# DATALOGGER_ADS_V1.net
KiCad netlist of a schematic drawn in EAGLE
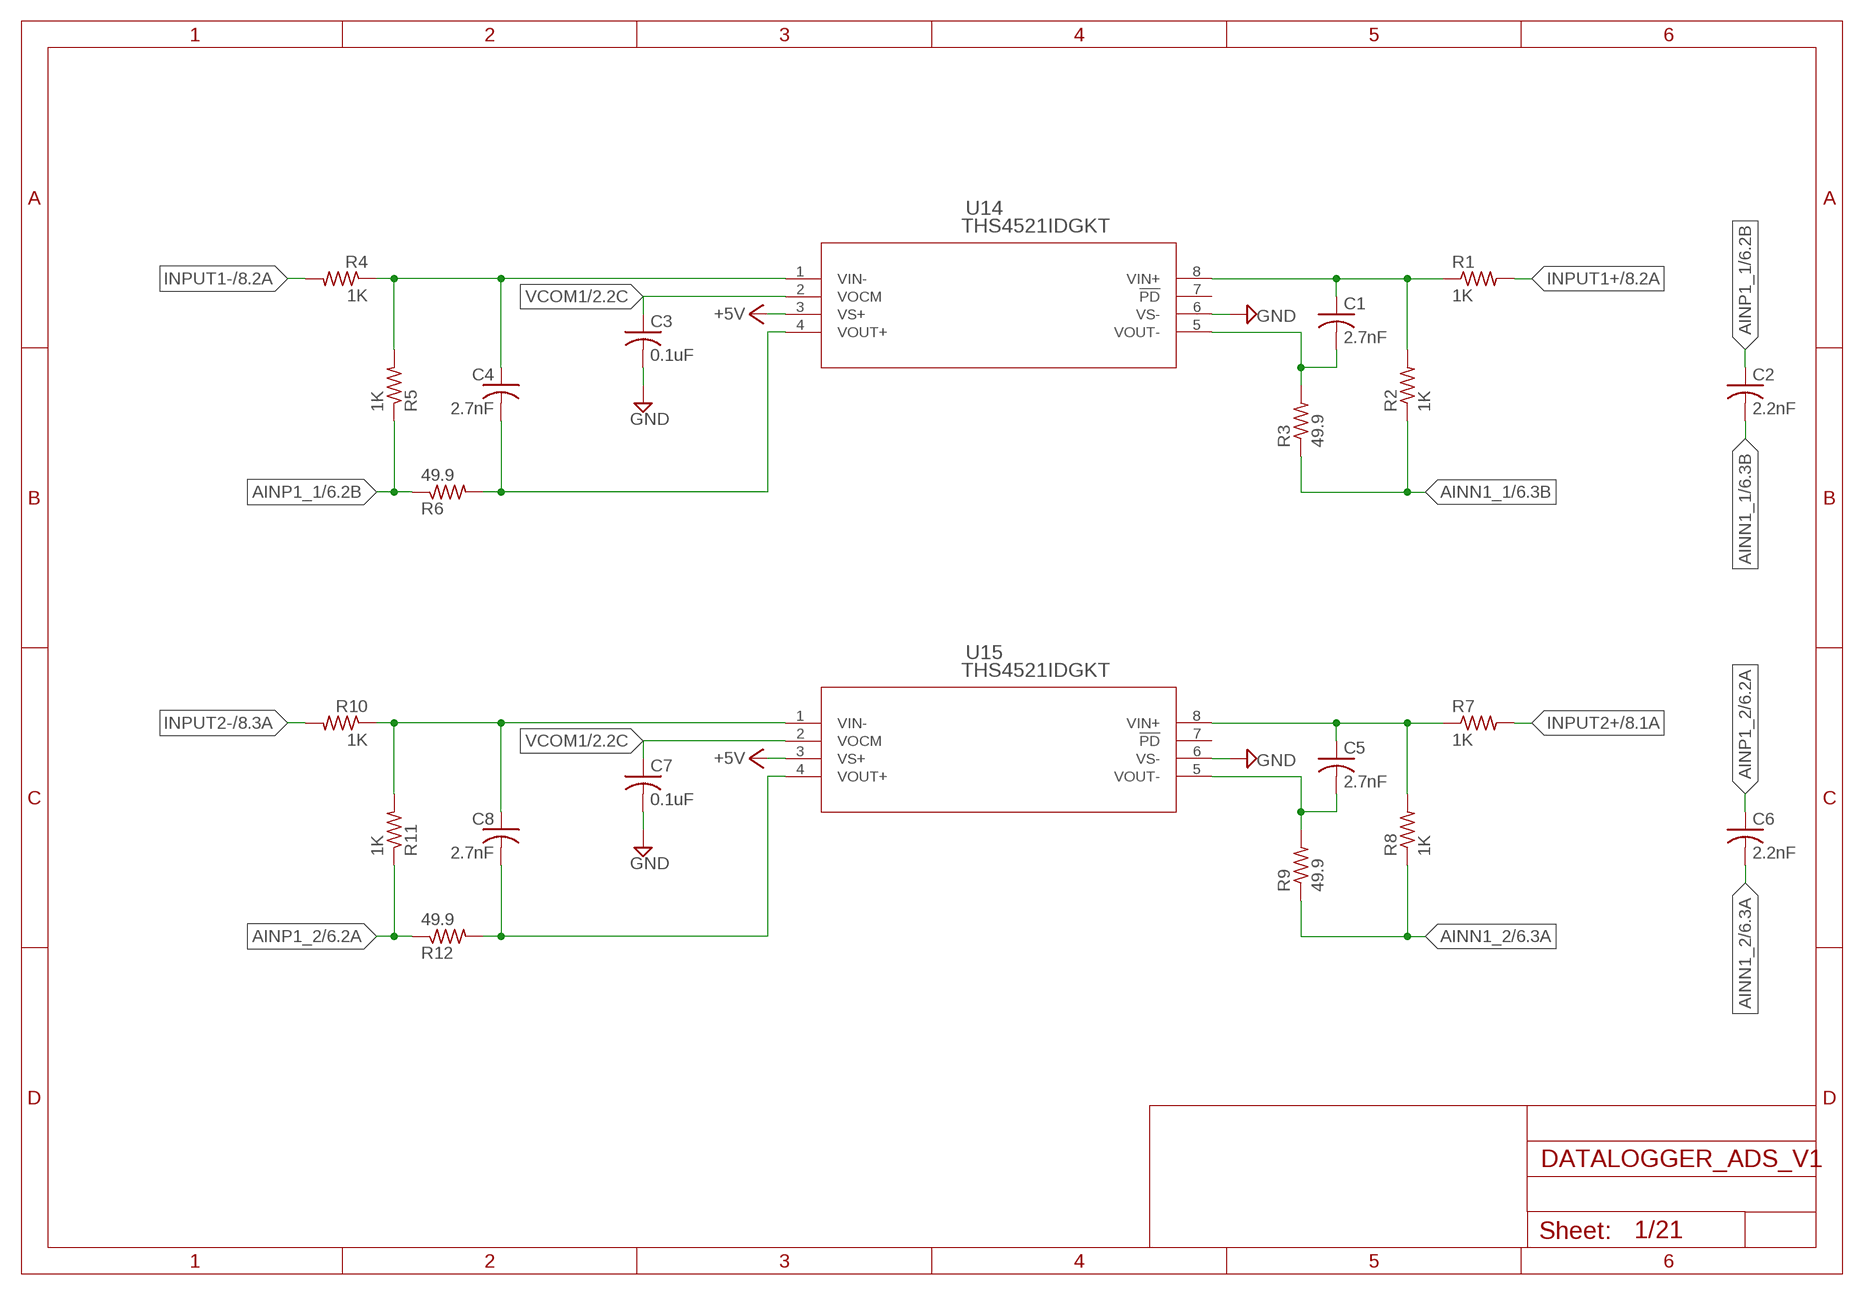
[diagram p0: schematic, sheet 1]
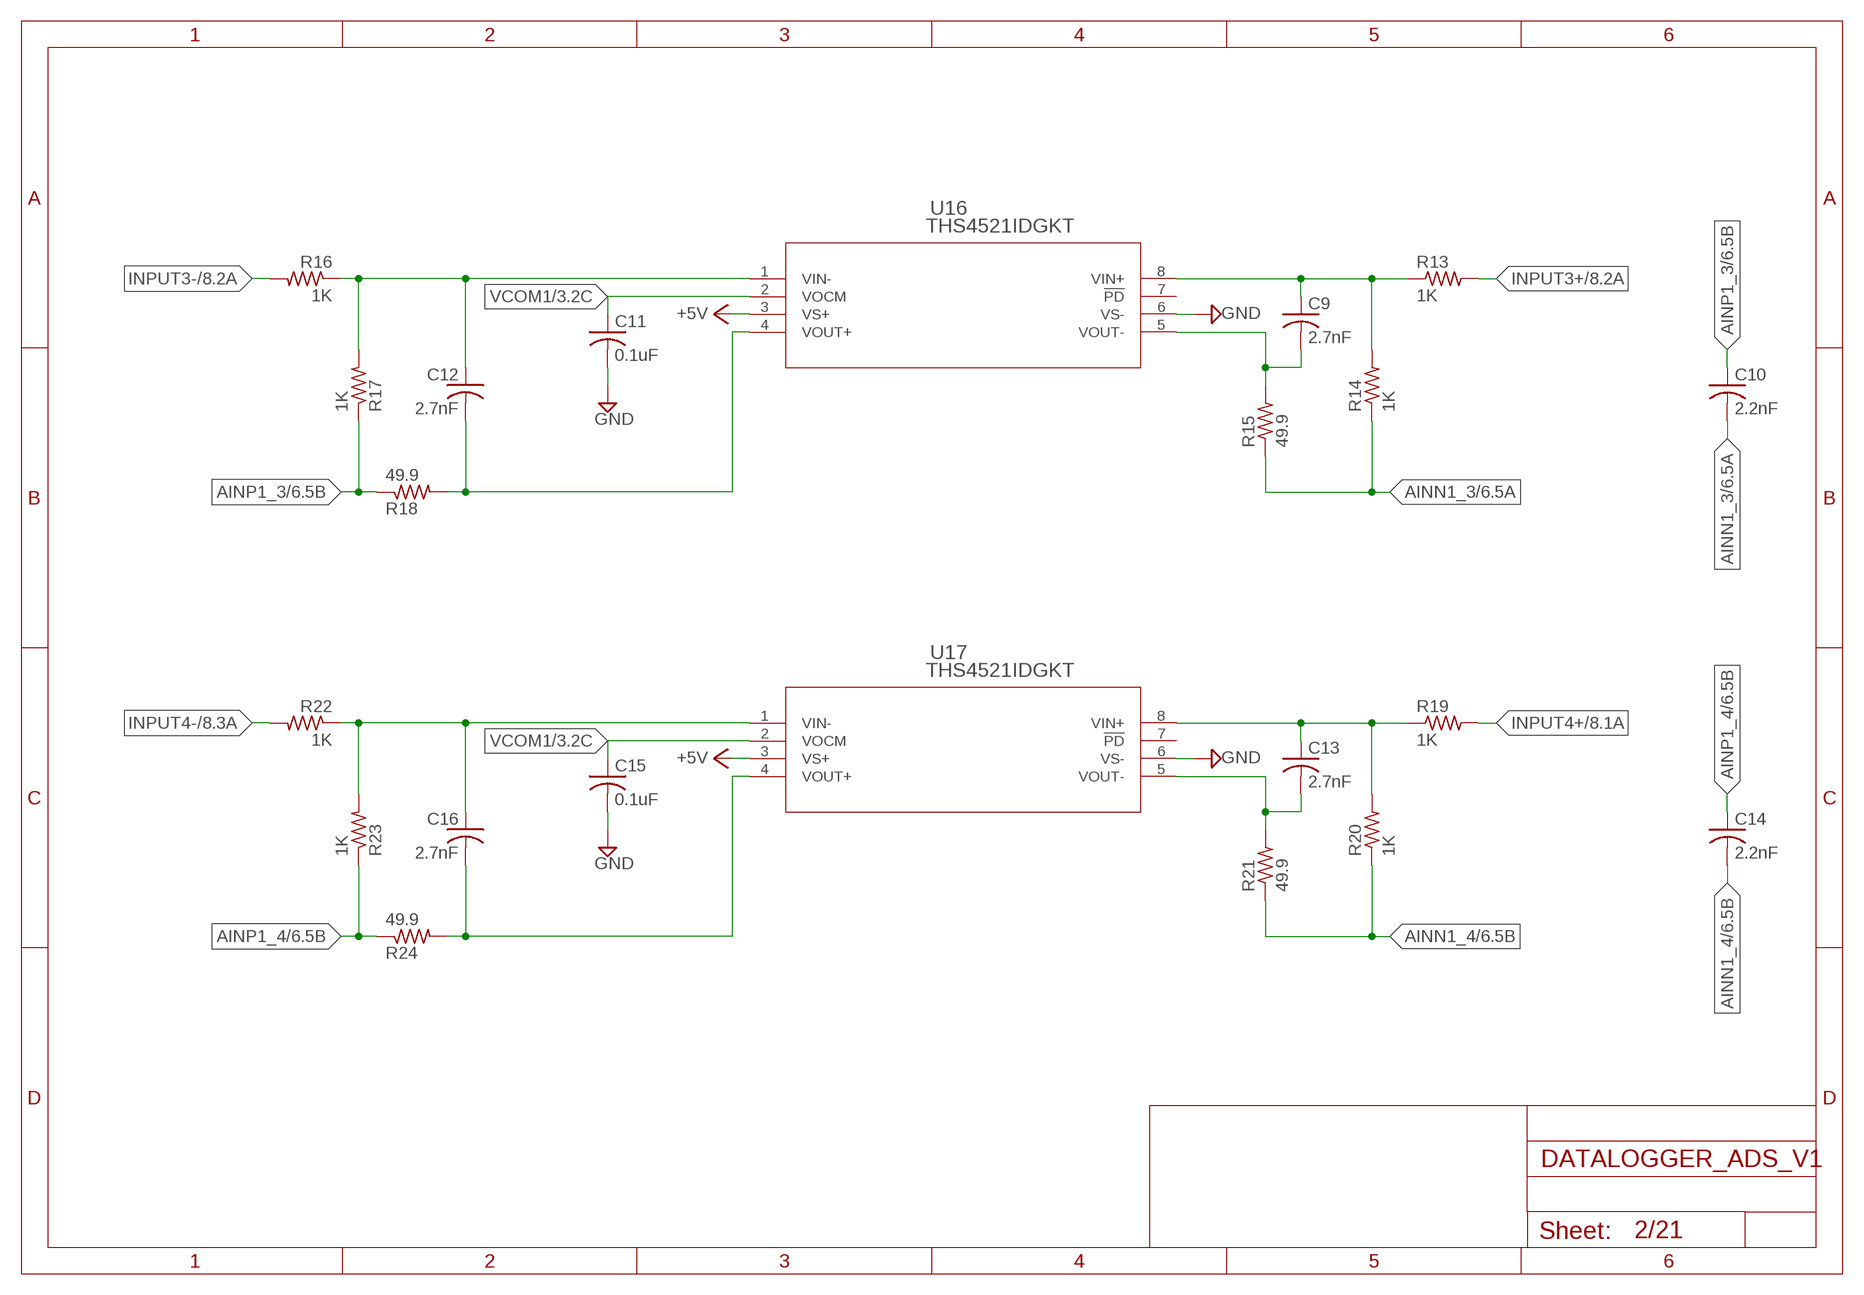
[diagram p1: schematic, sheet 2]
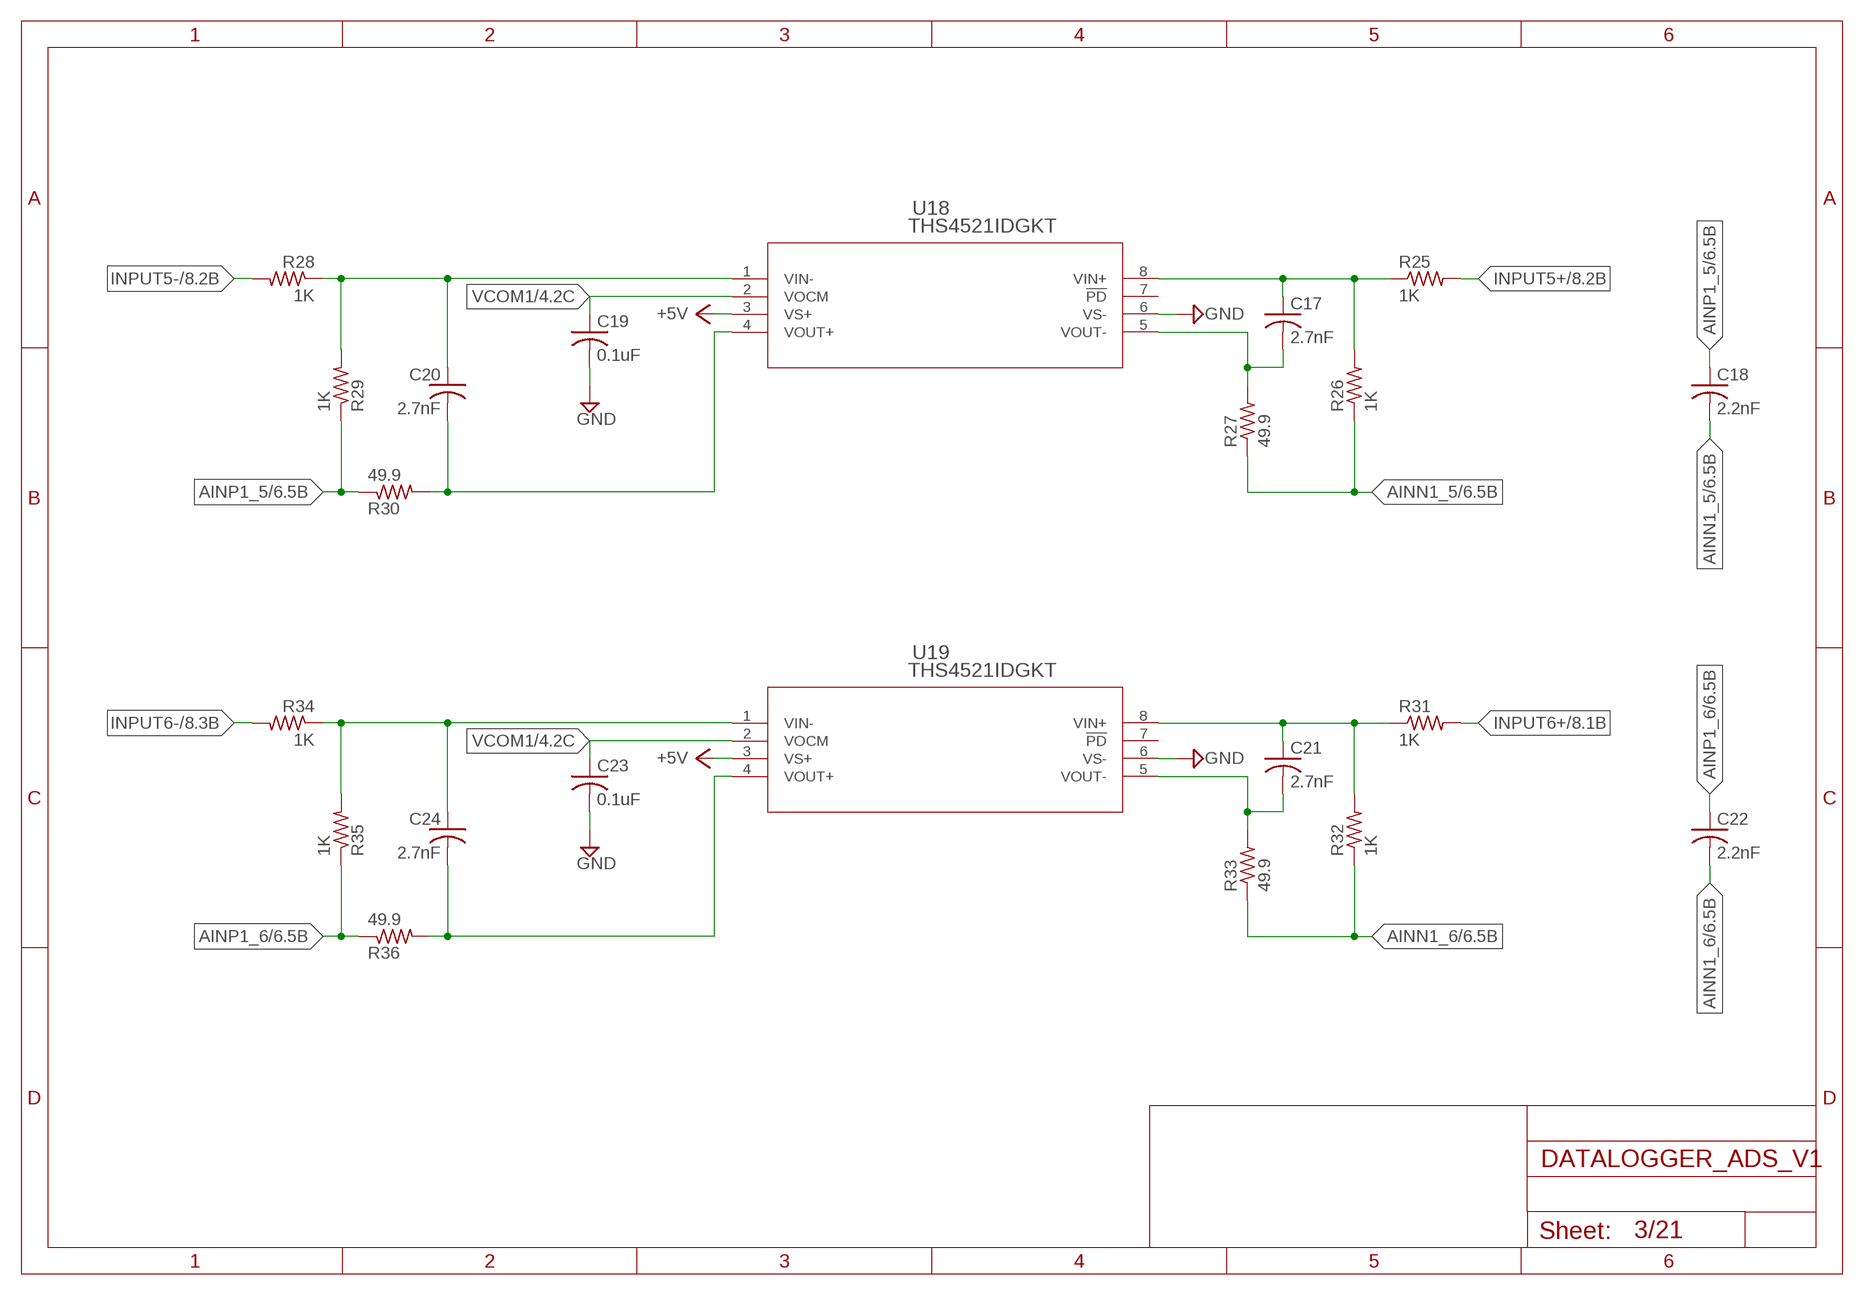
[diagram p2: schematic, sheet 3]
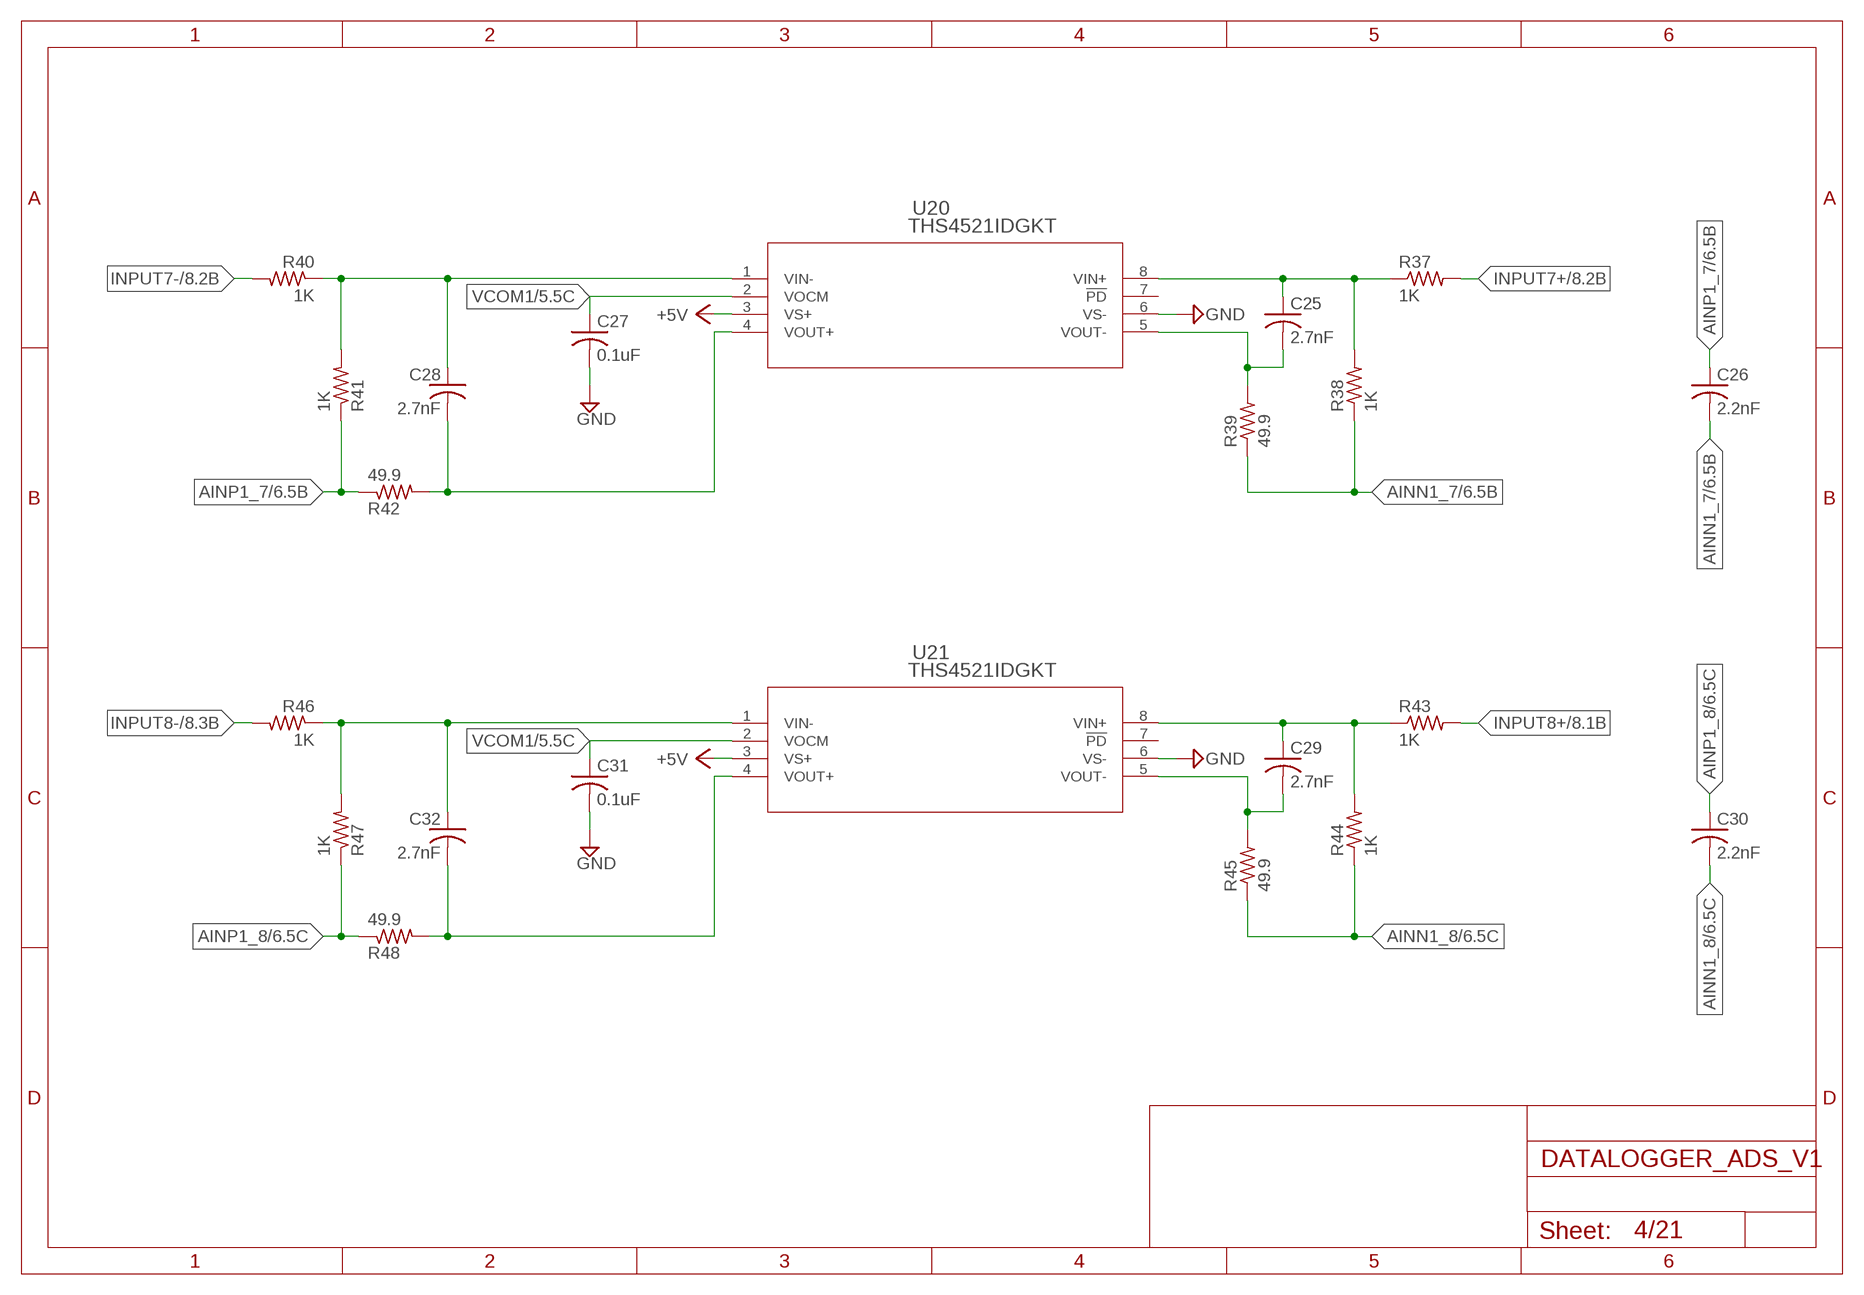
[diagram p3: schematic, sheet 4]
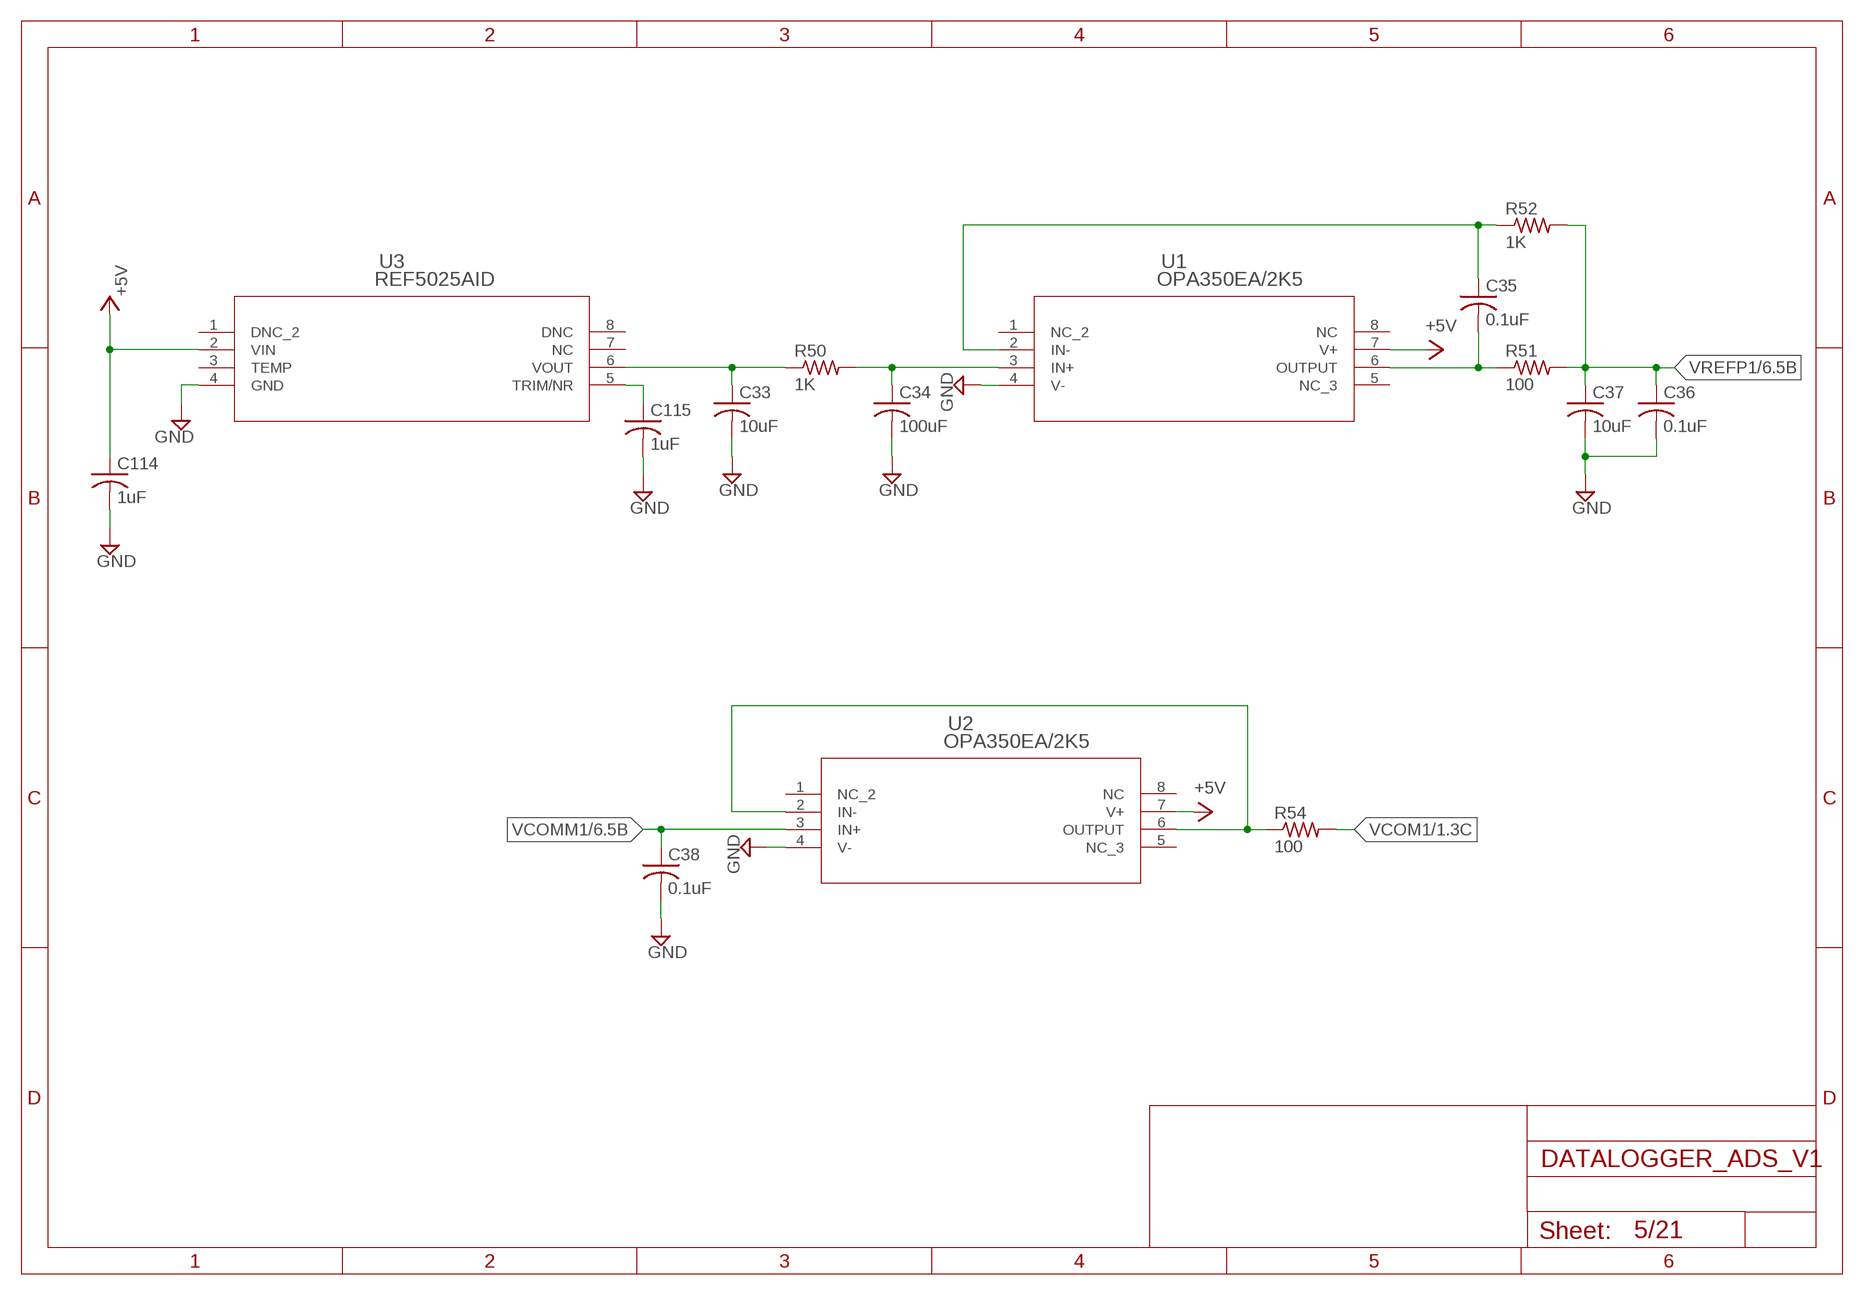
[diagram p4: schematic, sheet 5]
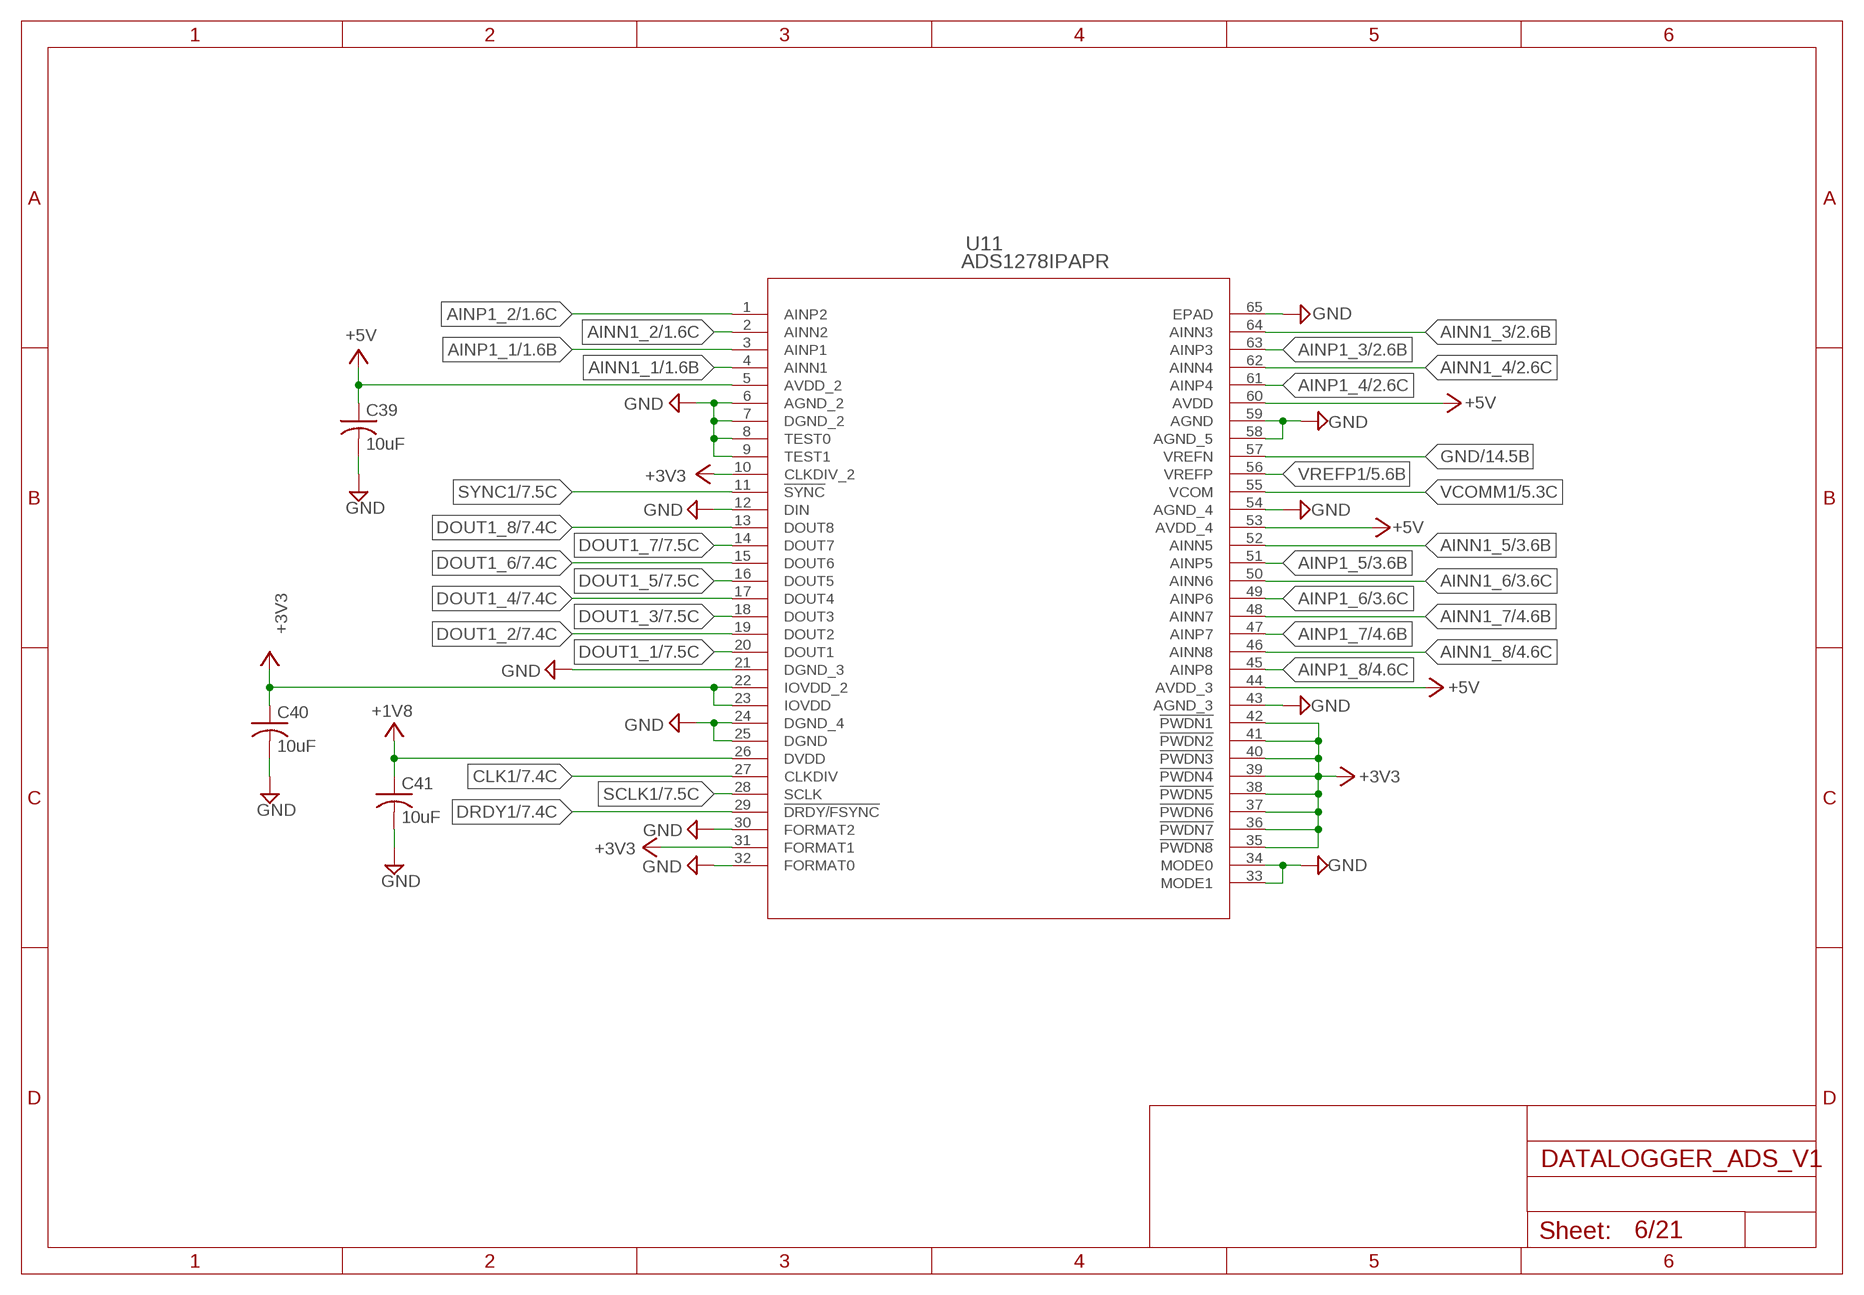
[diagram p5: schematic, sheet 6]
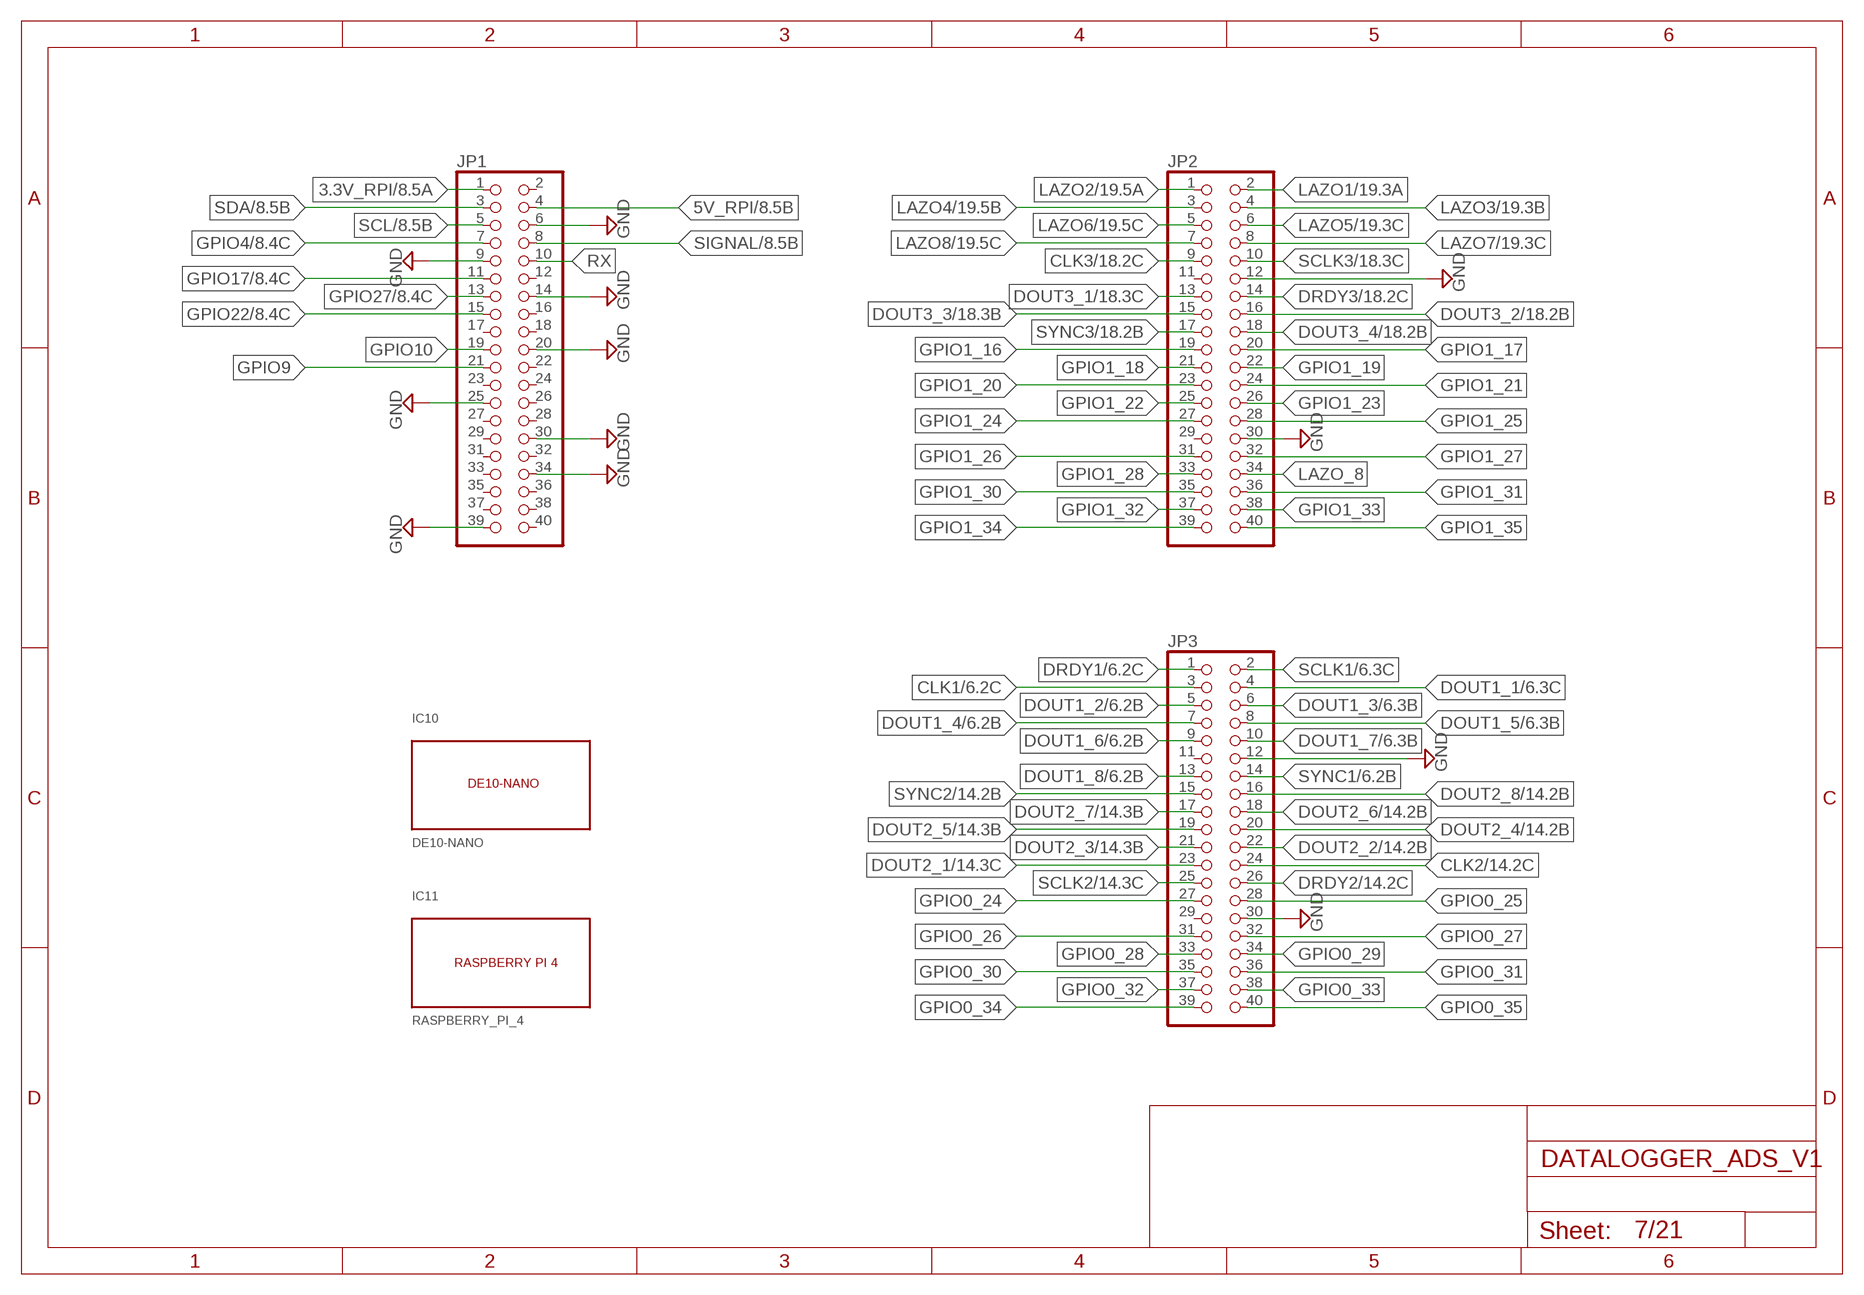
[diagram p6: schematic, sheet 7]
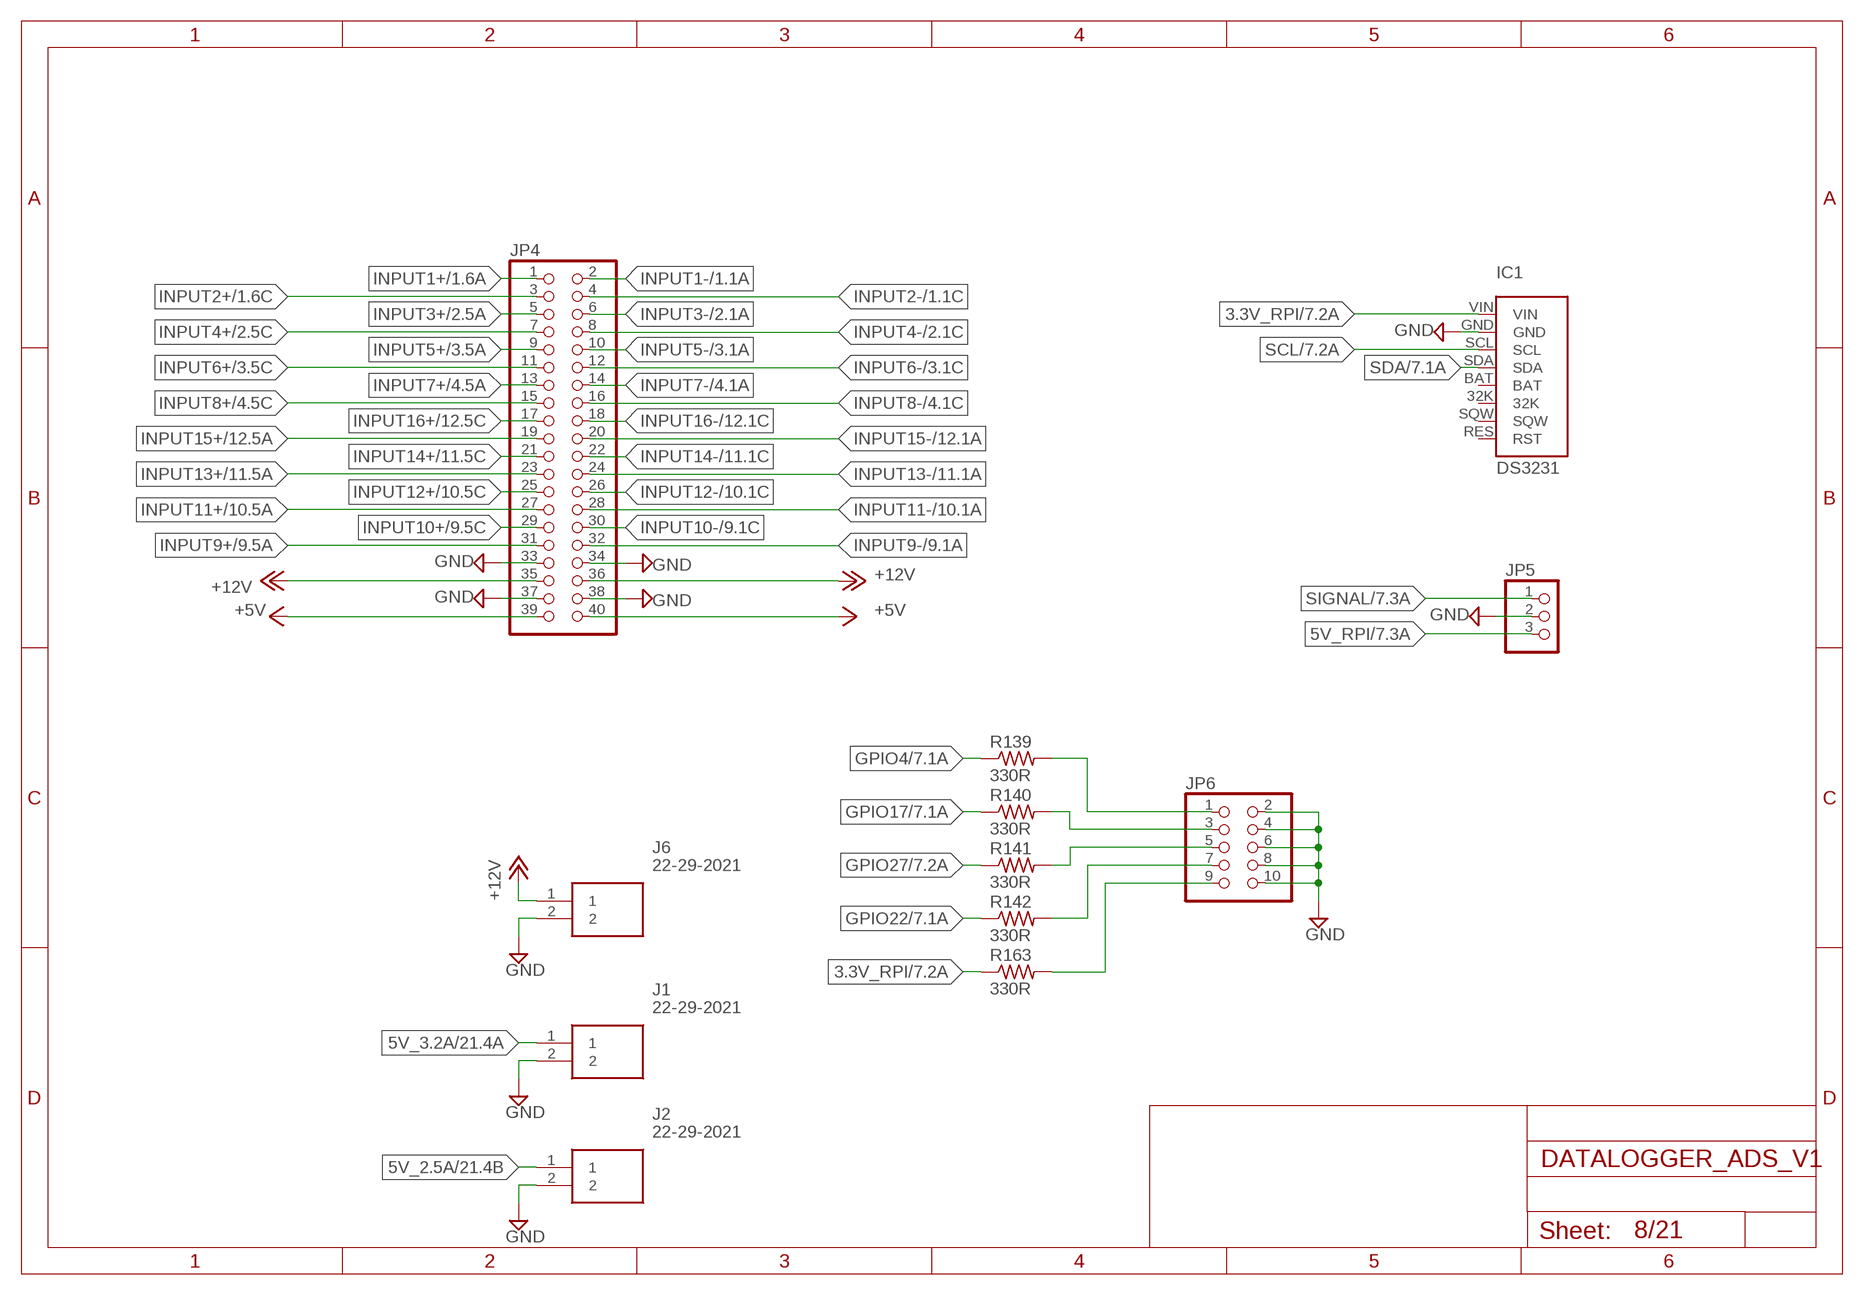
[diagram p7: schematic, sheet 8]
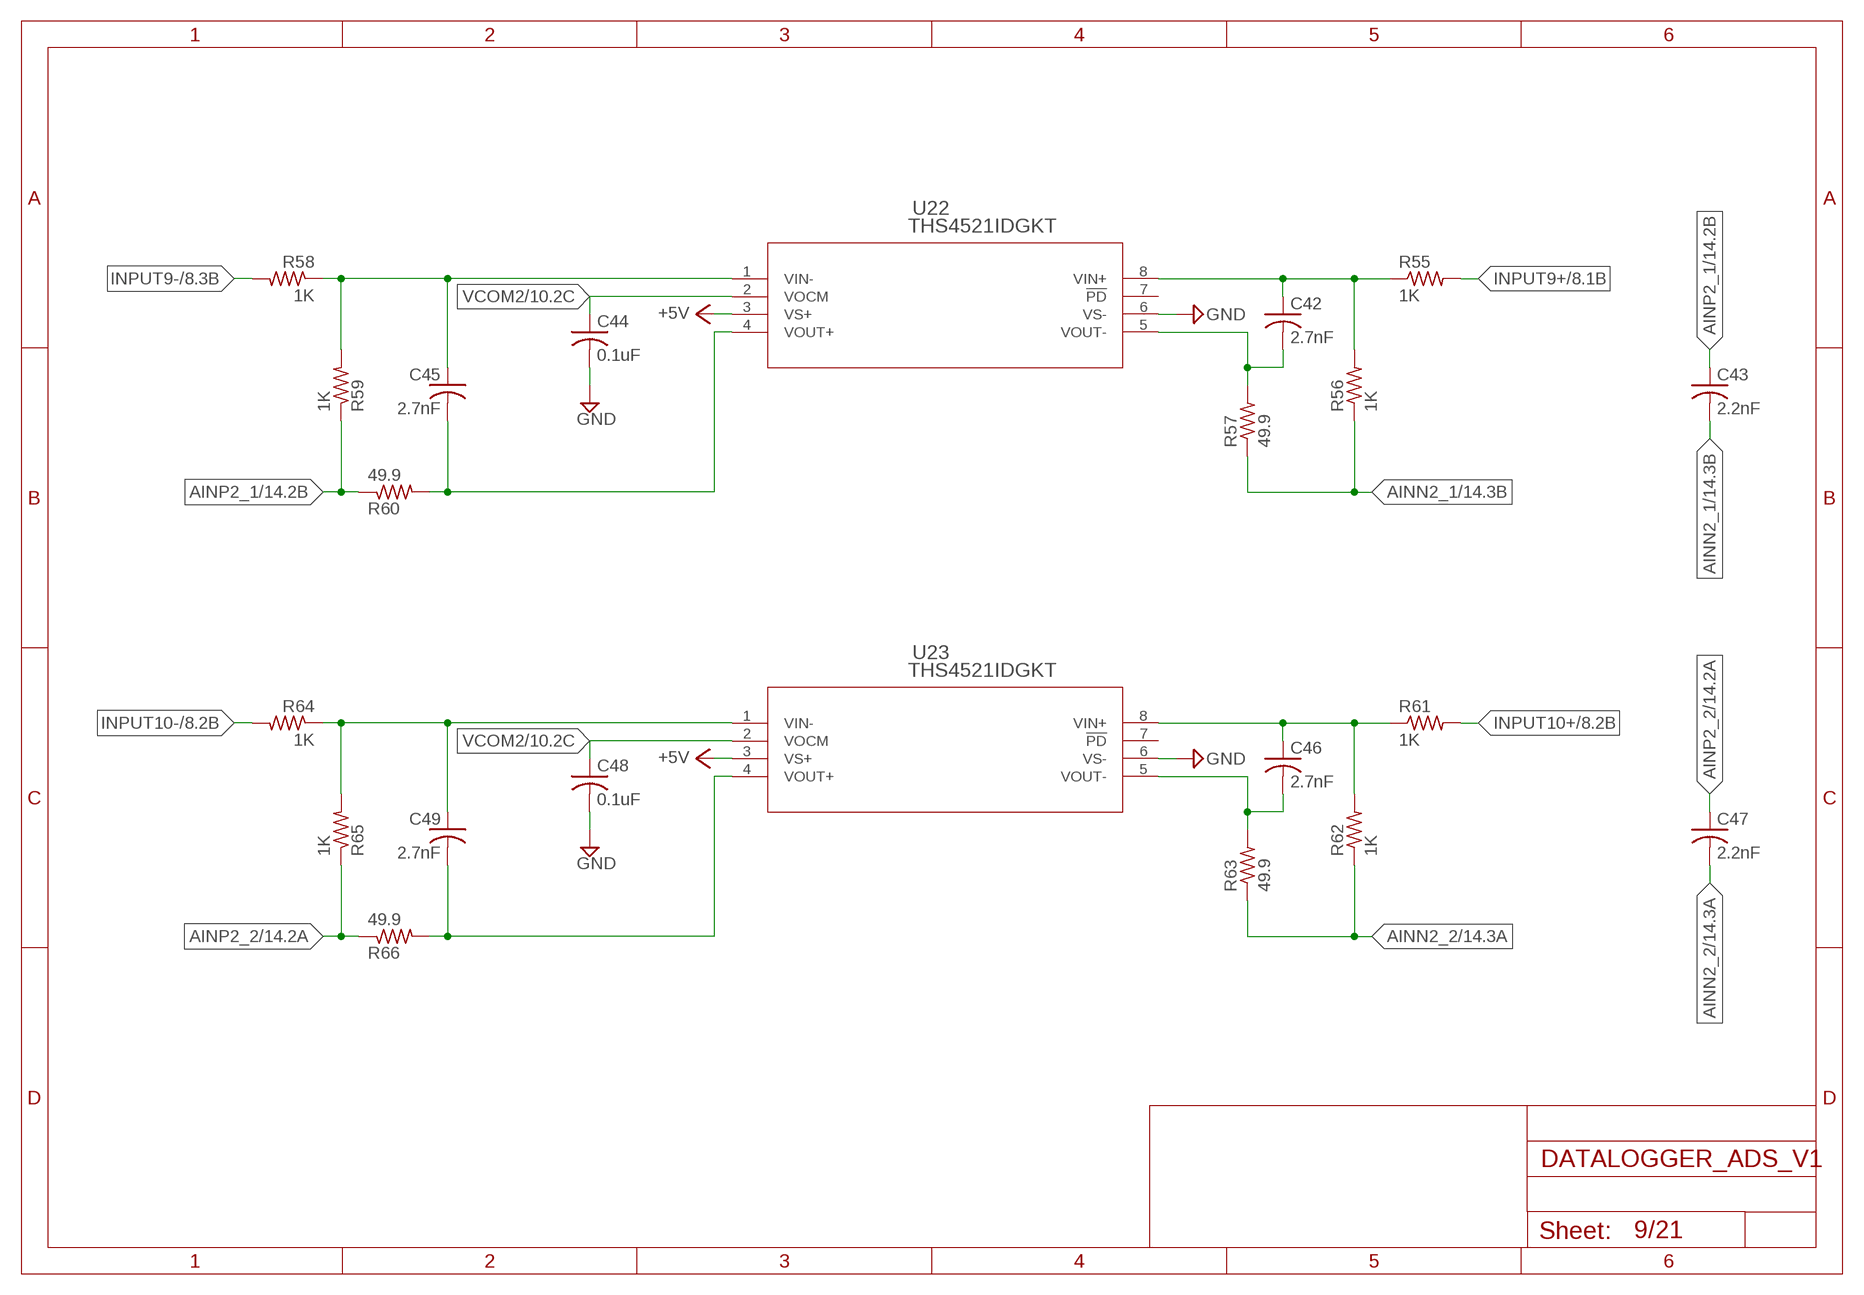
[diagram p8: schematic, sheet 9]
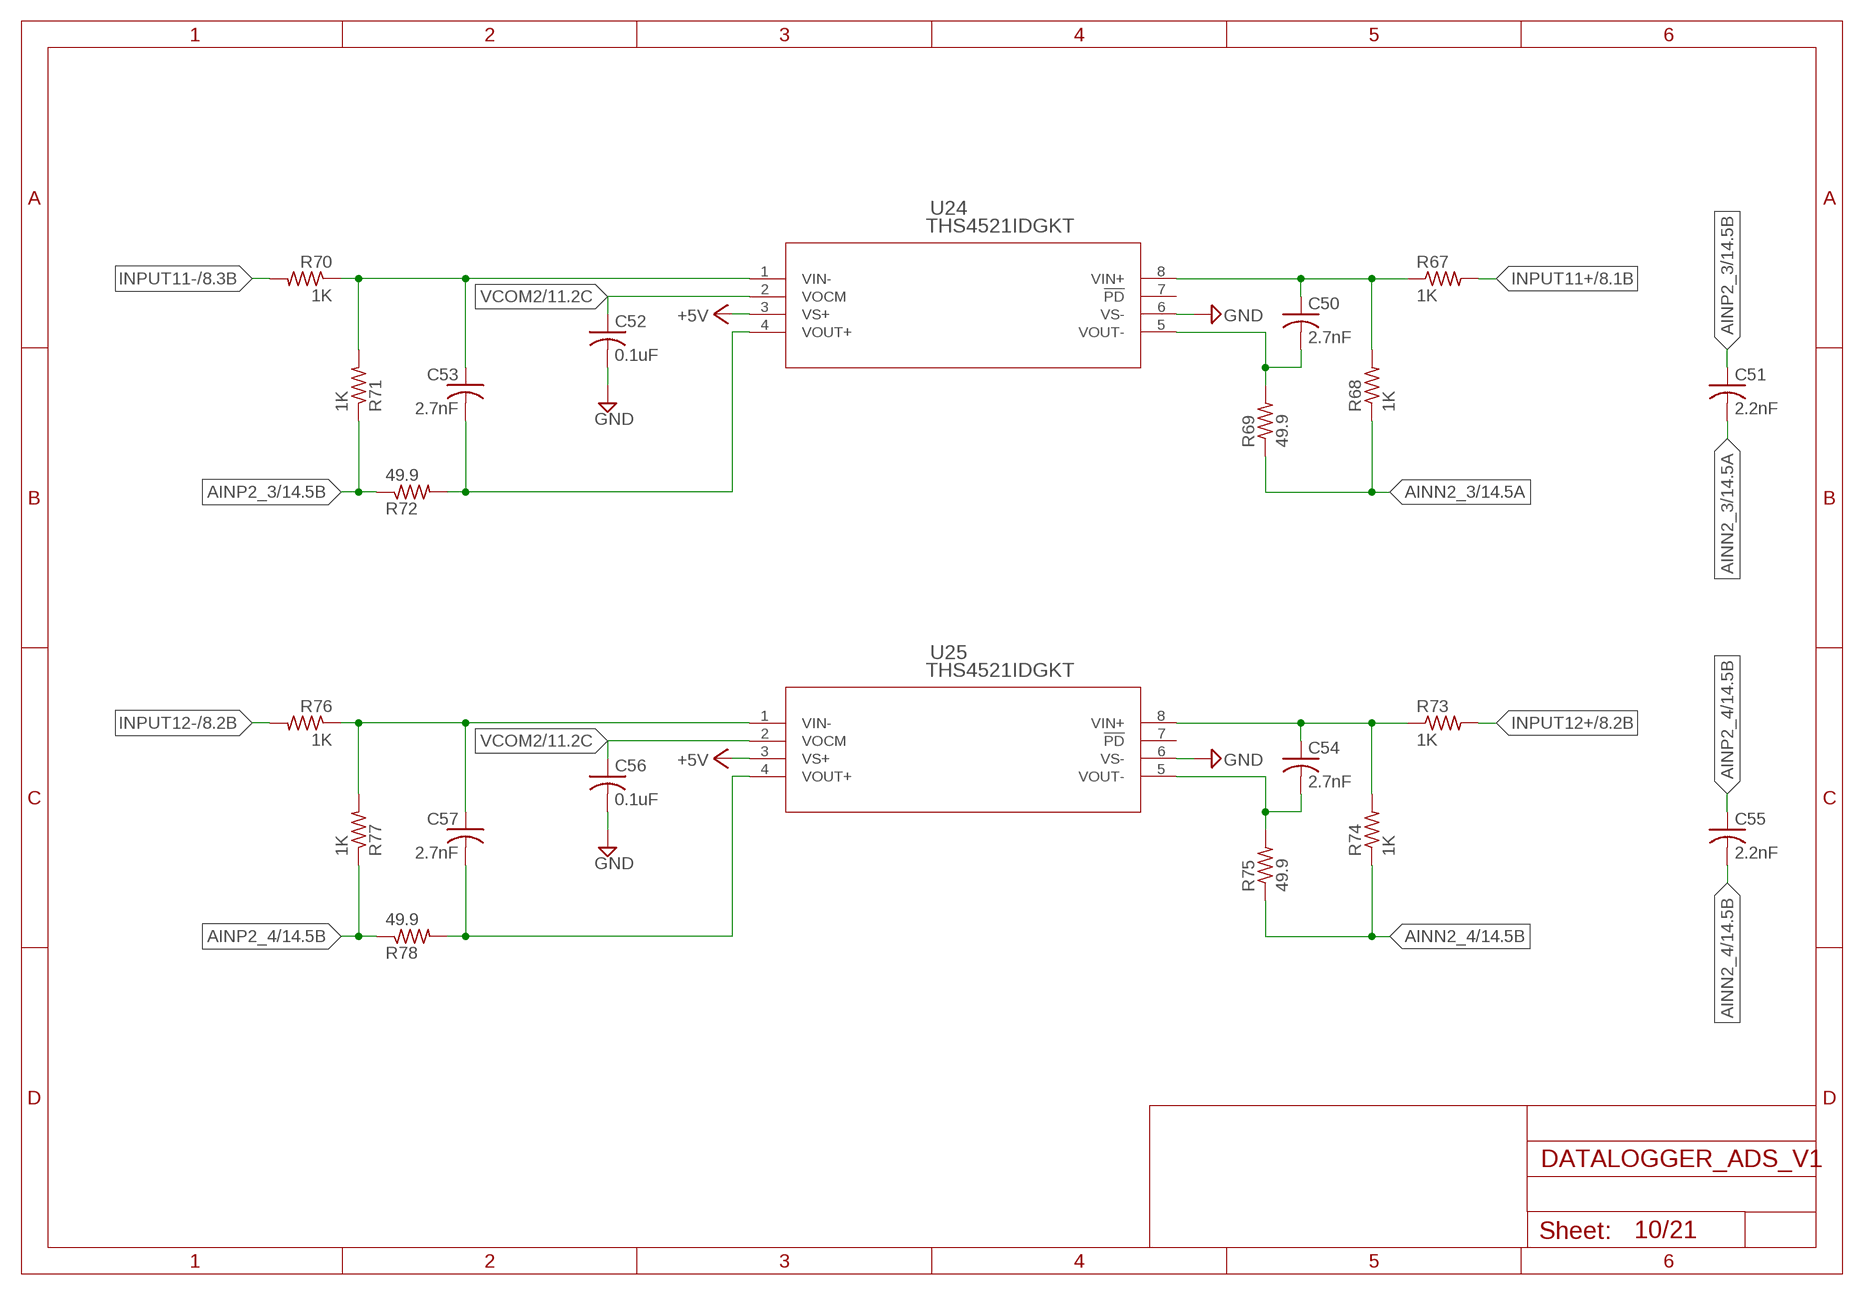
[diagram p9: schematic, sheet 10]
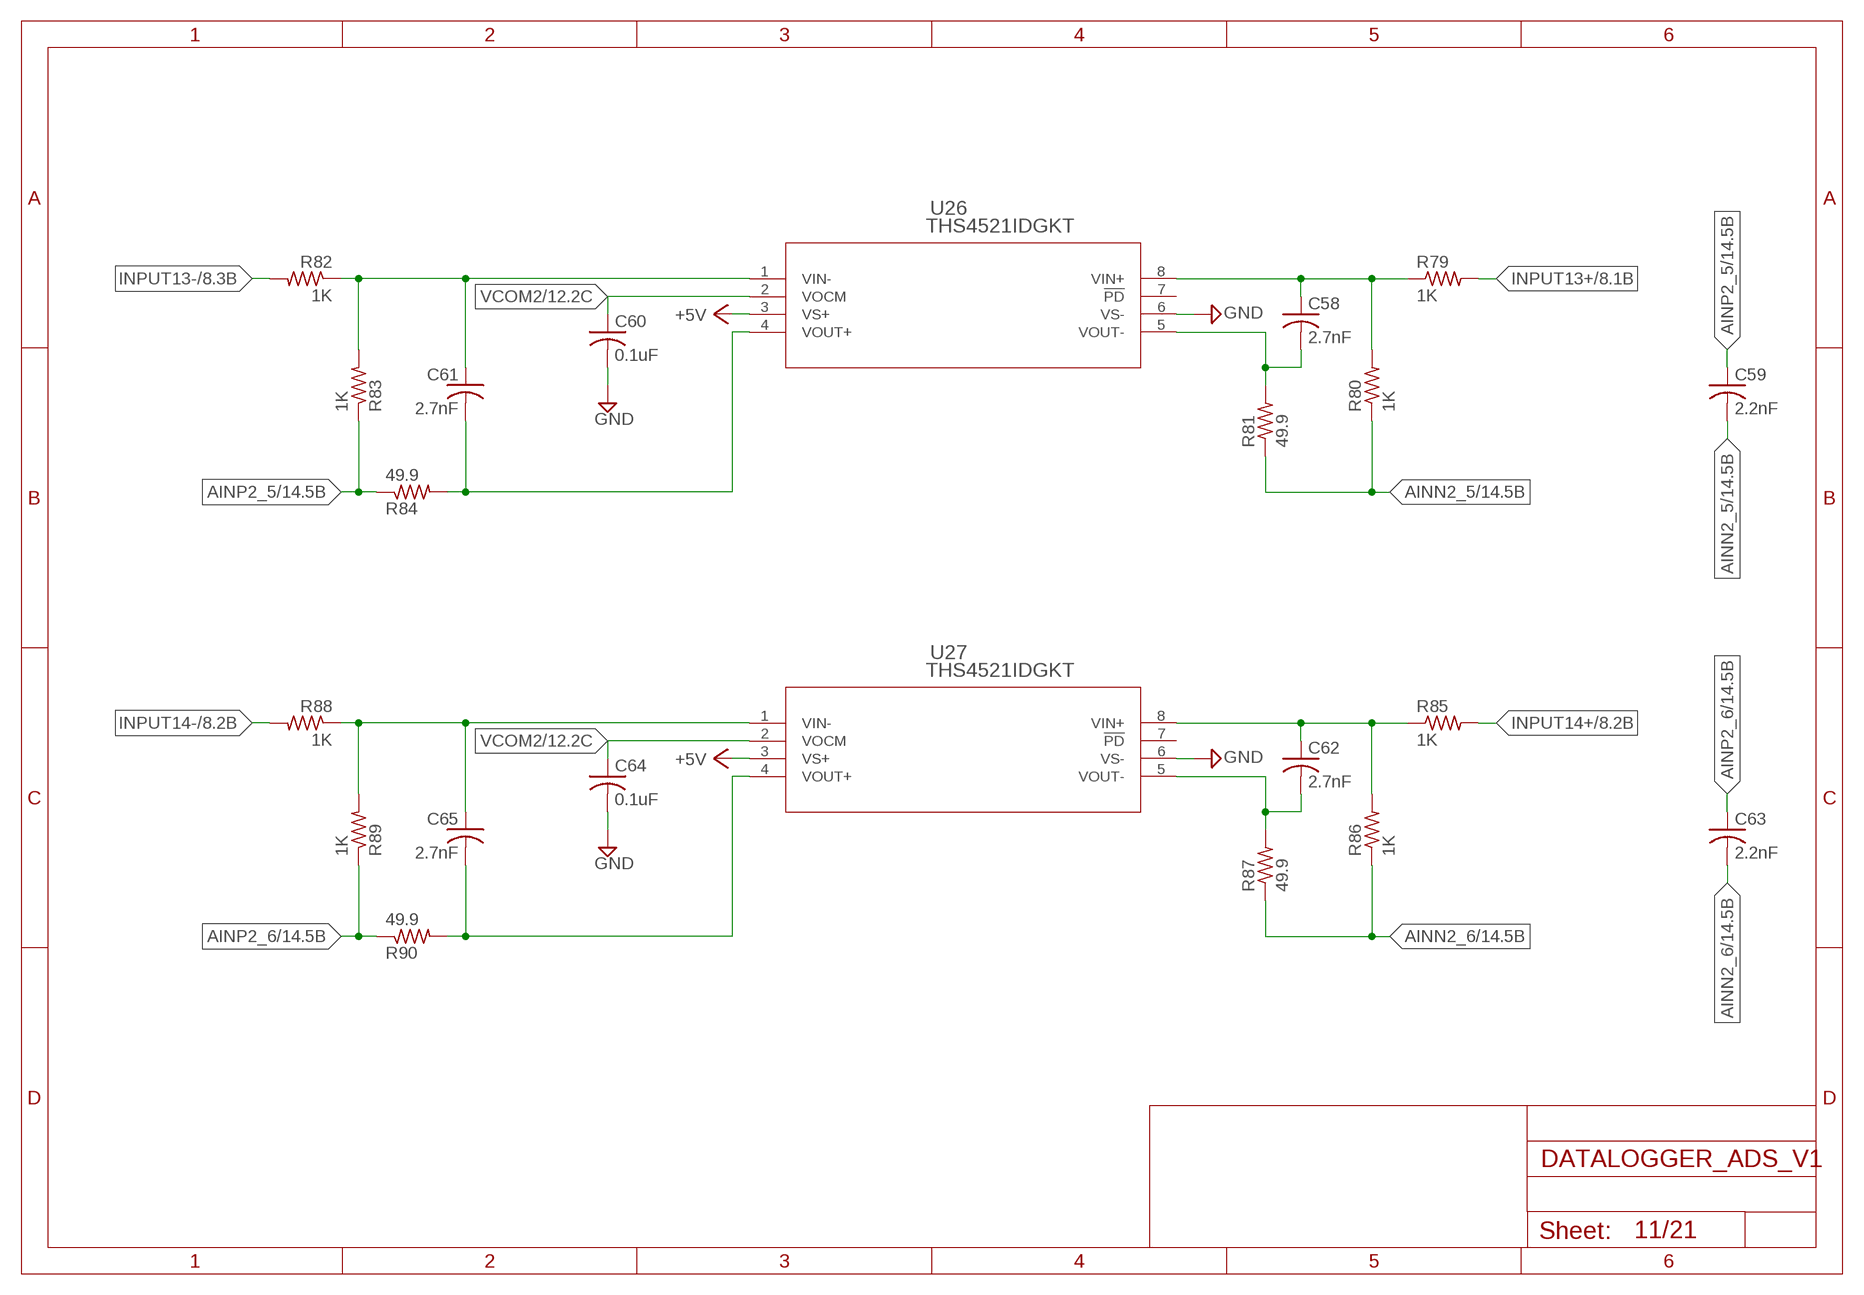
[diagram p10: schematic, sheet 11]
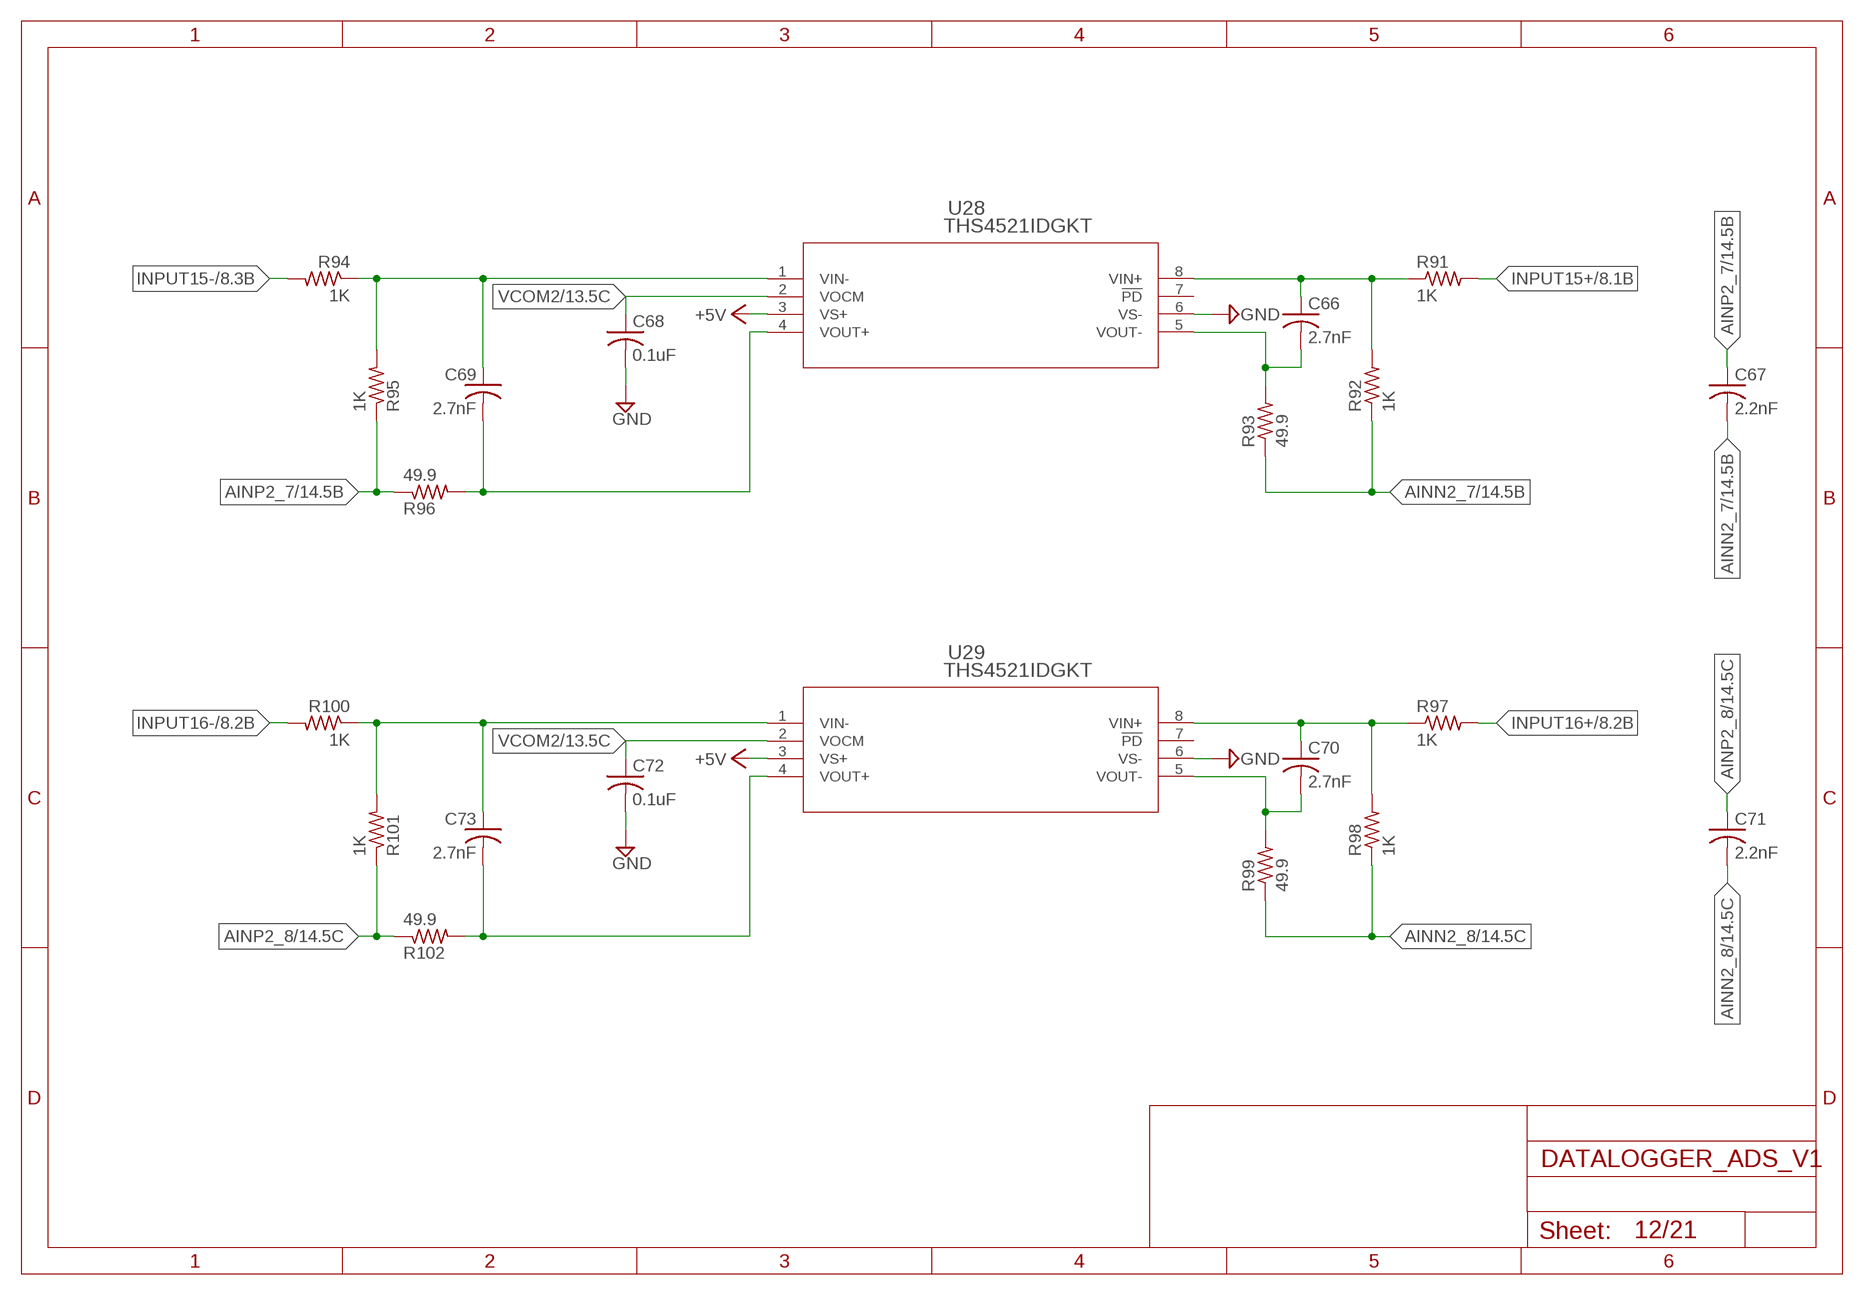
[diagram p11: schematic, sheet 12]
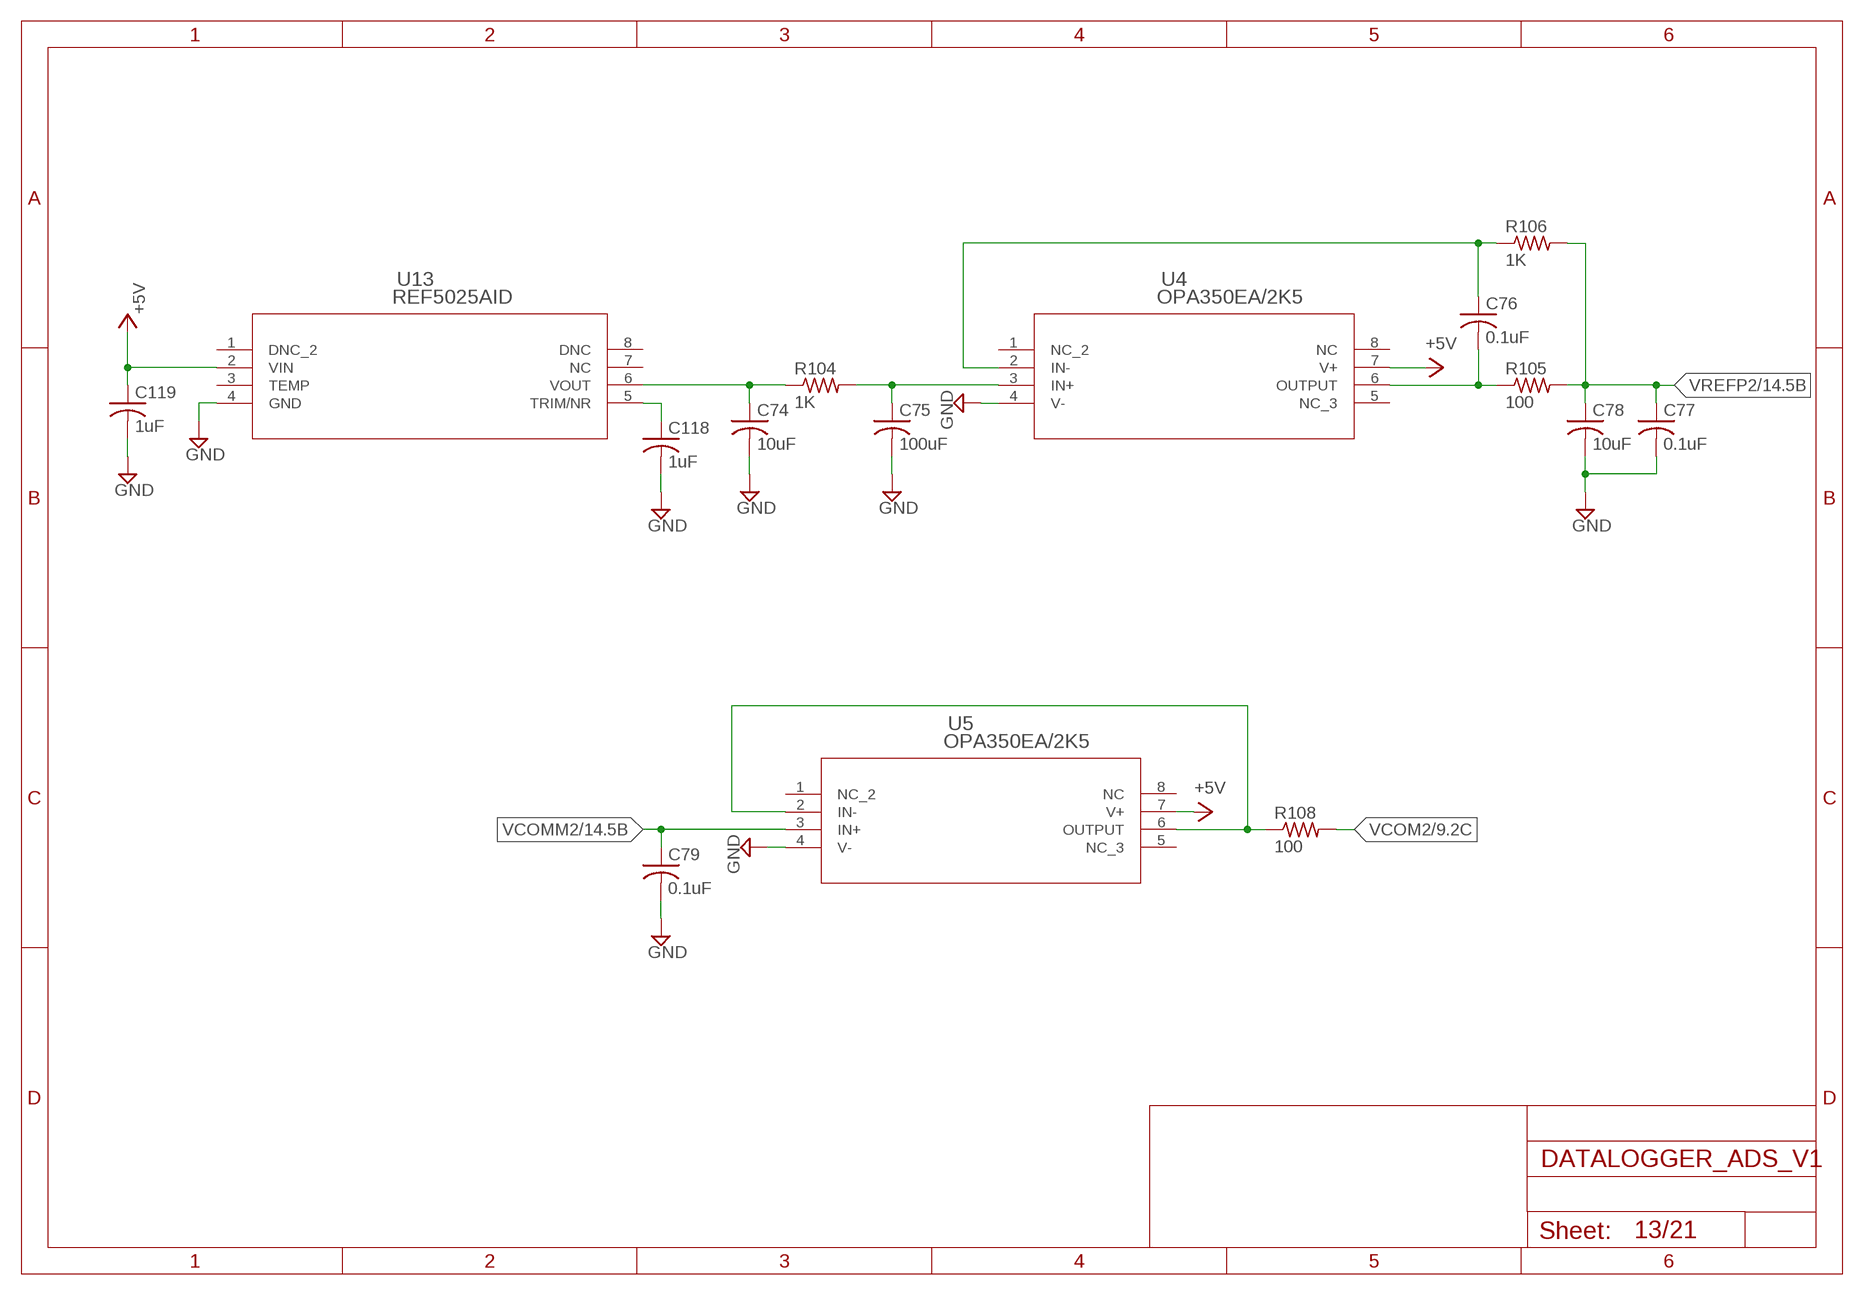
[diagram p12: schematic, sheet 13]
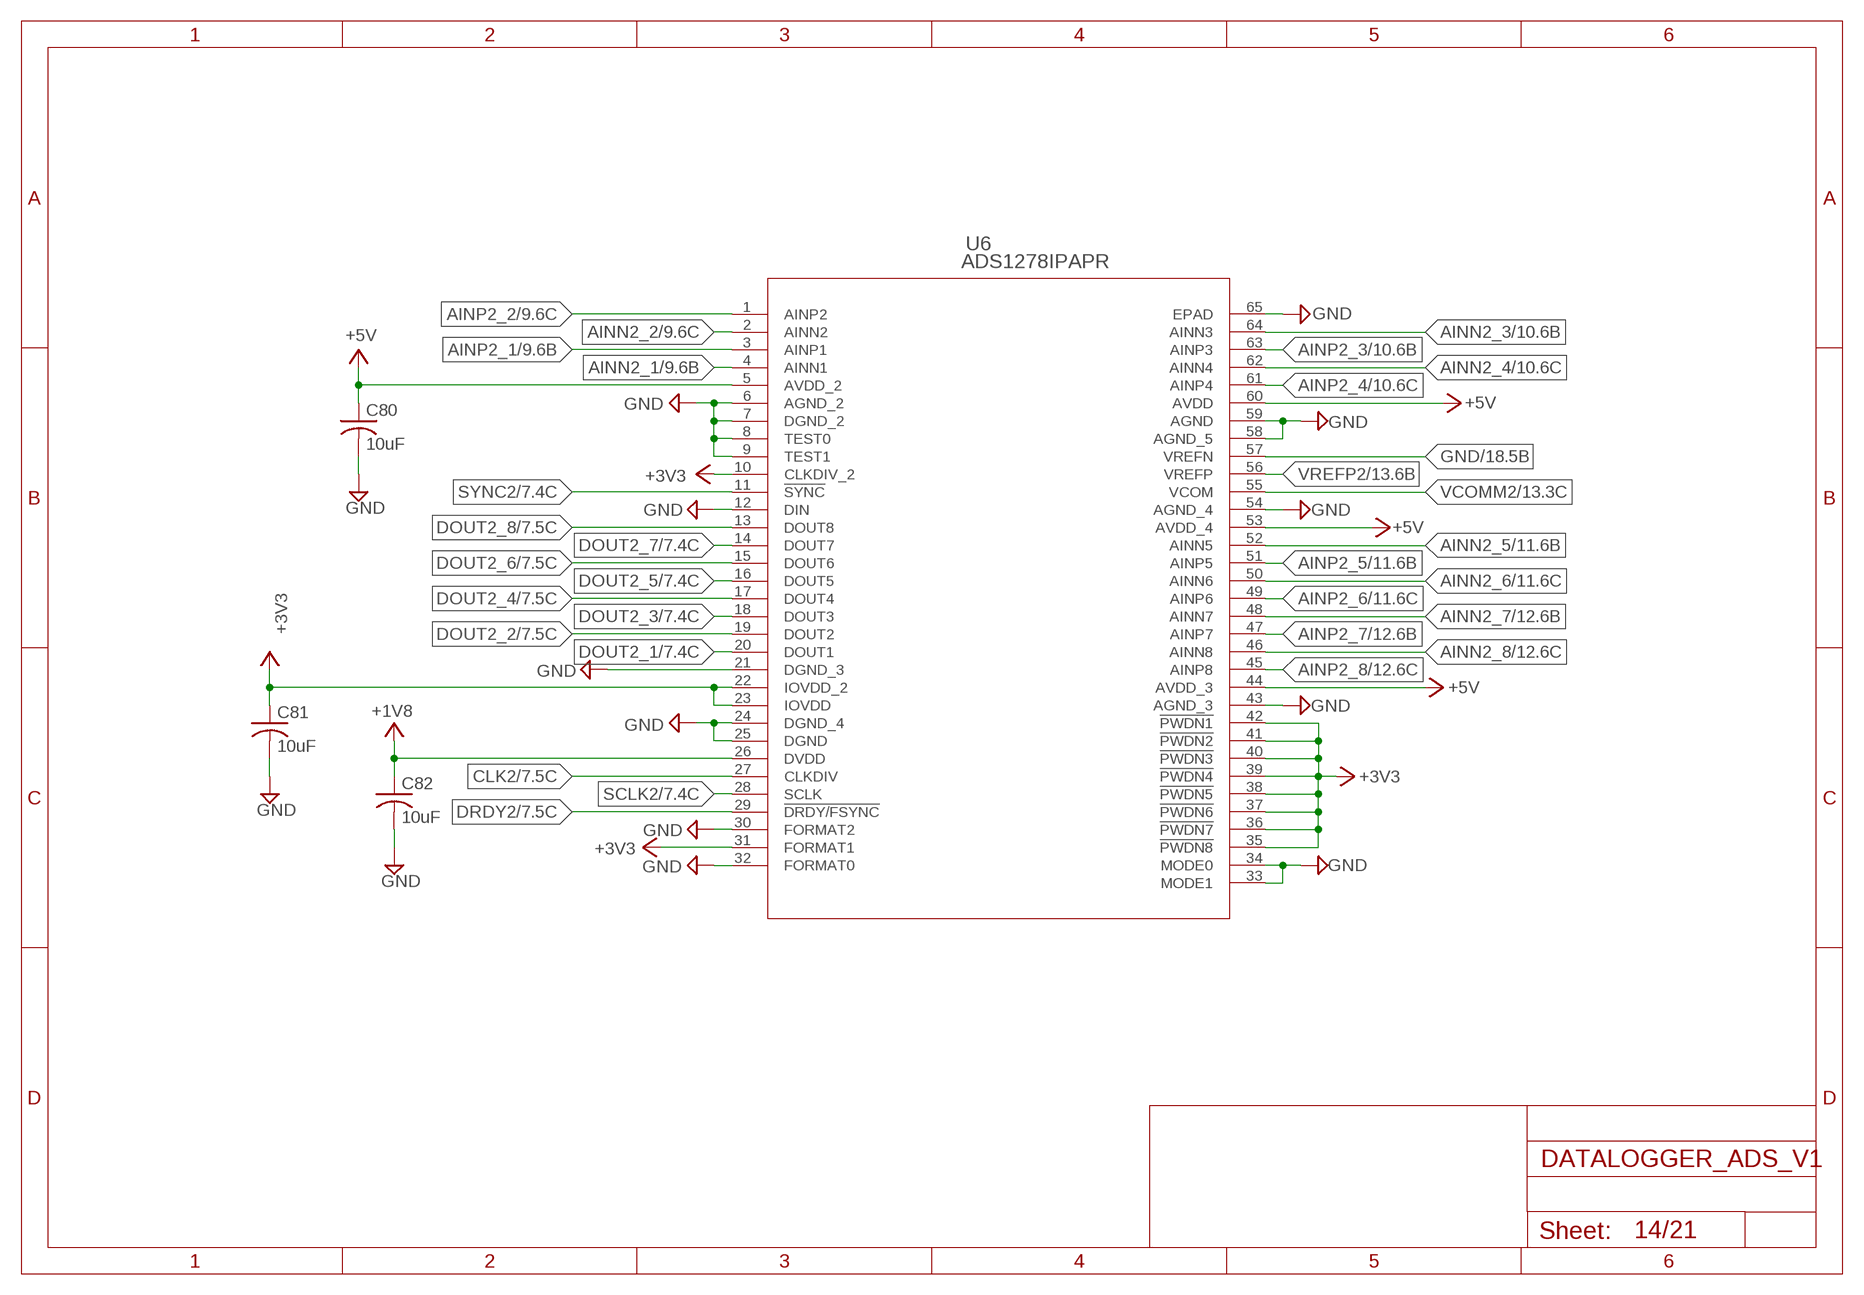
[diagram p13: schematic, sheet 14]
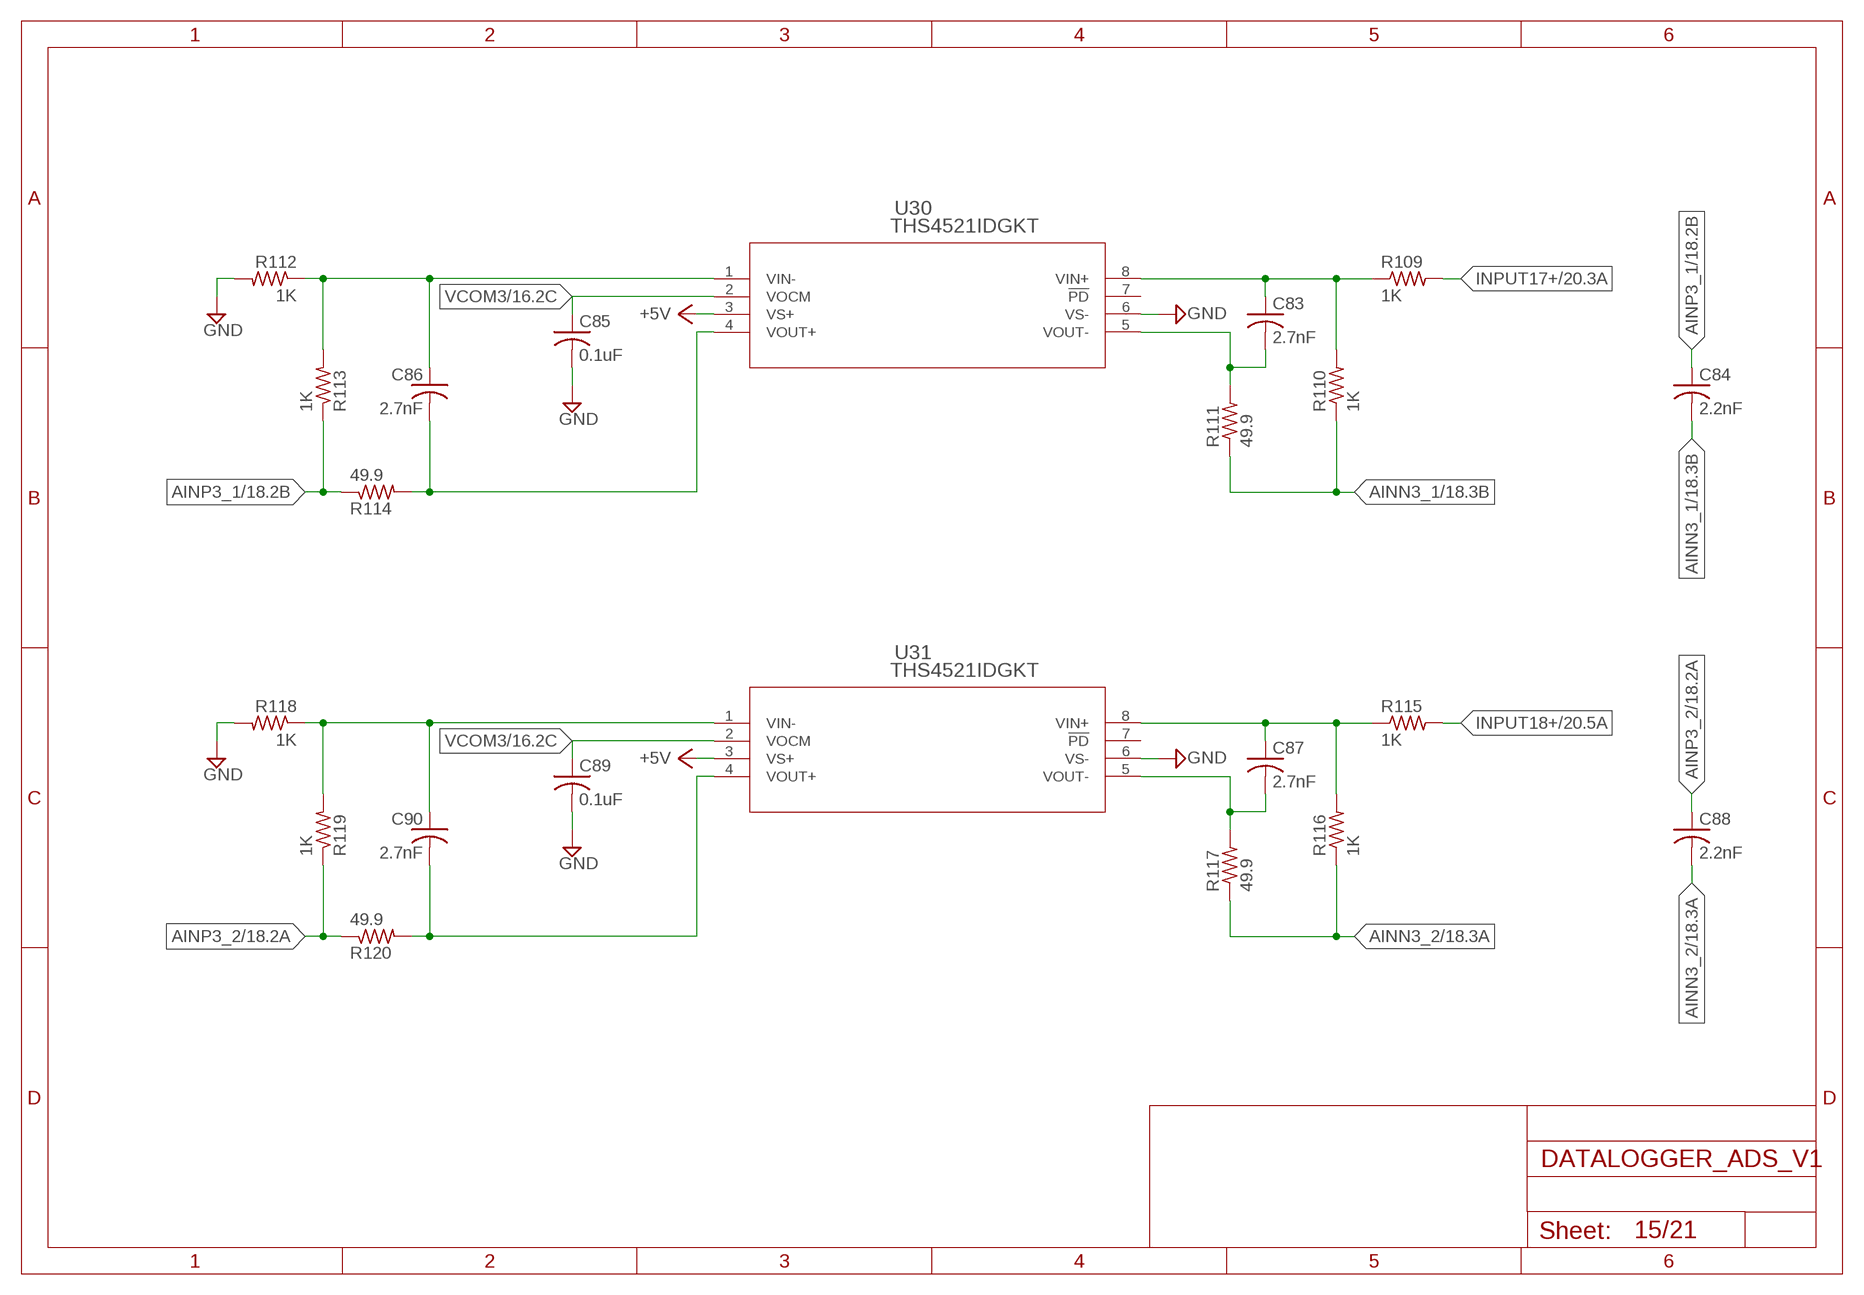
[diagram p14: schematic, sheet 15]
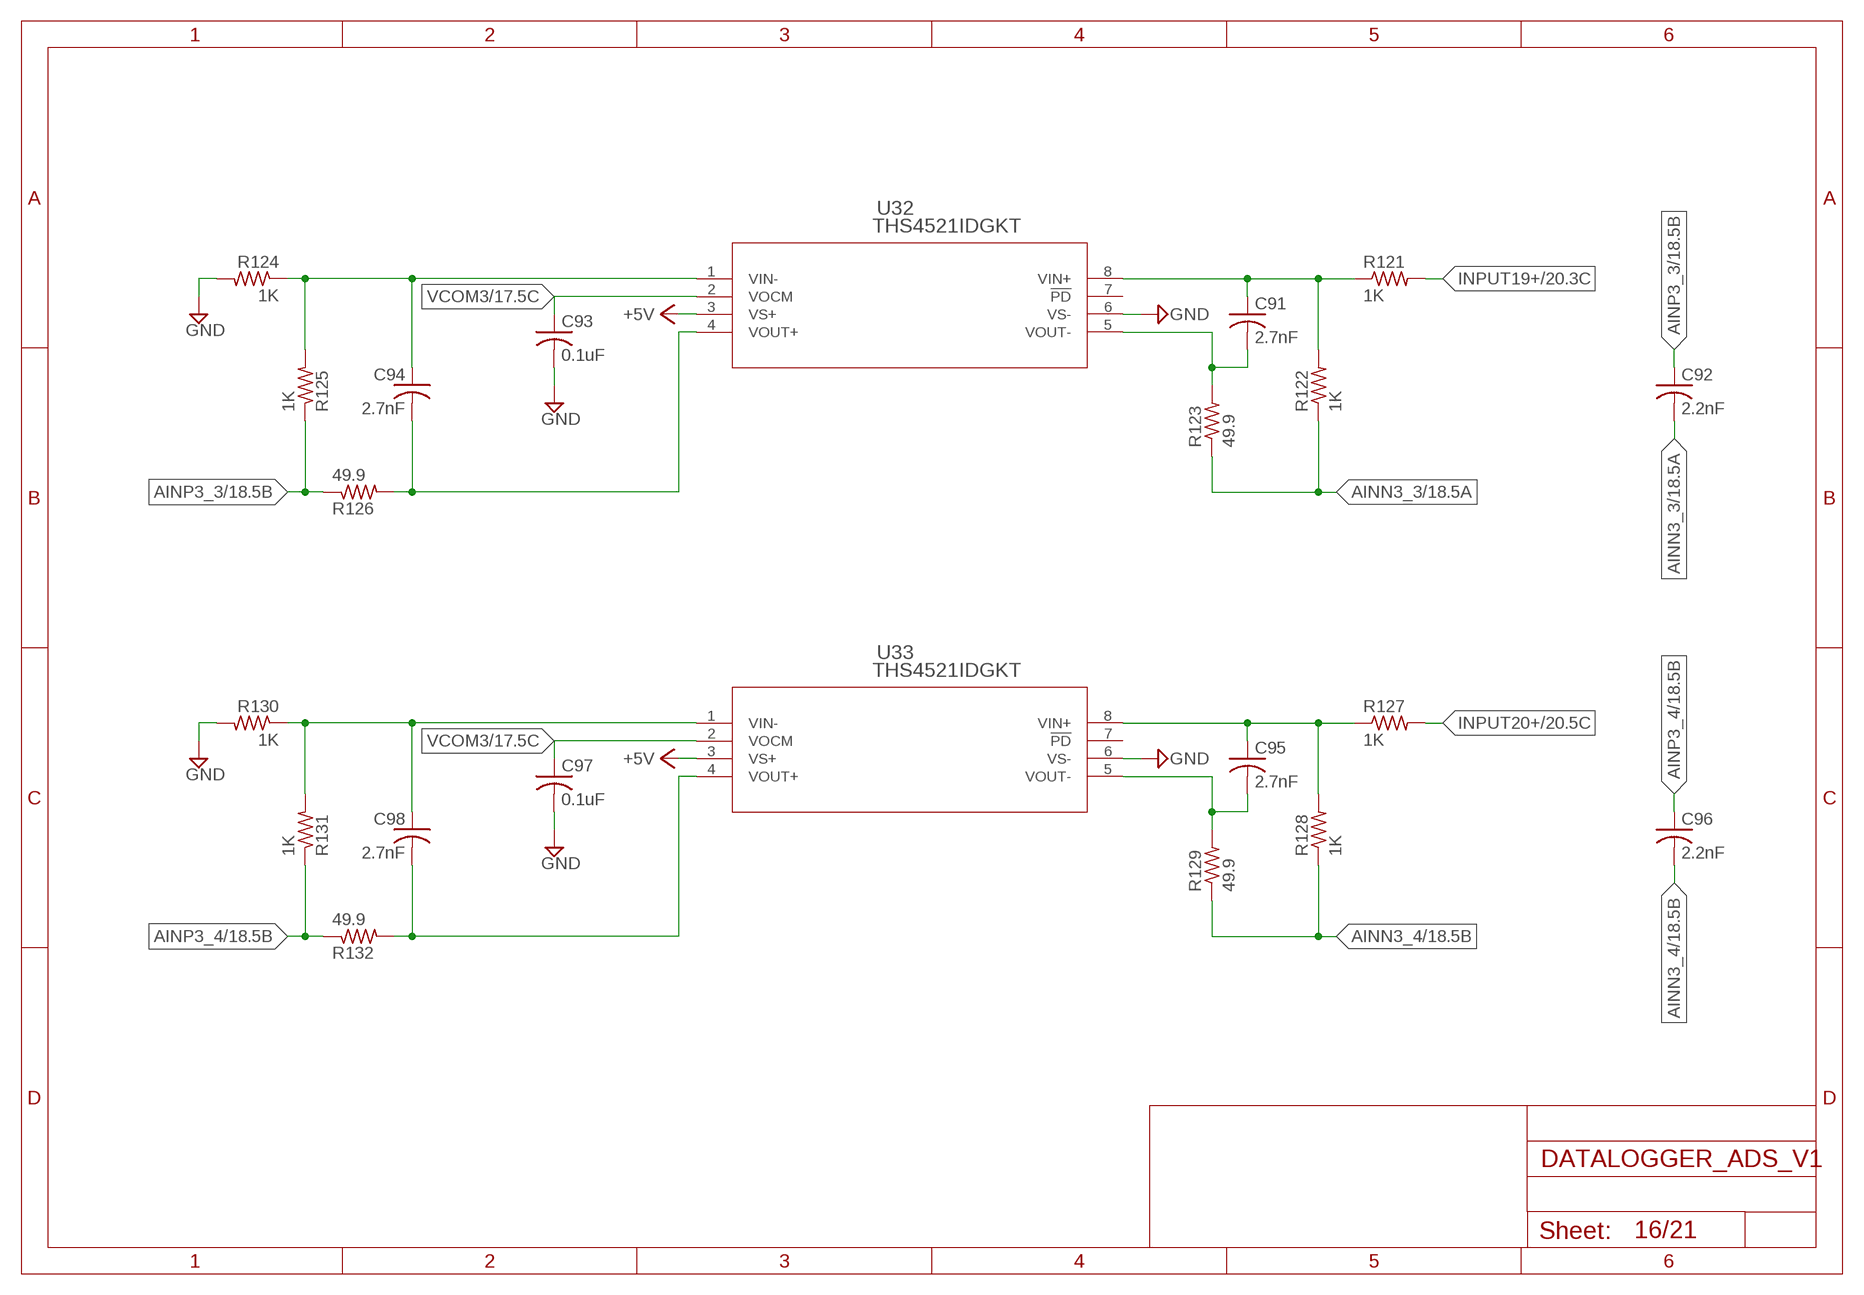
[diagram p15: schematic, sheet 16]
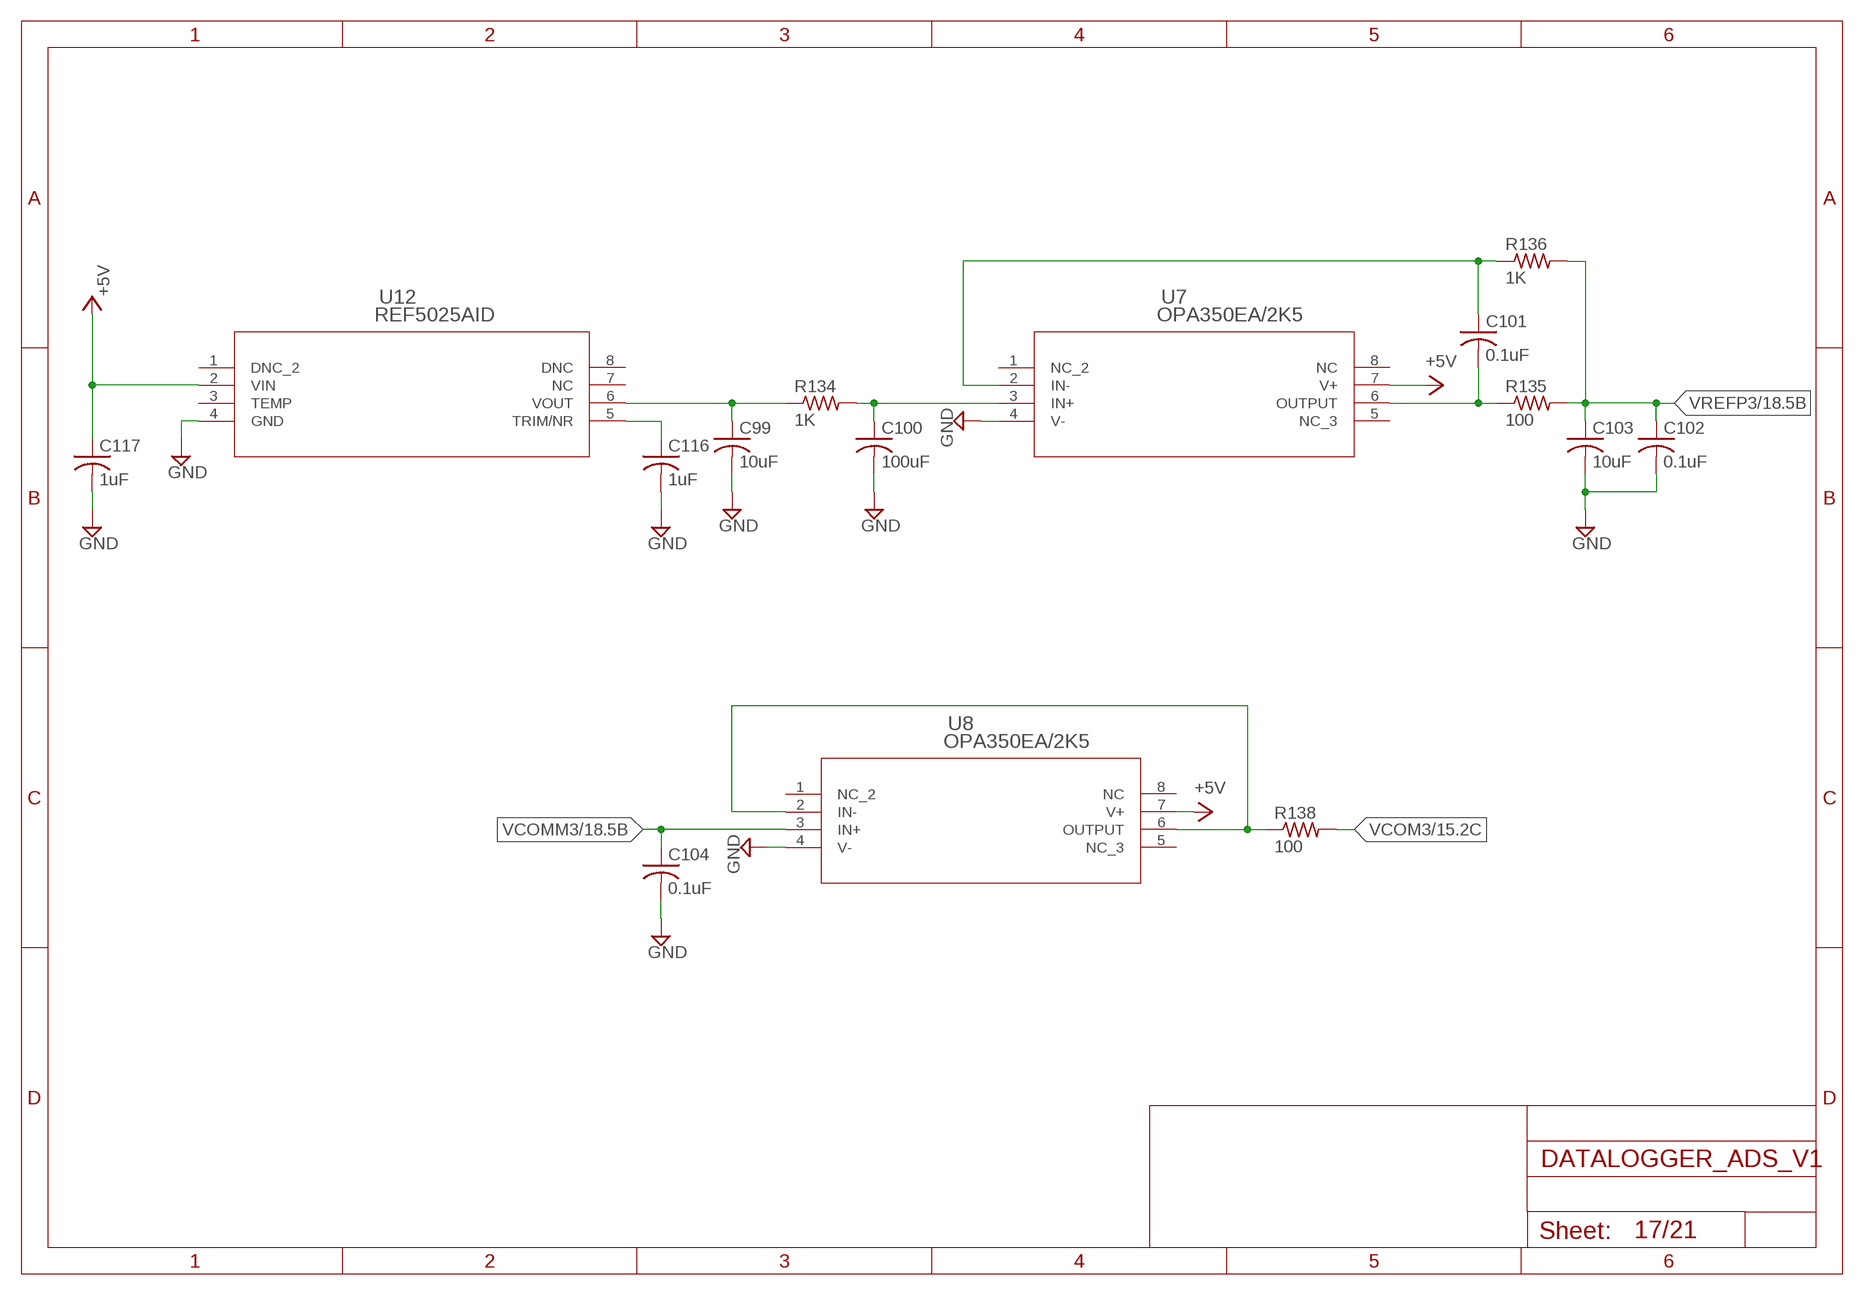
[diagram p16: schematic, sheet 17]
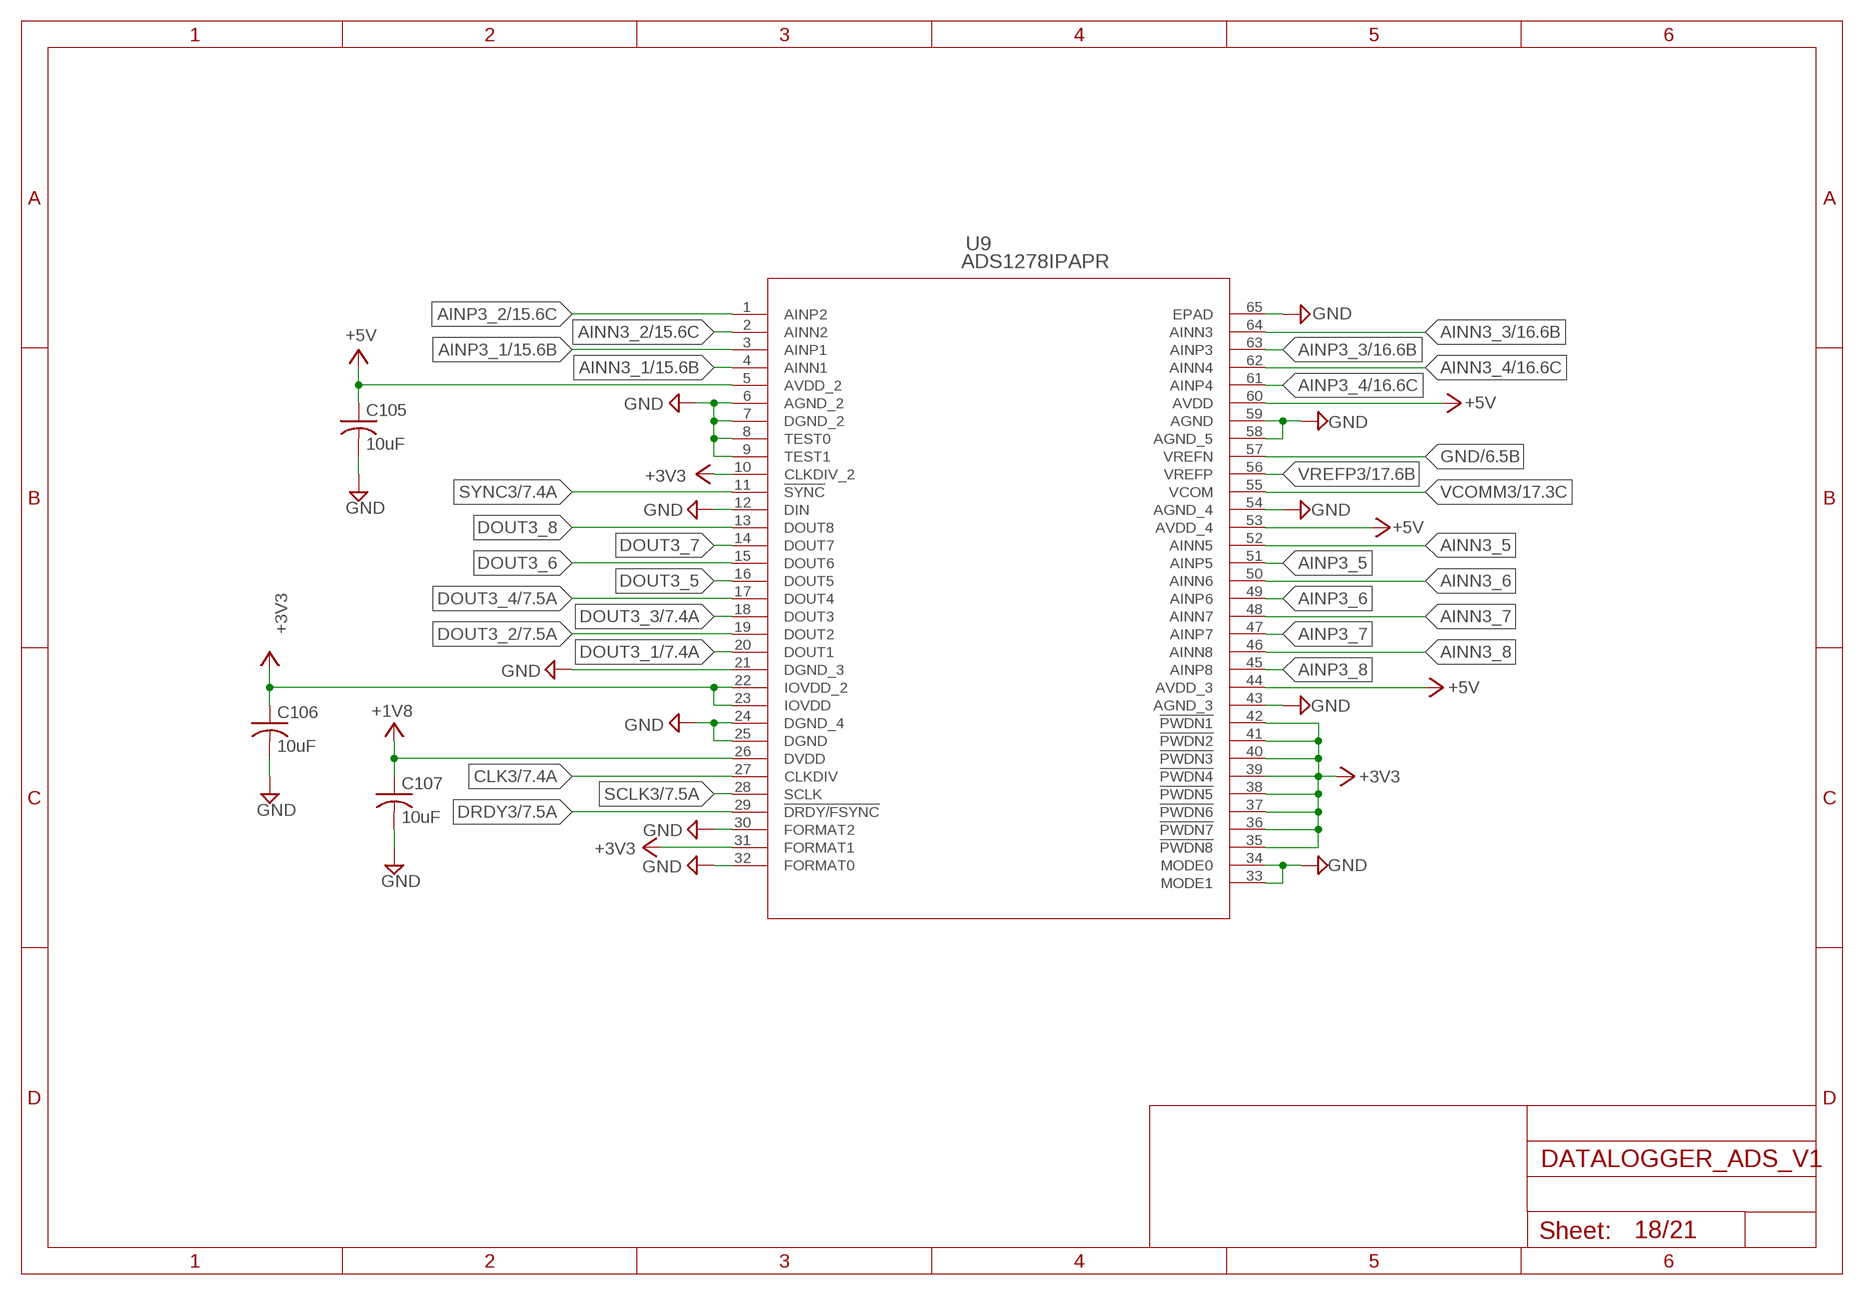
[diagram p17: schematic, sheet 18]
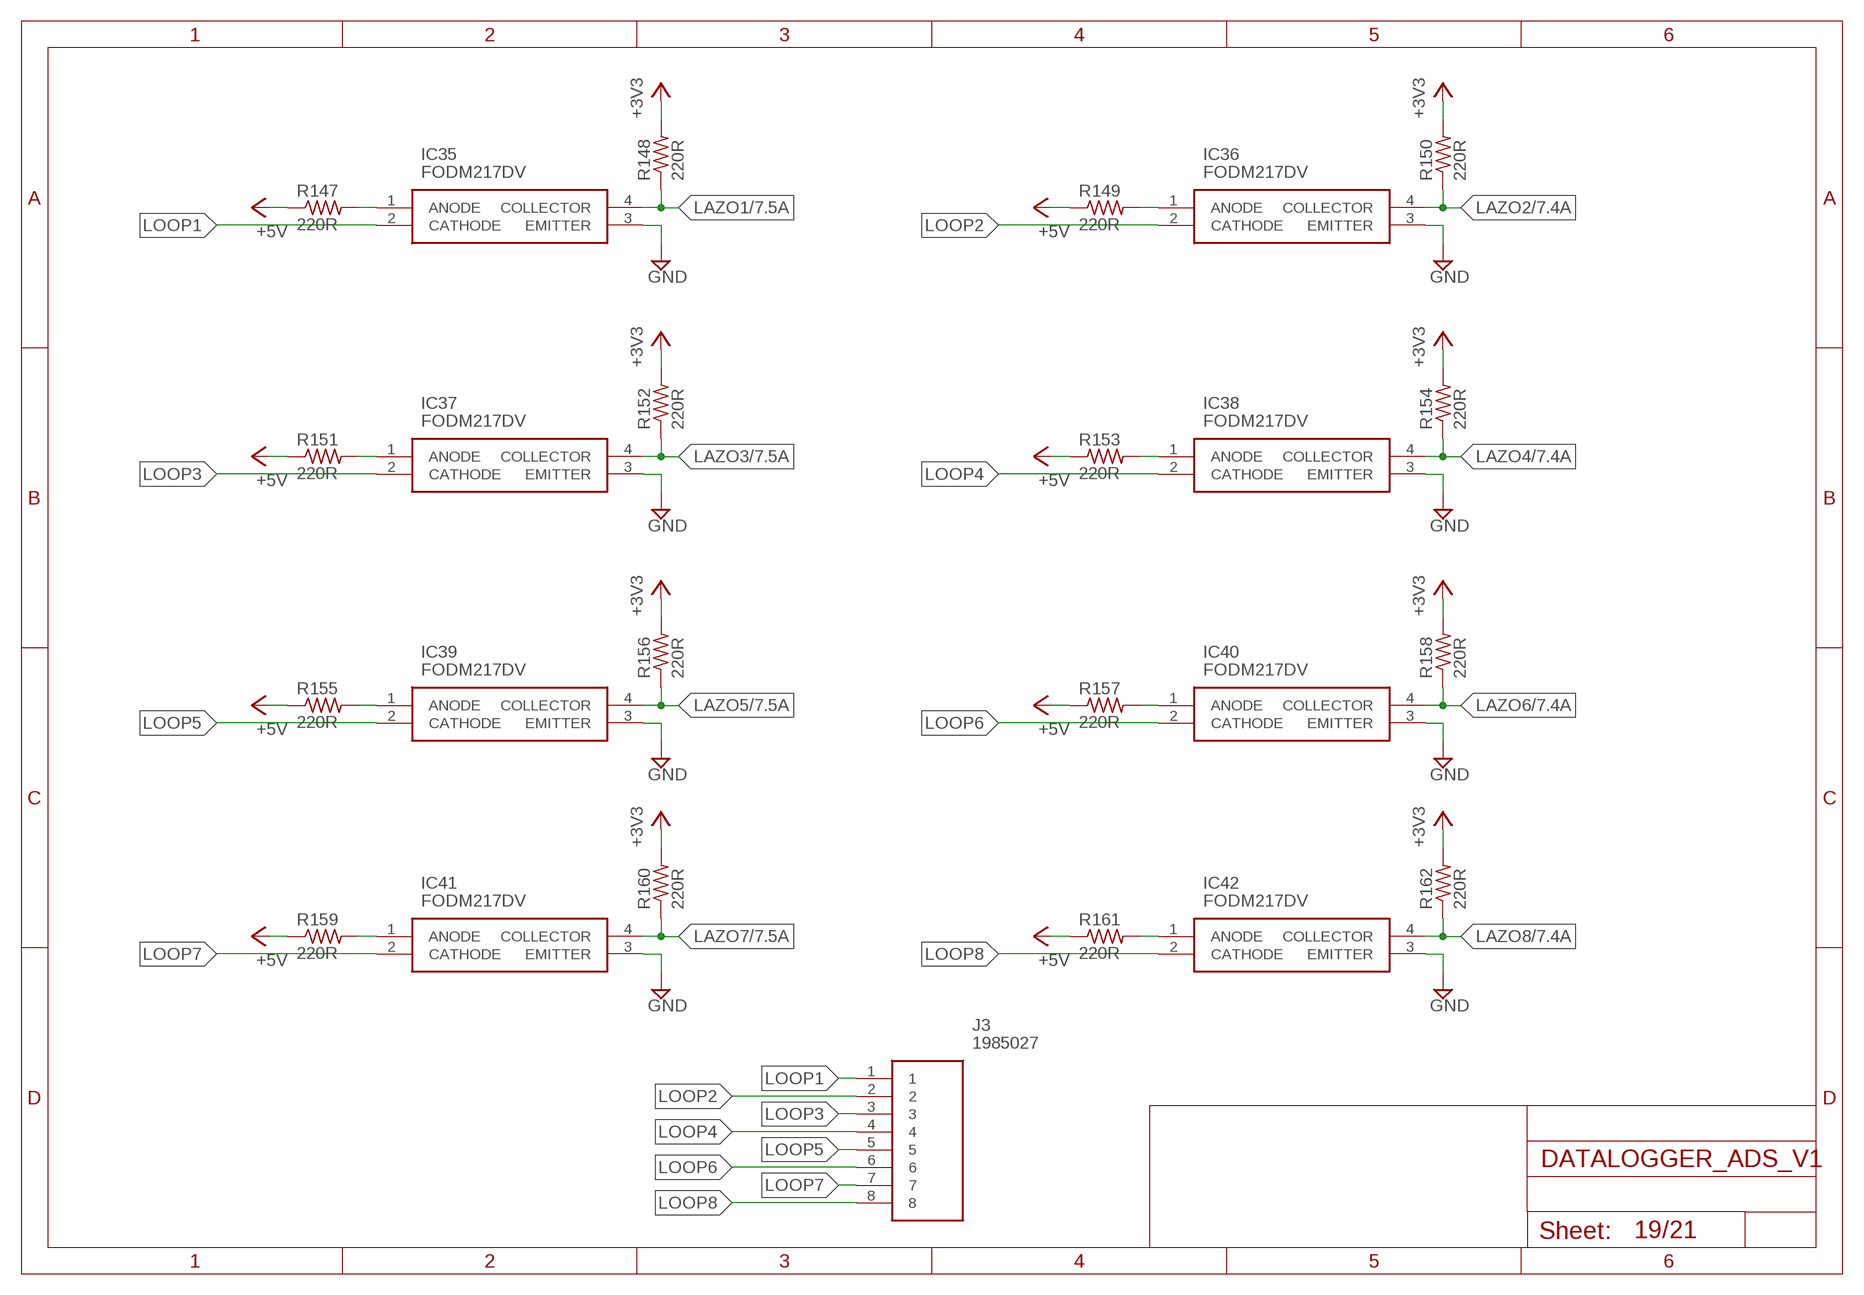
[diagram p18: schematic, sheet 19]
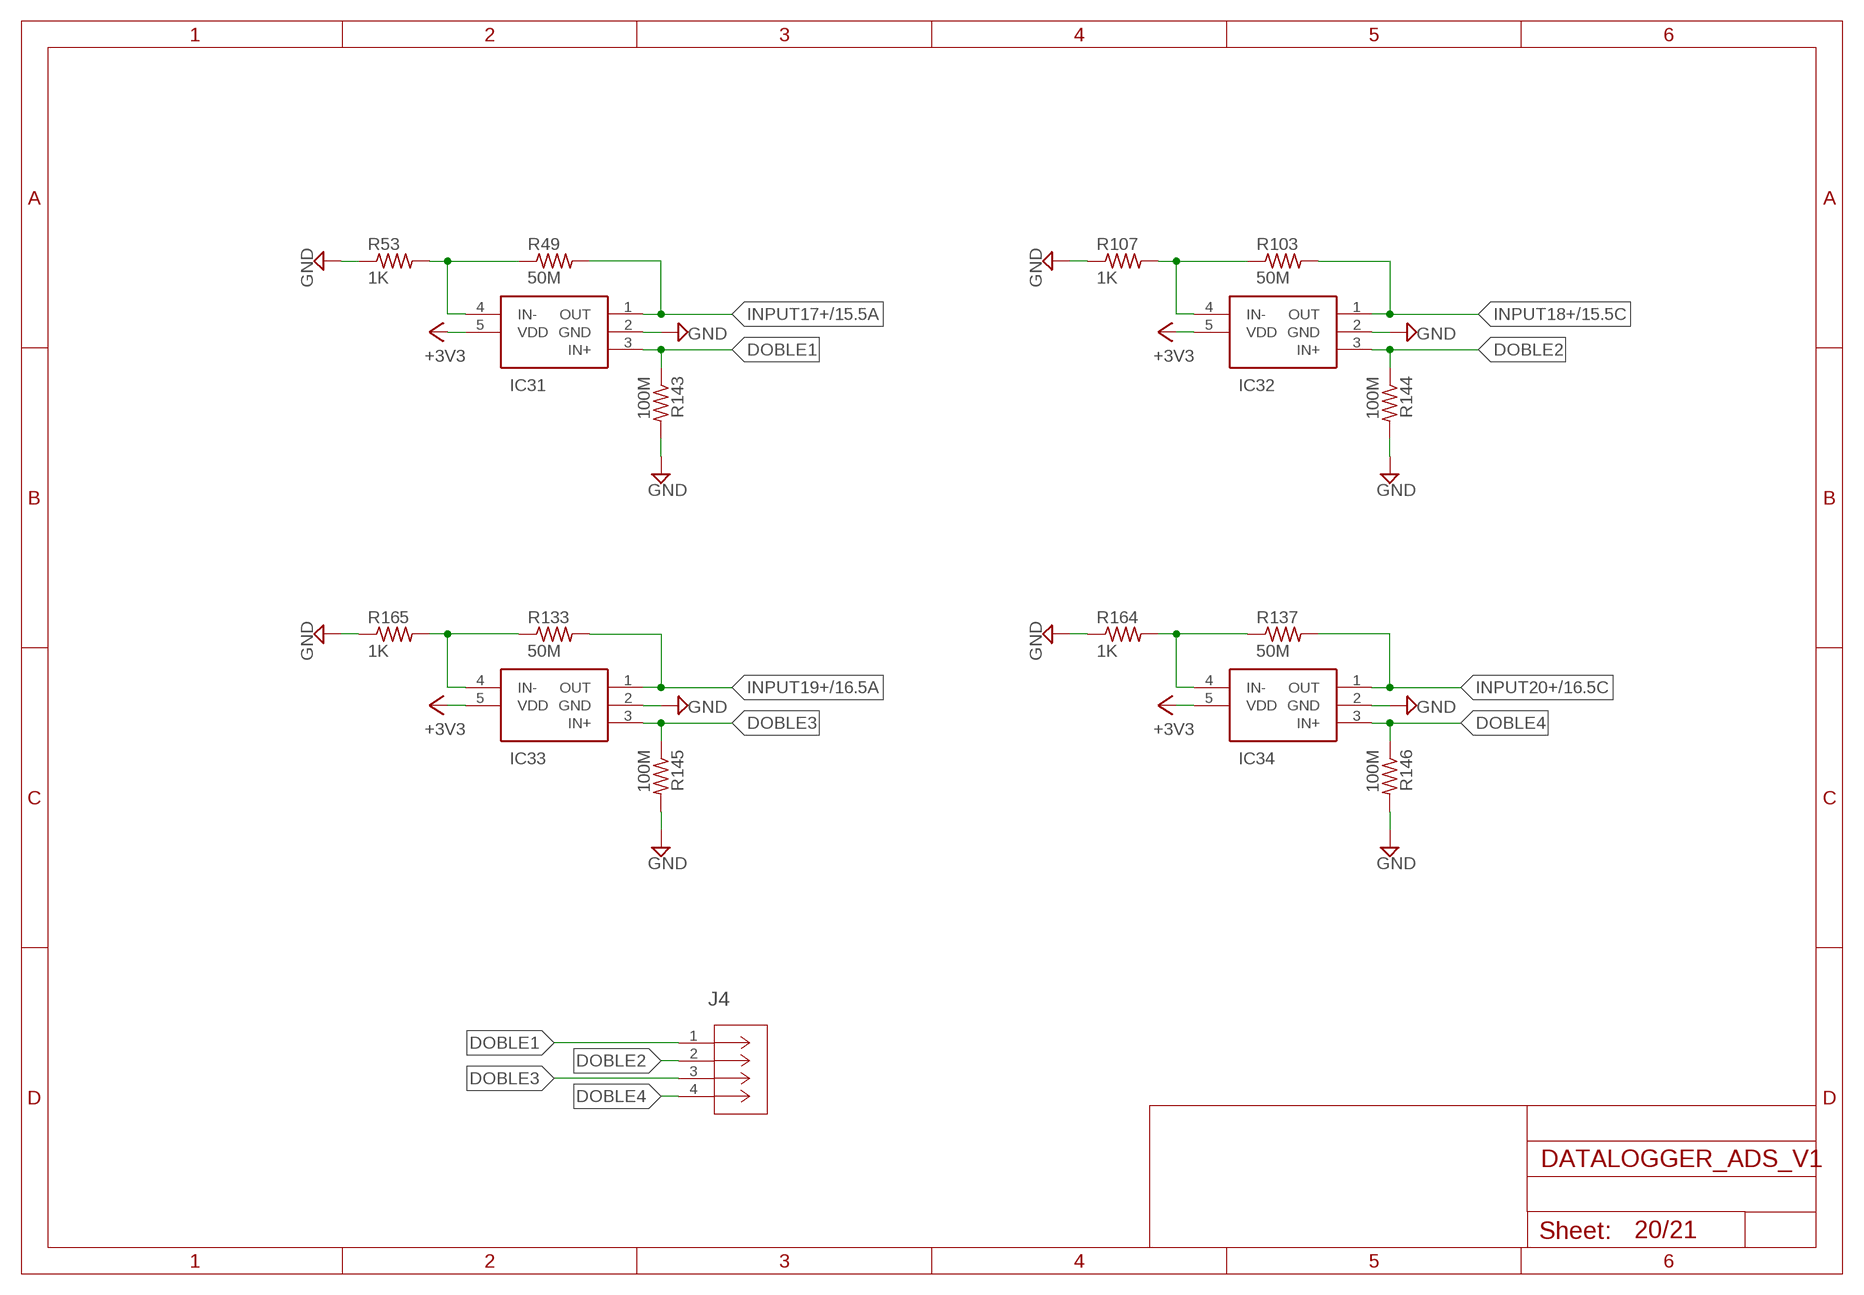
[diagram p19: schematic, sheet 20]
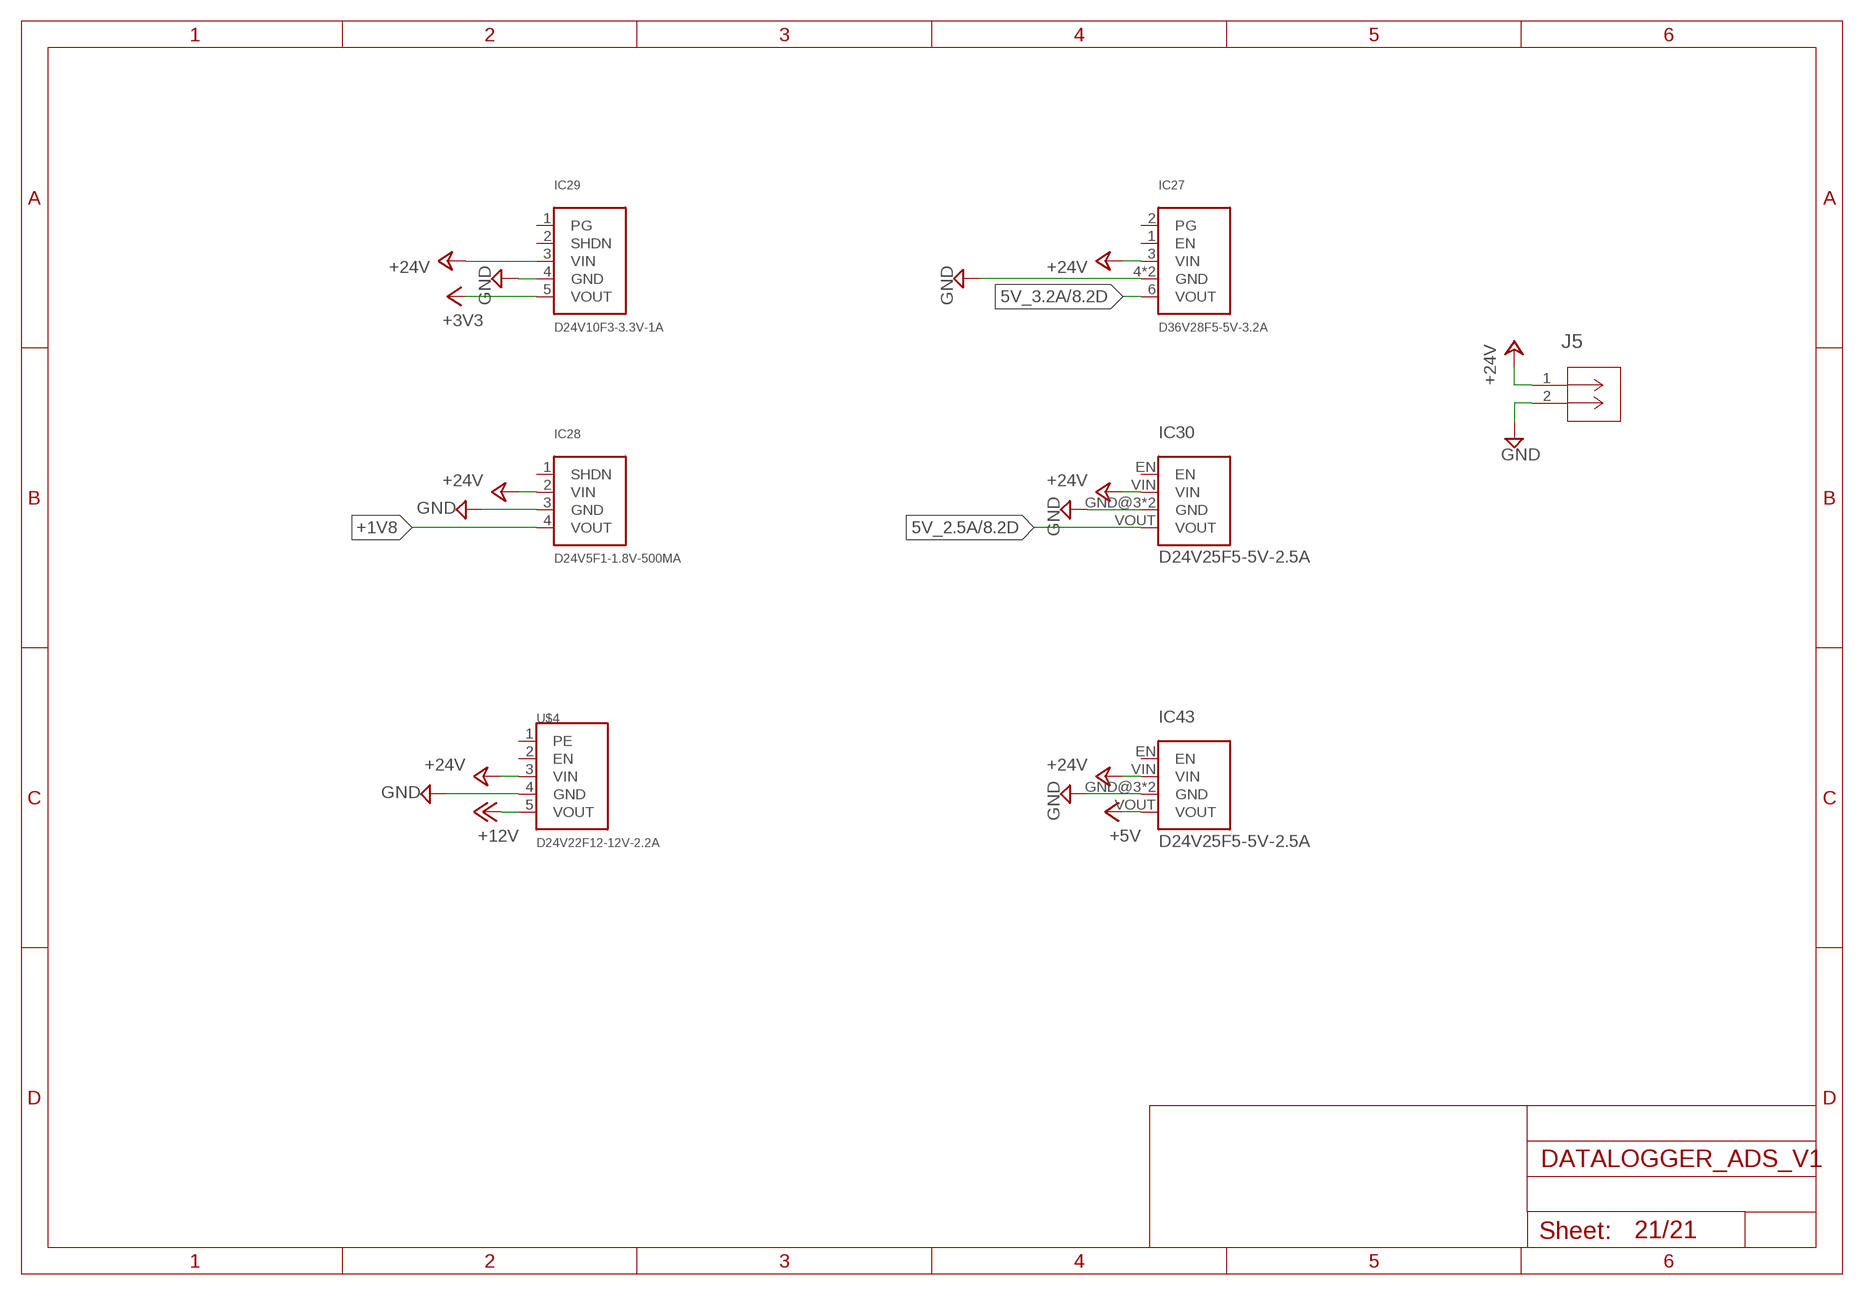
[diagram p20: schematic, sheet 21]

(export (version "E")
  (design (tool "Eeschema 10.0.6"))
  (components
    (comp (ref "C9")
      (value "2.7nF")
      (footprint "eagle-import:C0603")
      (libsource (lib "eagle-import") (part "C-USC0603"))
    )
    (comp (ref "C10")
      (value "2.2nF")
      (footprint "eagle-import:C0603")
      (libsource (lib "eagle-import") (part "C-USC0603"))
    )
    (comp (ref "C11")
      (value "0.1uF")
      (footprint "eagle-import:C0603")
      (libsource (lib "eagle-import") (part "C-USC0603"))
    )
    (comp (ref "C12")
      (value "2.7nF")
      (footprint "eagle-import:C0603")
      (libsource (lib "eagle-import") (part "C-USC0603"))
    )
    (comp (ref "C13")
      (value "2.7nF")
      (footprint "eagle-import:C0603")
      (libsource (lib "eagle-import") (part "C-USC0603"))
    )
    (comp (ref "C14")
      (value "2.2nF")
      (footprint "eagle-import:C0603")
      (libsource (lib "eagle-import") (part "C-USC0603"))
    )
    (comp (ref "C15")
      (value "0.1uF")
      (footprint "eagle-import:C0603")
      (libsource (lib "eagle-import") (part "C-USC0603"))
    )
    (comp (ref "C16")
      (value "2.7nF")
      (footprint "eagle-import:C0603")
      (libsource (lib "eagle-import") (part "C-USC0603"))
    )
    (comp (ref "R13")
      (value "1K")
      (footprint "eagle-import:R0603")
      (libsource (lib "eagle-import") (part "R-US_R0603"))
    )
    (comp (ref "R14")
      (value "1K")
      (footprint "eagle-import:R0603")
      (libsource (lib "eagle-import") (part "R-US_R0603"))
    )
    (comp (ref "R15")
      (value "49.9")
      (footprint "eagle-import:R0603")
      (libsource (lib "eagle-import") (part "R-US_R0603"))
    )
    (comp (ref "R16")
      (value "1K")
      (footprint "eagle-import:R0603")
      (libsource (lib "eagle-import") (part "R-US_R0603"))
    )
    (comp (ref "R17")
      (value "1K")
      (footprint "eagle-import:R0603")
      (libsource (lib "eagle-import") (part "R-US_R0603"))
    )
    (comp (ref "R18")
      (value "49.9")
      (footprint "eagle-import:R0603")
      (libsource (lib "eagle-import") (part "R-US_R0603"))
    )
    (comp (ref "R19")
      (value "1K")
      (footprint "eagle-import:R0603")
      (libsource (lib "eagle-import") (part "R-US_R0603"))
    )
    (comp (ref "R20")
      (value "1K")
      (footprint "eagle-import:R0603")
      (libsource (lib "eagle-import") (part "R-US_R0603"))
    )
    (comp (ref "R21")
      (value "49.9")
      (footprint "eagle-import:R0603")
      (libsource (lib "eagle-import") (part "R-US_R0603"))
    )
    (comp (ref "R22")
      (value "1K")
      (footprint "eagle-import:R0603")
      (libsource (lib "eagle-import") (part "R-US_R0603"))
    )
    (comp (ref "R23")
      (value "1K")
      (footprint "eagle-import:R0603")
      (libsource (lib "eagle-import") (part "R-US_R0603"))
    )
    (comp (ref "R24")
      (value "49.9")
      (footprint "eagle-import:R0603")
      (libsource (lib "eagle-import") (part "R-US_R0603"))
    )
    (comp (ref "U16")
      (value "THS4521IDGKT")
      (footprint "eagle-import:DGK8")
      (fields
        (field (name "GENERIC_PART_NUMBER") "THS4521")
        (field (name "MANUFACTURER") "Texas Instruments")
      )
      (libsource (lib "eagle-import") (part "THS4521IDGKT"))
    )
    (comp (ref "U17")
      (value "THS4521IDGKT")
      (footprint "eagle-import:DGK8")
      (fields
        (field (name "GENERIC_PART_NUMBER") "THS4521")
        (field (name "MANUFACTURER") "Texas Instruments")
      )
      (libsource (lib "eagle-import") (part "THS4521IDGKT"))
    )
    (comp (ref "IC35")
      (value "FODM217DV")
      (footprint "eagle-import:SOIC127P700X220-4N")
      (fields (field (name "MOUSER_PART_NUMBER") "863-FODM217DV"))
      (libsource (lib "eagle-import") (part "FODM217DV"))
    )
    (comp (ref "IC36")
      (value "FODM217DV")
      (footprint "eagle-import:SOIC127P700X220-4N")
      (fields (field (name "MOUSER_PART_NUMBER") "863-FODM217DV"))
      (libsource (lib "eagle-import") (part "FODM217DV"))
    )
    (comp (ref "IC37")
      (value "FODM217DV")
      (footprint "eagle-import:SOIC127P700X220-4N")
      (fields (field (name "MOUSER_PART_NUMBER") "863-FODM217DV"))
      (libsource (lib "eagle-import") (part "FODM217DV"))
    )
    (comp (ref "IC38")
      (value "FODM217DV")
      (footprint "eagle-import:SOIC127P700X220-4N")
      (fields (field (name "MOUSER_PART_NUMBER") "863-FODM217DV"))
      (libsource (lib "eagle-import") (part "FODM217DV"))
    )
    (comp (ref "IC39")
      (value "FODM217DV")
      (footprint "eagle-import:SOIC127P700X220-4N")
      (fields (field (name "MOUSER_PART_NUMBER") "863-FODM217DV"))
      (libsource (lib "eagle-import") (part "FODM217DV"))
    )
    (comp (ref "IC40")
      (value "FODM217DV")
      (footprint "eagle-import:SOIC127P700X220-4N")
      (fields (field (name "MOUSER_PART_NUMBER") "863-FODM217DV"))
      (libsource (lib "eagle-import") (part "FODM217DV"))
    )
    (comp (ref "IC41")
      (value "FODM217DV")
      (footprint "eagle-import:SOIC127P700X220-4N")
      (fields (field (name "MOUSER_PART_NUMBER") "863-FODM217DV"))
      (libsource (lib "eagle-import") (part "FODM217DV"))
    )
    (comp (ref "IC42")
      (value "FODM217DV")
      (footprint "eagle-import:SOIC127P700X220-4N")
      (fields (field (name "MOUSER_PART_NUMBER") "863-FODM217DV"))
      (libsource (lib "eagle-import") (part "FODM217DV"))
    )
    (comp (ref "J3")
      (value "1985027")
      (footprint "eagle-import:1985027")
      (fields (field (name "MOUSER_PART_NUMBER") "651-1985027"))
      (libsource (lib "eagle-import") (part "1985027"))
    )
    (comp (ref "R147")
      (value "220R")
      (footprint "eagle-import:R0805")
      (libsource (lib "eagle-import") (part "R-US_R0805"))
    )
    (comp (ref "R148")
      (value "220R")
      (footprint "eagle-import:R0805")
      (libsource (lib "eagle-import") (part "R-US_R0805"))
    )
    (comp (ref "R149")
      (value "220R")
      (footprint "eagle-import:R0805")
      (libsource (lib "eagle-import") (part "R-US_R0805"))
    )
    (comp (ref "R150")
      (value "220R")
      (footprint "eagle-import:R0805")
      (libsource (lib "eagle-import") (part "R-US_R0805"))
    )
    (comp (ref "R151")
      (value "220R")
      (footprint "eagle-import:R0805")
      (libsource (lib "eagle-import") (part "R-US_R0805"))
    )
    (comp (ref "R152")
      (value "220R")
      (footprint "eagle-import:R0805")
      (libsource (lib "eagle-import") (part "R-US_R0805"))
    )
    (comp (ref "R153")
      (value "220R")
      (footprint "eagle-import:R0805")
      (libsource (lib "eagle-import") (part "R-US_R0805"))
    )
    (comp (ref "R154")
      (value "220R")
      (footprint "eagle-import:R0805")
      (libsource (lib "eagle-import") (part "R-US_R0805"))
    )
    (comp (ref "R155")
      (value "220R")
      (footprint "eagle-import:R0805")
      (libsource (lib "eagle-import") (part "R-US_R0805"))
    )
    (comp (ref "R156")
      (value "220R")
      (footprint "eagle-import:R0805")
      (libsource (lib "eagle-import") (part "R-US_R0805"))
    )
    (comp (ref "R157")
      (value "220R")
      (footprint "eagle-import:R0805")
      (libsource (lib "eagle-import") (part "R-US_R0805"))
    )
    (comp (ref "R158")
      (value "220R")
      (footprint "eagle-import:R0805")
      (libsource (lib "eagle-import") (part "R-US_R0805"))
    )
    (comp (ref "R159")
      (value "220R")
      (footprint "eagle-import:R0805")
      (libsource (lib "eagle-import") (part "R-US_R0805"))
    )
    (comp (ref "R160")
      (value "220R")
      (footprint "eagle-import:R0805")
      (libsource (lib "eagle-import") (part "R-US_R0805"))
    )
    (comp (ref "R161")
      (value "220R")
      (footprint "eagle-import:R0805")
      (libsource (lib "eagle-import") (part "R-US_R0805"))
    )
    (comp (ref "R162")
      (value "220R")
      (footprint "eagle-import:R0805")
      (libsource (lib "eagle-import") (part "R-US_R0805"))
    )
    (comp (ref "C33")
      (value "10uF")
      (footprint "eagle-import:C0603")
      (libsource (lib "eagle-import") (part "C-USC0603"))
    )
    (comp (ref "C34")
      (value "100uF")
      (footprint "eagle-import:C1206")
      (libsource (lib "eagle-import") (part "C-USC1206"))
    )
    (comp (ref "C35")
      (value "0.1uF")
      (footprint "eagle-import:C0603")
      (libsource (lib "eagle-import") (part "C-USC0603"))
    )
    (comp (ref "C36")
      (value "0.1uF")
      (footprint "eagle-import:C0603")
      (libsource (lib "eagle-import") (part "C-USC0603"))
    )
    (comp (ref "C37")
      (value "10uF")
      (footprint "eagle-import:C0603")
      (libsource (lib "eagle-import") (part "C-USC0603"))
    )
    (comp (ref "C38")
      (value "0.1uF")
      (footprint "eagle-import:C0603")
      (libsource (lib "eagle-import") (part "C-USC0603"))
    )
    (comp (ref "C114")
      (value "1uF")
      (footprint "eagle-import:C0603")
      (libsource (lib "eagle-import") (part "C-USC0603"))
    )
    (comp (ref "C115")
      (value "1uF")
      (footprint "eagle-import:C0603")
      (libsource (lib "eagle-import") (part "C-USC0603"))
    )
    (comp (ref "R50")
      (value "1K")
      (footprint "eagle-import:R0603")
      (libsource (lib "eagle-import") (part "R-US_R0603"))
    )
    (comp (ref "R51")
      (value "100")
      (footprint "eagle-import:R0603")
      (libsource (lib "eagle-import") (part "R-US_R0603"))
    )
    (comp (ref "R52")
      (value "1K")
      (footprint "eagle-import:R0603")
      (libsource (lib "eagle-import") (part "R-US_R0603"))
    )
    (comp (ref "R54")
      (value "100")
      (footprint "eagle-import:R0603")
      (libsource (lib "eagle-import") (part "R-US_R0603"))
    )
    (comp (ref "U1")
      (value "OPA350EA/2K5")
      (footprint "eagle-import:DGK8_TEX")
      (fields
        (field (name "MANUFACTURER") "Texas Instruments")
        (field (name "COPYRIGHT") "Copyright (C) 2018 Accelerated Designs. All rights reserved")
      )
      (libsource (lib "eagle-import") (part "OPA350EA/2K5"))
    )
    (comp (ref "U2")
      (value "OPA350EA/2K5")
      (footprint "eagle-import:DGK8_TEX")
      (fields
        (field (name "MANUFACTURER") "Texas Instruments")
        (field (name "COPYRIGHT") "Copyright (C) 2018 Accelerated Designs. All rights reserved")
      )
      (libsource (lib "eagle-import") (part "OPA350EA/2K5"))
    )
    (comp (ref "U3")
      (value "REF5025AID")
      (footprint "eagle-import:D8")
      (fields
        (field (name "GENERIC_PART_NUMBER") "REF5025")
        (field (name "MANUFACTURER") "Texas Instruments")
      )
      (libsource (lib "eagle-import") (part "REF5025AID"))
    )
    (comp (ref "C17")
      (value "2.7nF")
      (footprint "eagle-import:C0603")
      (libsource (lib "eagle-import") (part "C-USC0603"))
    )
    (comp (ref "C18")
      (value "2.2nF")
      (footprint "eagle-import:C0603")
      (libsource (lib "eagle-import") (part "C-USC0603"))
    )
    (comp (ref "C19")
      (value "0.1uF")
      (footprint "eagle-import:C0603")
      (libsource (lib "eagle-import") (part "C-USC0603"))
    )
    (comp (ref "C20")
      (value "2.7nF")
      (footprint "eagle-import:C0603")
      (libsource (lib "eagle-import") (part "C-USC0603"))
    )
    (comp (ref "C21")
      (value "2.7nF")
      (footprint "eagle-import:C0603")
      (libsource (lib "eagle-import") (part "C-USC0603"))
    )
    (comp (ref "C22")
      (value "2.2nF")
      (footprint "eagle-import:C0603")
      (libsource (lib "eagle-import") (part "C-USC0603"))
    )
    (comp (ref "C23")
      (value "0.1uF")
      (footprint "eagle-import:C0603")
      (libsource (lib "eagle-import") (part "C-USC0603"))
    )
    (comp (ref "C24")
      (value "2.7nF")
      (footprint "eagle-import:C0603")
      (libsource (lib "eagle-import") (part "C-USC0603"))
    )
    (comp (ref "R25")
      (value "1K")
      (footprint "eagle-import:R0603")
      (libsource (lib "eagle-import") (part "R-US_R0603"))
    )
    (comp (ref "R26")
      (value "1K")
      (footprint "eagle-import:R0603")
      (libsource (lib "eagle-import") (part "R-US_R0603"))
    )
    (comp (ref "R27")
      (value "49.9")
      (footprint "eagle-import:R0603")
      (libsource (lib "eagle-import") (part "R-US_R0603"))
    )
    (comp (ref "R28")
      (value "1K")
      (footprint "eagle-import:R0603")
      (libsource (lib "eagle-import") (part "R-US_R0603"))
    )
    (comp (ref "R29")
      (value "1K")
      (footprint "eagle-import:R0603")
      (libsource (lib "eagle-import") (part "R-US_R0603"))
    )
    (comp (ref "R30")
      (value "49.9")
      (footprint "eagle-import:R0603")
      (libsource (lib "eagle-import") (part "R-US_R0603"))
    )
    (comp (ref "R31")
      (value "1K")
      (footprint "eagle-import:R0603")
      (libsource (lib "eagle-import") (part "R-US_R0603"))
    )
    (comp (ref "R32")
      (value "1K")
      (footprint "eagle-import:R0603")
      (libsource (lib "eagle-import") (part "R-US_R0603"))
    )
    (comp (ref "R33")
      (value "49.9")
      (footprint "eagle-import:R0603")
      (libsource (lib "eagle-import") (part "R-US_R0603"))
    )
    (comp (ref "R34")
      (value "1K")
      (footprint "eagle-import:R0603")
      (libsource (lib "eagle-import") (part "R-US_R0603"))
    )
    (comp (ref "R35")
      (value "1K")
      (footprint "eagle-import:R0603")
      (libsource (lib "eagle-import") (part "R-US_R0603"))
    )
    (comp (ref "R36")
      (value "49.9")
      (footprint "eagle-import:R0603")
      (libsource (lib "eagle-import") (part "R-US_R0603"))
    )
    (comp (ref "U18")
      (value "THS4521IDGKT")
      (footprint "eagle-import:DGK8")
      (fields
        (field (name "GENERIC_PART_NUMBER") "THS4521")
        (field (name "MANUFACTURER") "Texas Instruments")
      )
      (libsource (lib "eagle-import") (part "THS4521IDGKT"))
    )
    (comp (ref "U19")
      (value "THS4521IDGKT")
      (footprint "eagle-import:DGK8")
      (fields
        (field (name "GENERIC_PART_NUMBER") "THS4521")
        (field (name "MANUFACTURER") "Texas Instruments")
      )
      (libsource (lib "eagle-import") (part "THS4521IDGKT"))
    )
    (comp (ref "C74")
      (value "10uF")
      (footprint "eagle-import:C0603")
      (libsource (lib "eagle-import") (part "C-USC0603"))
    )
    (comp (ref "C75")
      (value "100uF")
      (footprint "eagle-import:C1206")
      (libsource (lib "eagle-import") (part "C-USC1206"))
    )
    (comp (ref "C76")
      (value "0.1uF")
      (footprint "eagle-import:C0603")
      (libsource (lib "eagle-import") (part "C-USC0603"))
    )
    (comp (ref "C77")
      (value "0.1uF")
      (footprint "eagle-import:C0603")
      (libsource (lib "eagle-import") (part "C-USC0603"))
    )
    (comp (ref "C78")
      (value "10uF")
      (footprint "eagle-import:C0603")
      (libsource (lib "eagle-import") (part "C-USC0603"))
    )
    (comp (ref "C79")
      (value "0.1uF")
      (footprint "eagle-import:C0603")
      (libsource (lib "eagle-import") (part "C-USC0603"))
    )
    (comp (ref "C118")
      (value "1uF")
      (footprint "eagle-import:C0603")
      (libsource (lib "eagle-import") (part "C-USC0603"))
    )
    (comp (ref "C119")
      (value "1uF")
      (footprint "eagle-import:C0603")
      (libsource (lib "eagle-import") (part "C-USC0603"))
    )
    (comp (ref "R104")
      (value "1K")
      (footprint "eagle-import:R0603")
      (libsource (lib "eagle-import") (part "R-US_R0603"))
    )
    (comp (ref "R105")
      (value "100")
      (footprint "eagle-import:R0603")
      (libsource (lib "eagle-import") (part "R-US_R0603"))
    )
    (comp (ref "R106")
      (value "1K")
      (footprint "eagle-import:R0603")
      (libsource (lib "eagle-import") (part "R-US_R0603"))
    )
    (comp (ref "R108")
      (value "100")
      (footprint "eagle-import:R0603")
      (libsource (lib "eagle-import") (part "R-US_R0603"))
    )
    (comp (ref "U4")
      (value "OPA350EA/2K5")
      (footprint "eagle-import:DGK8_TEX")
      (fields
        (field (name "MANUFACTURER") "Texas Instruments")
        (field (name "COPYRIGHT") "Copyright (C) 2018 Accelerated Designs. All rights reserved")
      )
      (libsource (lib "eagle-import") (part "OPA350EA/2K5"))
    )
    (comp (ref "U5")
      (value "OPA350EA/2K5")
      (footprint "eagle-import:DGK8_TEX")
      (fields
        (field (name "MANUFACTURER") "Texas Instruments")
        (field (name "COPYRIGHT") "Copyright (C) 2018 Accelerated Designs. All rights reserved")
      )
      (libsource (lib "eagle-import") (part "OPA350EA/2K5"))
    )
    (comp (ref "U13")
      (value "REF5025AID")
      (footprint "eagle-import:D8")
      (fields
        (field (name "GENERIC_PART_NUMBER") "REF5025")
        (field (name "MANUFACTURER") "Texas Instruments")
      )
      (libsource (lib "eagle-import") (part "REF5025AID"))
    )
    (comp (ref "C42")
      (value "2.7nF")
      (footprint "eagle-import:C0603")
      (libsource (lib "eagle-import") (part "C-USC0603"))
    )
    (comp (ref "C43")
      (value "2.2nF")
      (footprint "eagle-import:C0603")
      (libsource (lib "eagle-import") (part "C-USC0603"))
    )
    (comp (ref "C44")
      (value "0.1uF")
      (footprint "eagle-import:C0603")
      (libsource (lib "eagle-import") (part "C-USC0603"))
    )
    (comp (ref "C45")
      (value "2.7nF")
      (footprint "eagle-import:C0603")
      (libsource (lib "eagle-import") (part "C-USC0603"))
    )
    (comp (ref "C46")
      (value "2.7nF")
      (footprint "eagle-import:C0603")
      (libsource (lib "eagle-import") (part "C-USC0603"))
    )
    (comp (ref "C47")
      (value "2.2nF")
      (footprint "eagle-import:C0603")
      (libsource (lib "eagle-import") (part "C-USC0603"))
    )
    (comp (ref "C48")
      (value "0.1uF")
      (footprint "eagle-import:C0603")
      (libsource (lib "eagle-import") (part "C-USC0603"))
    )
    (comp (ref "C49")
      (value "2.7nF")
      (footprint "eagle-import:C0603")
      (libsource (lib "eagle-import") (part "C-USC0603"))
    )
    (comp (ref "R55")
      (value "1K")
      (footprint "eagle-import:R0603")
      (libsource (lib "eagle-import") (part "R-US_R0603"))
    )
    (comp (ref "R56")
      (value "1K")
      (footprint "eagle-import:R0603")
      (libsource (lib "eagle-import") (part "R-US_R0603"))
    )
    (comp (ref "R57")
      (value "49.9")
      (footprint "eagle-import:R0603")
      (libsource (lib "eagle-import") (part "R-US_R0603"))
    )
    (comp (ref "R58")
      (value "1K")
      (footprint "eagle-import:R0603")
      (libsource (lib "eagle-import") (part "R-US_R0603"))
    )
    (comp (ref "R59")
      (value "1K")
      (footprint "eagle-import:R0603")
      (libsource (lib "eagle-import") (part "R-US_R0603"))
    )
    (comp (ref "R60")
      (value "49.9")
      (footprint "eagle-import:R0603")
      (libsource (lib "eagle-import") (part "R-US_R0603"))
    )
    (comp (ref "R61")
      (value "1K")
      (footprint "eagle-import:R0603")
      (libsource (lib "eagle-import") (part "R-US_R0603"))
    )
    (comp (ref "R62")
      (value "1K")
      (footprint "eagle-import:R0603")
      (libsource (lib "eagle-import") (part "R-US_R0603"))
    )
    (comp (ref "R63")
      (value "49.9")
      (footprint "eagle-import:R0603")
      (libsource (lib "eagle-import") (part "R-US_R0603"))
    )
    (comp (ref "R64")
      (value "1K")
      (footprint "eagle-import:R0603")
      (libsource (lib "eagle-import") (part "R-US_R0603"))
    )
    (comp (ref "R65")
      (value "1K")
      (footprint "eagle-import:R0603")
      (libsource (lib "eagle-import") (part "R-US_R0603"))
    )
    (comp (ref "R66")
      (value "49.9")
      (footprint "eagle-import:R0603")
      (libsource (lib "eagle-import") (part "R-US_R0603"))
    )
    (comp (ref "U22")
      (value "THS4521IDGKT")
      (footprint "eagle-import:DGK8")
      (fields
        (field (name "GENERIC_PART_NUMBER") "THS4521")
        (field (name "MANUFACTURER") "Texas Instruments")
      )
      (libsource (lib "eagle-import") (part "THS4521IDGKT"))
    )
    (comp (ref "U23")
      (value "THS4521IDGKT")
      (footprint "eagle-import:DGK8")
      (fields
        (field (name "GENERIC_PART_NUMBER") "THS4521")
        (field (name "MANUFACTURER") "Texas Instruments")
      )
      (libsource (lib "eagle-import") (part "THS4521IDGKT"))
    )
    (comp (ref "IC1")
      (value "DS3231")
      (footprint "eagle-import:DS3231")
      (libsource (lib "eagle-import") (part "DS3231"))
    )
    (comp (ref "J1")
      (value "22-29-2021")
      (footprint "eagle-import:SHDR2W64P0X254_1X2_508X580X117")
      (fields (field (name "MOUSER_PART_NUMBER") "538-22-29-2021"))
      (libsource (lib "eagle-import") (part "22-29-2021"))
    )
    (comp (ref "J2")
      (value "22-29-2021")
      (footprint "eagle-import:SHDR2W64P0X254_1X2_508X580X117")
      (fields (field (name "MOUSER_PART_NUMBER") "538-22-29-2021"))
      (libsource (lib "eagle-import") (part "22-29-2021"))
    )
    (comp (ref "J6")
      (value "22-29-2021")
      (footprint "eagle-import:SHDR2W64P0X254_1X2_508X580X117")
      (fields (field (name "MOUSER_PART_NUMBER") "538-22-29-2021"))
      (libsource (lib "eagle-import") (part "22-29-2021"))
    )
    (comp (ref "JP4")
      (value "PINHD-2X20")
      (footprint "eagle-import:2X20")
      (libsource (lib "eagle-import") (part "PINHD-2X20"))
    )
    (comp (ref "JP5")
      (value "PINHD-1X3")
      (footprint "eagle-import:1X03")
      (libsource (lib "eagle-import") (part "PINHD-1X3"))
    )
    (comp (ref "JP6")
      (value "PINHD-2X5")
      (footprint "eagle-import:2X05")
      (libsource (lib "eagle-import") (part "PINHD-2X5"))
    )
    (comp (ref "R139")
      (value "330R")
      (footprint "eagle-import:R0603")
      (libsource (lib "eagle-import") (part "R-US_R0603"))
    )
    (comp (ref "R140")
      (value "330R")
      (footprint "eagle-import:R0603")
      (libsource (lib "eagle-import") (part "R-US_R0603"))
    )
    (comp (ref "R141")
      (value "330R")
      (footprint "eagle-import:R0603")
      (libsource (lib "eagle-import") (part "R-US_R0603"))
    )
    (comp (ref "R142")
      (value "330R")
      (footprint "eagle-import:R0603")
      (libsource (lib "eagle-import") (part "R-US_R0603"))
    )
    (comp (ref "R163")
      (value "330R")
      (footprint "eagle-import:R0603")
      (libsource (lib "eagle-import") (part "R-US_R0603"))
    )
    (comp (ref "IC27")
      (value "D36V28F5-5V-3.2A")
      (footprint "eagle-import:D36V28F5-5V-3.2A")
      (libsource (lib "eagle-import") (part "D36V28F5-5V-3.2A"))
    )
    (comp (ref "IC28")
      (value "D24V5F1-1.8V-500MA")
      (footprint "eagle-import:D24V5F1")
      (libsource (lib "eagle-import") (part "D24V5F1-1.8V-500MA"))
    )
    (comp (ref "IC29")
      (value "D24V10F3-3.3V-1A")
      (footprint "eagle-import:D24V10F3-3.3V-1A")
      (libsource (lib "eagle-import") (part "D24V10F3-3.3V-1A"))
    )
    (comp (ref "IC30")
      (value "D24V25F5-5V-2.5A")
      (footprint "eagle-import:D24V25F5-5V-2.5A")
      (libsource (lib "eagle-import") (part "D24V25F5-5V-2.5A"))
    )
    (comp (ref "IC43")
      (value "D24V25F5-5V-2.5A")
      (footprint "eagle-import:D24V25F5-5V-2.5A")
      (libsource (lib "eagle-import") (part "D24V25F5-5V-2.5A"))
    )
    (comp (ref "J5")
      (value "1755736")
      (footprint "eagle-import:CONN_1924305")
      (fields (field (name "COPYRIGHT") "Copyright (C) 2018 Accelerated Designs. All rights reserved"))
      (libsource (lib "eagle-import") (part "1755736"))
    )
    (comp (ref "U$4")
      (value "D24V22F12-12V-2.2A")
      (footprint "eagle-import:D24V22F12")
      (libsource (lib "eagle-import") (part "D24V22F12-12V-2.2A"))
    )
    (comp (ref "C50")
      (value "2.7nF")
      (footprint "eagle-import:C0603")
      (libsource (lib "eagle-import") (part "C-USC0603"))
    )
    (comp (ref "C51")
      (value "2.2nF")
      (footprint "eagle-import:C0603")
      (libsource (lib "eagle-import") (part "C-USC0603"))
    )
    (comp (ref "C52")
      (value "0.1uF")
      (footprint "eagle-import:C0603")
      (libsource (lib "eagle-import") (part "C-USC0603"))
    )
    (comp (ref "C53")
      (value "2.7nF")
      (footprint "eagle-import:C0603")
      (libsource (lib "eagle-import") (part "C-USC0603"))
    )
    (comp (ref "C54")
      (value "2.7nF")
      (footprint "eagle-import:C0603")
      (libsource (lib "eagle-import") (part "C-USC0603"))
    )
    (comp (ref "C55")
      (value "2.2nF")
      (footprint "eagle-import:C0603")
      (libsource (lib "eagle-import") (part "C-USC0603"))
    )
    (comp (ref "C56")
      (value "0.1uF")
      (footprint "eagle-import:C0603")
      (libsource (lib "eagle-import") (part "C-USC0603"))
    )
    (comp (ref "C57")
      (value "2.7nF")
      (footprint "eagle-import:C0603")
      (libsource (lib "eagle-import") (part "C-USC0603"))
    )
    (comp (ref "R67")
      (value "1K")
      (footprint "eagle-import:R0603")
      (libsource (lib "eagle-import") (part "R-US_R0603"))
    )
    (comp (ref "R68")
      (value "1K")
      (footprint "eagle-import:R0603")
      (libsource (lib "eagle-import") (part "R-US_R0603"))
    )
    (comp (ref "R69")
      (value "49.9")
      (footprint "eagle-import:R0603")
      (libsource (lib "eagle-import") (part "R-US_R0603"))
    )
    (comp (ref "R70")
      (value "1K")
      (footprint "eagle-import:R0603")
      (libsource (lib "eagle-import") (part "R-US_R0603"))
    )
    (comp (ref "R71")
      (value "1K")
      (footprint "eagle-import:R0603")
      (libsource (lib "eagle-import") (part "R-US_R0603"))
    )
    (comp (ref "R72")
      (value "49.9")
      (footprint "eagle-import:R0603")
      (libsource (lib "eagle-import") (part "R-US_R0603"))
    )
    (comp (ref "R73")
      (value "1K")
      (footprint "eagle-import:R0603")
      (libsource (lib "eagle-import") (part "R-US_R0603"))
    )
    (comp (ref "R74")
      (value "1K")
      (footprint "eagle-import:R0603")
      (libsource (lib "eagle-import") (part "R-US_R0603"))
    )
    (comp (ref "R75")
      (value "49.9")
      (footprint "eagle-import:R0603")
      (libsource (lib "eagle-import") (part "R-US_R0603"))
    )
    (comp (ref "R76")
      (value "1K")
      (footprint "eagle-import:R0603")
      (libsource (lib "eagle-import") (part "R-US_R0603"))
    )
    (comp (ref "R77")
      (value "1K")
      (footprint "eagle-import:R0603")
      (libsource (lib "eagle-import") (part "R-US_R0603"))
    )
    (comp (ref "R78")
      (value "49.9")
      (footprint "eagle-import:R0603")
      (libsource (lib "eagle-import") (part "R-US_R0603"))
    )
    (comp (ref "U24")
      (value "THS4521IDGKT")
      (footprint "eagle-import:DGK8")
      (fields
        (field (name "GENERIC_PART_NUMBER") "THS4521")
        (field (name "MANUFACTURER") "Texas Instruments")
      )
      (libsource (lib "eagle-import") (part "THS4521IDGKT"))
    )
    (comp (ref "U25")
      (value "THS4521IDGKT")
      (footprint "eagle-import:DGK8")
      (fields
        (field (name "GENERIC_PART_NUMBER") "THS4521")
        (field (name "MANUFACTURER") "Texas Instruments")
      )
      (libsource (lib "eagle-import") (part "THS4521IDGKT"))
    )
    (comp (ref "C105")
      (value "10uF")
      (footprint "eagle-import:C0603")
      (libsource (lib "eagle-import") (part "C-USC0603"))
    )
    (comp (ref "C106")
      (value "10uF")
      (footprint "eagle-import:C0603")
      (libsource (lib "eagle-import") (part "C-USC0603"))
    )
    (comp (ref "C107")
      (value "10uF")
      (footprint "eagle-import:C0603")
      (libsource (lib "eagle-import") (part "C-USC0603"))
    )
    (comp (ref "U9")
      (value "ADS1278IPAPR")
      (footprint "eagle-import:PAP64_7X7")
      (fields
        (field (name "GENERIC_PART_NUMBER") "ADS1278")
        (field (name "MANUFACTURER") "Texas Instruments")
      )
      (libsource (lib "eagle-import") (part "ADS1278IPAPR"))
    )
    (comp (ref "IC31")
      (value "TLV2771CDBVR")
      (footprint "eagle-import:SOT95P280X145-5N")
      (fields (field (name "MOUSER_PART_NUMBER") "595-TLV2771CDBVR"))
      (libsource (lib "eagle-import") (part "TLV2771CDBVR"))
    )
    (comp (ref "IC32")
      (value "TLV2771CDBVR")
      (footprint "eagle-import:SOT95P280X145-5N")
      (fields (field (name "MOUSER_PART_NUMBER") "595-TLV2771CDBVR"))
      (libsource (lib "eagle-import") (part "TLV2771CDBVR"))
    )
    (comp (ref "IC33")
      (value "TLV2771CDBVR")
      (footprint "eagle-import:SOT95P280X145-5N")
      (fields (field (name "MOUSER_PART_NUMBER") "595-TLV2771CDBVR"))
      (libsource (lib "eagle-import") (part "TLV2771CDBVR"))
    )
    (comp (ref "IC34")
      (value "TLV2771CDBVR")
      (footprint "eagle-import:SOT95P280X145-5N")
      (fields (field (name "MOUSER_PART_NUMBER") "595-TLV2771CDBVR"))
      (libsource (lib "eagle-import") (part "TLV2771CDBVR"))
    )
    (comp (ref "J4")
      (value "1989764")
      (footprint "eagle-import:CONN_1989764_PXC")
      (fields (field (name "COPYRIGHT") "Copyright (C) 2018 Accelerated Designs. All rights reserved"))
      (libsource (lib "eagle-import") (part "1989764"))
    )
    (comp (ref "R49")
      (value "50M")
      (footprint "eagle-import:R0805")
      (libsource (lib "eagle-import") (part "R-US_R0805"))
    )
    (comp (ref "R53")
      (value "1K")
      (footprint "eagle-import:R0805")
      (libsource (lib "eagle-import") (part "R-US_R0805"))
    )
    (comp (ref "R103")
      (value "50M")
      (footprint "eagle-import:R0805")
      (libsource (lib "eagle-import") (part "R-US_R0805"))
    )
    (comp (ref "R107")
      (value "1K")
      (footprint "eagle-import:R0805")
      (libsource (lib "eagle-import") (part "R-US_R0805"))
    )
    (comp (ref "R133")
      (value "50M")
      (footprint "eagle-import:R0805")
      (libsource (lib "eagle-import") (part "R-US_R0805"))
    )
    (comp (ref "R137")
      (value "50M")
      (footprint "eagle-import:R0805")
      (libsource (lib "eagle-import") (part "R-US_R0805"))
    )
    (comp (ref "R143")
      (value "100M")
      (footprint "eagle-import:R0805")
      (libsource (lib "eagle-import") (part "R-US_R0805"))
    )
    (comp (ref "R144")
      (value "100M")
      (footprint "eagle-import:R0805")
      (libsource (lib "eagle-import") (part "R-US_R0805"))
    )
    (comp (ref "R145")
      (value "100M")
      (footprint "eagle-import:R0805")
      (libsource (lib "eagle-import") (part "R-US_R0805"))
    )
    (comp (ref "R146")
      (value "100M")
      (footprint "eagle-import:R0805")
      (libsource (lib "eagle-import") (part "R-US_R0805"))
    )
    (comp (ref "R164")
      (value "1K")
      (footprint "eagle-import:R0805")
      (libsource (lib "eagle-import") (part "R-US_R0805"))
    )
    (comp (ref "R165")
      (value "1K")
      (footprint "eagle-import:R0805")
      (libsource (lib "eagle-import") (part "R-US_R0805"))
    )
    (comp (ref "IC10")
      (value "DE10-NANO")
      (footprint "eagle-import:DE10_NANO")
      (libsource (lib "eagle-import") (part "DE10-NANO"))
    )
    (comp (ref "IC11")
      (value "RASPBERRY_PI_4")
      (footprint "eagle-import:RASPBERRY_PI_4")
      (libsource (lib "eagle-import") (part "RASPBERRY_PI_4"))
    )
    (comp (ref "JP1")
      (value "PINHD-2X20")
      (footprint "eagle-import:2X20")
      (libsource (lib "eagle-import") (part "PINHD-2X20"))
    )
    (comp (ref "JP2")
      (value "PINHD-2X20")
      (footprint "eagle-import:2X20")
      (libsource (lib "eagle-import") (part "PINHD-2X20"))
    )
    (comp (ref "JP3")
      (value "PINHD-2X20")
      (footprint "eagle-import:2X20")
      (libsource (lib "eagle-import") (part "PINHD-2X20"))
    )
    (comp (ref "C99")
      (value "10uF")
      (footprint "eagle-import:C0603")
      (libsource (lib "eagle-import") (part "C-USC0603"))
    )
    (comp (ref "C100")
      (value "100uF")
      (footprint "eagle-import:C1206")
      (libsource (lib "eagle-import") (part "C-USC1206"))
    )
    (comp (ref "C101")
      (value "0.1uF")
      (footprint "eagle-import:C0603")
      (libsource (lib "eagle-import") (part "C-USC0603"))
    )
    (comp (ref "C102")
      (value "0.1uF")
      (footprint "eagle-import:C0603")
      (libsource (lib "eagle-import") (part "C-USC0603"))
    )
    (comp (ref "C103")
      (value "10uF")
      (footprint "eagle-import:C0603")
      (libsource (lib "eagle-import") (part "C-USC0603"))
    )
    (comp (ref "C104")
      (value "0.1uF")
      (footprint "eagle-import:C0603")
      (libsource (lib "eagle-import") (part "C-USC0603"))
    )
    (comp (ref "C116")
      (value "1uF")
      (footprint "eagle-import:C0603")
      (libsource (lib "eagle-import") (part "C-USC0603"))
    )
    (comp (ref "C117")
      (value "1uF")
      (footprint "eagle-import:C0603")
      (libsource (lib "eagle-import") (part "C-USC0603"))
    )
    (comp (ref "R134")
      (value "1K")
      (footprint "eagle-import:R0603")
      (libsource (lib "eagle-import") (part "R-US_R0603"))
    )
    (comp (ref "R135")
      (value "100")
      (footprint "eagle-import:R0603")
      (libsource (lib "eagle-import") (part "R-US_R0603"))
    )
    (comp (ref "R136")
      (value "1K")
      (footprint "eagle-import:R0603")
      (libsource (lib "eagle-import") (part "R-US_R0603"))
    )
    (comp (ref "R138")
      (value "100")
      (footprint "eagle-import:R0603")
      (libsource (lib "eagle-import") (part "R-US_R0603"))
    )
    (comp (ref "U7")
      (value "OPA350EA/2K5")
      (footprint "eagle-import:DGK8_TEX")
      (fields
        (field (name "MANUFACTURER") "Texas Instruments")
        (field (name "COPYRIGHT") "Copyright (C) 2018 Accelerated Designs. All rights reserved")
      )
      (libsource (lib "eagle-import") (part "OPA350EA/2K5"))
    )
    (comp (ref "U8")
      (value "OPA350EA/2K5")
      (footprint "eagle-import:DGK8_TEX")
      (fields
        (field (name "MANUFACTURER") "Texas Instruments")
        (field (name "COPYRIGHT") "Copyright (C) 2018 Accelerated Designs. All rights reserved")
      )
      (libsource (lib "eagle-import") (part "OPA350EA/2K5"))
    )
    (comp (ref "U12")
      (value "REF5025AID")
      (footprint "eagle-import:D8")
      (fields
        (field (name "GENERIC_PART_NUMBER") "REF5025")
        (field (name "MANUFACTURER") "Texas Instruments")
      )
      (libsource (lib "eagle-import") (part "REF5025AID"))
    )
    (comp (ref "C91")
      (value "2.7nF")
      (footprint "eagle-import:C0603")
      (libsource (lib "eagle-import") (part "C-USC0603"))
    )
    (comp (ref "C92")
      (value "2.2nF")
      (footprint "eagle-import:C0603")
      (libsource (lib "eagle-import") (part "C-USC0603"))
    )
    (comp (ref "C93")
      (value "0.1uF")
      (footprint "eagle-import:C0603")
      (libsource (lib "eagle-import") (part "C-USC0603"))
    )
    (comp (ref "C94")
      (value "2.7nF")
      (footprint "eagle-import:C0603")
      (libsource (lib "eagle-import") (part "C-USC0603"))
    )
    (comp (ref "C95")
      (value "2.7nF")
      (footprint "eagle-import:C0603")
      (libsource (lib "eagle-import") (part "C-USC0603"))
    )
    (comp (ref "C96")
      (value "2.2nF")
      (footprint "eagle-import:C0603")
      (libsource (lib "eagle-import") (part "C-USC0603"))
    )
    (comp (ref "C97")
      (value "0.1uF")
      (footprint "eagle-import:C0603")
      (libsource (lib "eagle-import") (part "C-USC0603"))
    )
    (comp (ref "C98")
      (value "2.7nF")
      (footprint "eagle-import:C0603")
      (libsource (lib "eagle-import") (part "C-USC0603"))
    )
    (comp (ref "R121")
      (value "1K")
      (footprint "eagle-import:R0603")
      (libsource (lib "eagle-import") (part "R-US_R0603"))
    )
    (comp (ref "R122")
      (value "1K")
      (footprint "eagle-import:R0603")
      (libsource (lib "eagle-import") (part "R-US_R0603"))
    )
    (comp (ref "R123")
      (value "49.9")
      (footprint "eagle-import:R0603")
      (libsource (lib "eagle-import") (part "R-US_R0603"))
    )
    (comp (ref "R124")
      (value "1K")
      (footprint "eagle-import:R0603")
      (libsource (lib "eagle-import") (part "R-US_R0603"))
    )
    (comp (ref "R125")
      (value "1K")
      (footprint "eagle-import:R0603")
      (libsource (lib "eagle-import") (part "R-US_R0603"))
    )
    (comp (ref "R126")
      (value "49.9")
      (footprint "eagle-import:R0603")
      (libsource (lib "eagle-import") (part "R-US_R0603"))
    )
    (comp (ref "R127")
      (value "1K")
      (footprint "eagle-import:R0603")
      (libsource (lib "eagle-import") (part "R-US_R0603"))
    )
    (comp (ref "R128")
      (value "1K")
      (footprint "eagle-import:R0603")
      (libsource (lib "eagle-import") (part "R-US_R0603"))
    )
    (comp (ref "R129")
      (value "49.9")
      (footprint "eagle-import:R0603")
      (libsource (lib "eagle-import") (part "R-US_R0603"))
    )
    (comp (ref "R130")
      (value "1K")
      (footprint "eagle-import:R0603")
      (libsource (lib "eagle-import") (part "R-US_R0603"))
    )
    (comp (ref "R131")
      (value "1K")
      (footprint "eagle-import:R0603")
      (libsource (lib "eagle-import") (part "R-US_R0603"))
    )
    (comp (ref "R132")
      (value "49.9")
      (footprint "eagle-import:R0603")
      (libsource (lib "eagle-import") (part "R-US_R0603"))
    )
    (comp (ref "U32")
      (value "THS4521IDGKT")
      (footprint "eagle-import:DGK8")
      (fields
        (field (name "GENERIC_PART_NUMBER") "THS4521")
        (field (name "MANUFACTURER") "Texas Instruments")
      )
      (libsource (lib "eagle-import") (part "THS4521IDGKT"))
    )
    (comp (ref "U33")
      (value "THS4521IDGKT")
      (footprint "eagle-import:DGK8")
      (fields
        (field (name "GENERIC_PART_NUMBER") "THS4521")
        (field (name "MANUFACTURER") "Texas Instruments")
      )
      (libsource (lib "eagle-import") (part "THS4521IDGKT"))
    )
    (comp (ref "C25")
      (value "2.7nF")
      (footprint "eagle-import:C0603")
      (libsource (lib "eagle-import") (part "C-USC0603"))
    )
    (comp (ref "C26")
      (value "2.2nF")
      (footprint "eagle-import:C0603")
      (libsource (lib "eagle-import") (part "C-USC0603"))
    )
    (comp (ref "C27")
      (value "0.1uF")
      (footprint "eagle-import:C0603")
      (libsource (lib "eagle-import") (part "C-USC0603"))
    )
    (comp (ref "C28")
      (value "2.7nF")
      (footprint "eagle-import:C0603")
      (libsource (lib "eagle-import") (part "C-USC0603"))
    )
    (comp (ref "C29")
      (value "2.7nF")
      (footprint "eagle-import:C0603")
      (libsource (lib "eagle-import") (part "C-USC0603"))
    )
    (comp (ref "C30")
      (value "2.2nF")
      (footprint "eagle-import:C0603")
      (libsource (lib "eagle-import") (part "C-USC0603"))
    )
    (comp (ref "C31")
      (value "0.1uF")
      (footprint "eagle-import:C0603")
      (libsource (lib "eagle-import") (part "C-USC0603"))
    )
    (comp (ref "C32")
      (value "2.7nF")
      (footprint "eagle-import:C0603")
      (libsource (lib "eagle-import") (part "C-USC0603"))
    )
    (comp (ref "R37")
      (value "1K")
      (footprint "eagle-import:R0603")
      (libsource (lib "eagle-import") (part "R-US_R0603"))
    )
    (comp (ref "R38")
      (value "1K")
      (footprint "eagle-import:R0603")
      (libsource (lib "eagle-import") (part "R-US_R0603"))
    )
    (comp (ref "R39")
      (value "49.9")
      (footprint "eagle-import:R0603")
      (libsource (lib "eagle-import") (part "R-US_R0603"))
    )
    (comp (ref "R40")
      (value "1K")
      (footprint "eagle-import:R0603")
      (libsource (lib "eagle-import") (part "R-US_R0603"))
    )
    (comp (ref "R41")
      (value "1K")
      (footprint "eagle-import:R0603")
      (libsource (lib "eagle-import") (part "R-US_R0603"))
    )
    (comp (ref "R42")
      (value "49.9")
      (footprint "eagle-import:R0603")
      (libsource (lib "eagle-import") (part "R-US_R0603"))
    )
    (comp (ref "R43")
      (value "1K")
      (footprint "eagle-import:R0603")
      (libsource (lib "eagle-import") (part "R-US_R0603"))
    )
    (comp (ref "R44")
      (value "1K")
      (footprint "eagle-import:R0603")
      (libsource (lib "eagle-import") (part "R-US_R0603"))
    )
    (comp (ref "R45")
      (value "49.9")
      (footprint "eagle-import:R0603")
      (libsource (lib "eagle-import") (part "R-US_R0603"))
    )
    (comp (ref "R46")
      (value "1K")
      (footprint "eagle-import:R0603")
      (libsource (lib "eagle-import") (part "R-US_R0603"))
    )
    (comp (ref "R47")
      (value "1K")
      (footprint "eagle-import:R0603")
      (libsource (lib "eagle-import") (part "R-US_R0603"))
    )
    (comp (ref "R48")
      (value "49.9")
      (footprint "eagle-import:R0603")
      (libsource (lib "eagle-import") (part "R-US_R0603"))
    )
    (comp (ref "U20")
      (value "THS4521IDGKT")
      (footprint "eagle-import:DGK8")
      (fields
        (field (name "GENERIC_PART_NUMBER") "THS4521")
        (field (name "MANUFACTURER") "Texas Instruments")
      )
      (libsource (lib "eagle-import") (part "THS4521IDGKT"))
    )
    (comp (ref "U21")
      (value "THS4521IDGKT")
      (footprint "eagle-import:DGK8")
      (fields
        (field (name "GENERIC_PART_NUMBER") "THS4521")
        (field (name "MANUFACTURER") "Texas Instruments")
      )
      (libsource (lib "eagle-import") (part "THS4521IDGKT"))
    )
    (comp (ref "C66")
      (value "2.7nF")
      (footprint "eagle-import:C0603")
      (libsource (lib "eagle-import") (part "C-USC0603"))
    )
    (comp (ref "C67")
      (value "2.2nF")
      (footprint "eagle-import:C0603")
      (libsource (lib "eagle-import") (part "C-USC0603"))
    )
    (comp (ref "C68")
      (value "0.1uF")
      (footprint "eagle-import:C0603")
      (libsource (lib "eagle-import") (part "C-USC0603"))
    )
    (comp (ref "C69")
      (value "2.7nF")
      (footprint "eagle-import:C0603")
      (libsource (lib "eagle-import") (part "C-USC0603"))
    )
    (comp (ref "C70")
      (value "2.7nF")
      (footprint "eagle-import:C0603")
      (libsource (lib "eagle-import") (part "C-USC0603"))
    )
    (comp (ref "C71")
      (value "2.2nF")
      (footprint "eagle-import:C0603")
      (libsource (lib "eagle-import") (part "C-USC0603"))
    )
    (comp (ref "C72")
      (value "0.1uF")
      (footprint "eagle-import:C0603")
      (libsource (lib "eagle-import") (part "C-USC0603"))
    )
    (comp (ref "C73")
      (value "2.7nF")
      (footprint "eagle-import:C0603")
      (libsource (lib "eagle-import") (part "C-USC0603"))
    )
    (comp (ref "R91")
      (value "1K")
      (footprint "eagle-import:R0603")
      (libsource (lib "eagle-import") (part "R-US_R0603"))
    )
    (comp (ref "R92")
      (value "1K")
      (footprint "eagle-import:R0603")
      (libsource (lib "eagle-import") (part "R-US_R0603"))
    )
    (comp (ref "R93")
      (value "49.9")
      (footprint "eagle-import:R0603")
      (libsource (lib "eagle-import") (part "R-US_R0603"))
    )
    (comp (ref "R94")
      (value "1K")
      (footprint "eagle-import:R0603")
      (libsource (lib "eagle-import") (part "R-US_R0603"))
    )
    (comp (ref "R95")
      (value "1K")
      (footprint "eagle-import:R0603")
      (libsource (lib "eagle-import") (part "R-US_R0603"))
    )
    (comp (ref "R96")
      (value "49.9")
      (footprint "eagle-import:R0603")
      (libsource (lib "eagle-import") (part "R-US_R0603"))
    )
    (comp (ref "R97")
      (value "1K")
      (footprint "eagle-import:R0603")
      (libsource (lib "eagle-import") (part "R-US_R0603"))
    )
    (comp (ref "R98")
      (value "1K")
      (footprint "eagle-import:R0603")
      (libsource (lib "eagle-import") (part "R-US_R0603"))
    )
    (comp (ref "R99")
      (value "49.9")
      (footprint "eagle-import:R0603")
      (libsource (lib "eagle-import") (part "R-US_R0603"))
    )
    (comp (ref "R100")
      (value "1K")
      (footprint "eagle-import:R0603")
      (libsource (lib "eagle-import") (part "R-US_R0603"))
    )
    (comp (ref "R101")
      (value "1K")
      (footprint "eagle-import:R0603")
      (libsource (lib "eagle-import") (part "R-US_R0603"))
    )
    (comp (ref "R102")
      (value "49.9")
      (footprint "eagle-import:R0603")
      (libsource (lib "eagle-import") (part "R-US_R0603"))
    )
    (comp (ref "U28")
      (value "THS4521IDGKT")
      (footprint "eagle-import:DGK8")
      (fields
        (field (name "GENERIC_PART_NUMBER") "THS4521")
        (field (name "MANUFACTURER") "Texas Instruments")
      )
      (libsource (lib "eagle-import") (part "THS4521IDGKT"))
    )
    (comp (ref "U29")
      (value "THS4521IDGKT")
      (footprint "eagle-import:DGK8")
      (fields
        (field (name "GENERIC_PART_NUMBER") "THS4521")
        (field (name "MANUFACTURER") "Texas Instruments")
      )
      (libsource (lib "eagle-import") (part "THS4521IDGKT"))
    )
    (comp (ref "C39")
      (value "10uF")
      (footprint "eagle-import:C0603")
      (libsource (lib "eagle-import") (part "C-USC0603"))
    )
    (comp (ref "C40")
      (value "10uF")
      (footprint "eagle-import:C0603")
      (libsource (lib "eagle-import") (part "C-USC0603"))
    )
    (comp (ref "C41")
      (value "10uF")
      (footprint "eagle-import:C0603")
      (libsource (lib "eagle-import") (part "C-USC0603"))
    )
    (comp (ref "U11")
      (value "ADS1278IPAPR")
      (footprint "eagle-import:PAP64_7X7")
      (fields
        (field (name "GENERIC_PART_NUMBER") "ADS1278")
        (field (name "MANUFACTURER") "Texas Instruments")
      )
      (libsource (lib "eagle-import") (part "ADS1278IPAPR"))
    )
    (comp (ref "C80")
      (value "10uF")
      (footprint "eagle-import:C0603")
      (libsource (lib "eagle-import") (part "C-USC0603"))
    )
    (comp (ref "C81")
      (value "10uF")
      (footprint "eagle-import:C0603")
      (libsource (lib "eagle-import") (part "C-USC0603"))
    )
    (comp (ref "C82")
      (value "10uF")
      (footprint "eagle-import:C0603")
      (libsource (lib "eagle-import") (part "C-USC0603"))
    )
    (comp (ref "U6")
      (value "ADS1278IPAPR")
      (footprint "eagle-import:PAP64_7X7")
      (fields
        (field (name "GENERIC_PART_NUMBER") "ADS1278")
        (field (name "MANUFACTURER") "Texas Instruments")
      )
      (libsource (lib "eagle-import") (part "ADS1278IPAPR"))
    )
    (comp (ref "C58")
      (value "2.7nF")
      (footprint "eagle-import:C0603")
      (libsource (lib "eagle-import") (part "C-USC0603"))
    )
    (comp (ref "C59")
      (value "2.2nF")
      (footprint "eagle-import:C0603")
      (libsource (lib "eagle-import") (part "C-USC0603"))
    )
    (comp (ref "C60")
      (value "0.1uF")
      (footprint "eagle-import:C0603")
      (libsource (lib "eagle-import") (part "C-USC0603"))
    )
    (comp (ref "C61")
      (value "2.7nF")
      (footprint "eagle-import:C0603")
      (libsource (lib "eagle-import") (part "C-USC0603"))
    )
    (comp (ref "C62")
      (value "2.7nF")
      (footprint "eagle-import:C0603")
      (libsource (lib "eagle-import") (part "C-USC0603"))
    )
    (comp (ref "C63")
      (value "2.2nF")
      (footprint "eagle-import:C0603")
      (libsource (lib "eagle-import") (part "C-USC0603"))
    )
    (comp (ref "C64")
      (value "0.1uF")
      (footprint "eagle-import:C0603")
      (libsource (lib "eagle-import") (part "C-USC0603"))
    )
    (comp (ref "C65")
      (value "2.7nF")
      (footprint "eagle-import:C0603")
      (libsource (lib "eagle-import") (part "C-USC0603"))
    )
    (comp (ref "R79")
      (value "1K")
      (footprint "eagle-import:R0603")
      (libsource (lib "eagle-import") (part "R-US_R0603"))
    )
    (comp (ref "R80")
      (value "1K")
      (footprint "eagle-import:R0603")
      (libsource (lib "eagle-import") (part "R-US_R0603"))
    )
    (comp (ref "R81")
      (value "49.9")
      (footprint "eagle-import:R0603")
      (libsource (lib "eagle-import") (part "R-US_R0603"))
    )
    (comp (ref "R82")
      (value "1K")
      (footprint "eagle-import:R0603")
      (libsource (lib "eagle-import") (part "R-US_R0603"))
    )
    (comp (ref "R83")
      (value "1K")
      (footprint "eagle-import:R0603")
      (libsource (lib "eagle-import") (part "R-US_R0603"))
    )
    (comp (ref "R84")
      (value "49.9")
      (footprint "eagle-import:R0603")
      (libsource (lib "eagle-import") (part "R-US_R0603"))
    )
    (comp (ref "R85")
      (value "1K")
      (footprint "eagle-import:R0603")
      (libsource (lib "eagle-import") (part "R-US_R0603"))
    )
    (comp (ref "R86")
      (value "1K")
      (footprint "eagle-import:R0603")
      (libsource (lib "eagle-import") (part "R-US_R0603"))
    )
    (comp (ref "R87")
      (value "49.9")
      (footprint "eagle-import:R0603")
      (libsource (lib "eagle-import") (part "R-US_R0603"))
    )
    (comp (ref "R88")
      (value "1K")
      (footprint "eagle-import:R0603")
      (libsource (lib "eagle-import") (part "R-US_R0603"))
    )
    (comp (ref "R89")
      (value "1K")
      (footprint "eagle-import:R0603")
      (libsource (lib "eagle-import") (part "R-US_R0603"))
    )
    (comp (ref "R90")
      (value "49.9")
      (footprint "eagle-import:R0603")
      (libsource (lib "eagle-import") (part "R-US_R0603"))
    )
    (comp (ref "U26")
      (value "THS4521IDGKT")
      (footprint "eagle-import:DGK8")
      (fields
        (field (name "GENERIC_PART_NUMBER") "THS4521")
        (field (name "MANUFACTURER") "Texas Instruments")
      )
      (libsource (lib "eagle-import") (part "THS4521IDGKT"))
    )
    (comp (ref "U27")
      (value "THS4521IDGKT")
      (footprint "eagle-import:DGK8")
      (fields
        (field (name "GENERIC_PART_NUMBER") "THS4521")
        (field (name "MANUFACTURER") "Texas Instruments")
      )
      (libsource (lib "eagle-import") (part "THS4521IDGKT"))
    )
    (comp (ref "C83")
      (value "2.7nF")
      (footprint "eagle-import:C0603")
      (libsource (lib "eagle-import") (part "C-USC0603"))
    )
    (comp (ref "C84")
      (value "2.2nF")
      (footprint "eagle-import:C0603")
      (libsource (lib "eagle-import") (part "C-USC0603"))
    )
    (comp (ref "C85")
      (value "0.1uF")
      (footprint "eagle-import:C0603")
      (libsource (lib "eagle-import") (part "C-USC0603"))
    )
    (comp (ref "C86")
      (value "2.7nF")
      (footprint "eagle-import:C0603")
      (libsource (lib "eagle-import") (part "C-USC0603"))
    )
    (comp (ref "C87")
      (value "2.7nF")
      (footprint "eagle-import:C0603")
      (libsource (lib "eagle-import") (part "C-USC0603"))
    )
    (comp (ref "C88")
      (value "2.2nF")
      (footprint "eagle-import:C0603")
      (libsource (lib "eagle-import") (part "C-USC0603"))
    )
    (comp (ref "C89")
      (value "0.1uF")
      (footprint "eagle-import:C0603")
      (libsource (lib "eagle-import") (part "C-USC0603"))
    )
    (comp (ref "C90")
      (value "2.7nF")
      (footprint "eagle-import:C0603")
      (libsource (lib "eagle-import") (part "C-USC0603"))
    )
    (comp (ref "R109")
      (value "1K")
      (footprint "eagle-import:R0603")
      (libsource (lib "eagle-import") (part "R-US_R0603"))
    )
    (comp (ref "R110")
      (value "1K")
      (footprint "eagle-import:R0603")
      (libsource (lib "eagle-import") (part "R-US_R0603"))
    )
    (comp (ref "R111")
      (value "49.9")
      (footprint "eagle-import:R0603")
      (libsource (lib "eagle-import") (part "R-US_R0603"))
    )
    (comp (ref "R112")
      (value "1K")
      (footprint "eagle-import:R0603")
      (libsource (lib "eagle-import") (part "R-US_R0603"))
    )
    (comp (ref "R113")
      (value "1K")
      (footprint "eagle-import:R0603")
      (libsource (lib "eagle-import") (part "R-US_R0603"))
    )
    (comp (ref "R114")
      (value "49.9")
      (footprint "eagle-import:R0603")
      (libsource (lib "eagle-import") (part "R-US_R0603"))
    )
    (comp (ref "R115")
      (value "1K")
      (footprint "eagle-import:R0603")
      (libsource (lib "eagle-import") (part "R-US_R0603"))
    )
    (comp (ref "R116")
      (value "1K")
      (footprint "eagle-import:R0603")
      (libsource (lib "eagle-import") (part "R-US_R0603"))
    )
    (comp (ref "R117")
      (value "49.9")
      (footprint "eagle-import:R0603")
      (libsource (lib "eagle-import") (part "R-US_R0603"))
    )
    (comp (ref "R118")
      (value "1K")
      (footprint "eagle-import:R0603")
      (libsource (lib "eagle-import") (part "R-US_R0603"))
    )
    (comp (ref "R119")
      (value "1K")
      (footprint "eagle-import:R0603")
      (libsource (lib "eagle-import") (part "R-US_R0603"))
    )
    (comp (ref "R120")
      (value "49.9")
      (footprint "eagle-import:R0603")
      (libsource (lib "eagle-import") (part "R-US_R0603"))
    )
    (comp (ref "U30")
      (value "THS4521IDGKT")
      (footprint "eagle-import:DGK8")
      (fields
        (field (name "GENERIC_PART_NUMBER") "THS4521")
        (field (name "MANUFACTURER") "Texas Instruments")
      )
      (libsource (lib "eagle-import") (part "THS4521IDGKT"))
    )
    (comp (ref "U31")
      (value "THS4521IDGKT")
      (footprint "eagle-import:DGK8")
      (fields
        (field (name "GENERIC_PART_NUMBER") "THS4521")
        (field (name "MANUFACTURER") "Texas Instruments")
      )
      (libsource (lib "eagle-import") (part "THS4521IDGKT"))
    )
    (comp (ref "C1")
      (value "2.7nF")
      (footprint "eagle-import:C0603")
      (libsource (lib "eagle-import") (part "C-USC0603"))
    )
    (comp (ref "C2")
      (value "2.2nF")
      (footprint "eagle-import:C0603")
      (libsource (lib "eagle-import") (part "C-USC0603"))
    )
    (comp (ref "C3")
      (value "0.1uF")
      (footprint "eagle-import:C0603")
      (libsource (lib "eagle-import") (part "C-USC0603"))
    )
    (comp (ref "C4")
      (value "2.7nF")
      (footprint "eagle-import:C0603")
      (libsource (lib "eagle-import") (part "C-USC0603"))
    )
    (comp (ref "C5")
      (value "2.7nF")
      (footprint "eagle-import:C0603")
      (libsource (lib "eagle-import") (part "C-USC0603"))
    )
    (comp (ref "C6")
      (value "2.2nF")
      (footprint "eagle-import:C0603")
      (libsource (lib "eagle-import") (part "C-USC0603"))
    )
    (comp (ref "C7")
      (value "0.1uF")
      (footprint "eagle-import:C0603")
      (libsource (lib "eagle-import") (part "C-USC0603"))
    )
    (comp (ref "C8")
      (value "2.7nF")
      (footprint "eagle-import:C0603")
      (libsource (lib "eagle-import") (part "C-USC0603"))
    )
    (comp (ref "R1")
      (value "1K")
      (footprint "eagle-import:R0603")
      (libsource (lib "eagle-import") (part "R-US_R0603"))
    )
    (comp (ref "R2")
      (value "1K")
      (footprint "eagle-import:R0603")
      (libsource (lib "eagle-import") (part "R-US_R0603"))
    )
    (comp (ref "R3")
      (value "49.9")
      (footprint "eagle-import:R0603")
      (libsource (lib "eagle-import") (part "R-US_R0603"))
    )
    (comp (ref "R4")
      (value "1K")
      (footprint "eagle-import:R0603")
      (libsource (lib "eagle-import") (part "R-US_R0603"))
    )
    (comp (ref "R5")
      (value "1K")
      (footprint "eagle-import:R0603")
      (libsource (lib "eagle-import") (part "R-US_R0603"))
    )
    (comp (ref "R6")
      (value "49.9")
      (footprint "eagle-import:R0603")
      (libsource (lib "eagle-import") (part "R-US_R0603"))
    )
    (comp (ref "R7")
      (value "1K")
      (footprint "eagle-import:R0603")
      (libsource (lib "eagle-import") (part "R-US_R0603"))
    )
    (comp (ref "R8")
      (value "1K")
      (footprint "eagle-import:R0603")
      (libsource (lib "eagle-import") (part "R-US_R0603"))
    )
    (comp (ref "R9")
      (value "49.9")
      (footprint "eagle-import:R0603")
      (libsource (lib "eagle-import") (part "R-US_R0603"))
    )
    (comp (ref "R10")
      (value "1K")
      (footprint "eagle-import:R0603")
      (libsource (lib "eagle-import") (part "R-US_R0603"))
    )
    (comp (ref "R11")
      (value "1K")
      (footprint "eagle-import:R0603")
      (libsource (lib "eagle-import") (part "R-US_R0603"))
    )
    (comp (ref "R12")
      (value "49.9")
      (footprint "eagle-import:R0603")
      (libsource (lib "eagle-import") (part "R-US_R0603"))
    )
    (comp (ref "U14")
      (value "THS4521IDGKT")
      (footprint "eagle-import:DGK8")
      (fields
        (field (name "GENERIC_PART_NUMBER") "THS4521")
        (field (name "MANUFACTURER") "Texas Instruments")
      )
      (libsource (lib "eagle-import") (part "THS4521IDGKT"))
    )
    (comp (ref "U15")
      (value "THS4521IDGKT")
      (footprint "eagle-import:DGK8")
      (fields
        (field (name "GENERIC_PART_NUMBER") "THS4521")
        (field (name "MANUFACTURER") "Texas Instruments")
      )
      (libsource (lib "eagle-import") (part "THS4521IDGKT"))
    )
  )
  (nets
    (net (code "1") (name "+1V8") (class "Default")
      (node (ref "C107") (pin "1") (pinfunction "1_1") (pintype "passive"))
      (node (ref "C41") (pin "1") (pinfunction "1_1") (pintype "passive"))
      (node (ref "C82") (pin "1") (pinfunction "1_1") (pintype "passive"))
      (node (ref "IC28") (pin "4") (pinfunction "VOUT_4") (pintype "bidirectional"))
      (node (ref "U11") (pin "26") (pinfunction "DVDD_26") (pintype "power_in"))
      (node (ref "U6") (pin "26") (pinfunction "DVDD_26") (pintype "power_in"))
      (node (ref "U9") (pin "26") (pinfunction "DVDD_26") (pintype "power_in"))
    )
    (net (code "2") (name "+3V3") (class "Default")
      (node (ref "C106") (pin "1") (pinfunction "1_1") (pintype "passive"))
      (node (ref "C40") (pin "1") (pinfunction "1_1") (pintype "passive"))
      (node (ref "C81") (pin "1") (pinfunction "1_1") (pintype "passive"))
      (node (ref "IC29") (pin "5") (pinfunction "VOUT_5") (pintype "bidirectional"))
      (node (ref "IC31") (pin "5") (pinfunction "VDD_5") (pintype "bidirectional"))
      (node (ref "IC32") (pin "5") (pinfunction "VDD_5") (pintype "bidirectional"))
      (node (ref "IC33") (pin "5") (pinfunction "VDD_5") (pintype "bidirectional"))
      (node (ref "IC34") (pin "5") (pinfunction "VDD_5") (pintype "bidirectional"))
      (node (ref "R148") (pin "2") (pinfunction "2_2") (pintype "passive"))
      (node (ref "R150") (pin "2") (pinfunction "2_2") (pintype "passive"))
      (node (ref "R152") (pin "2") (pinfunction "2_2") (pintype "passive"))
      (node (ref "R154") (pin "2") (pinfunction "2_2") (pintype "passive"))
      (node (ref "R156") (pin "2") (pinfunction "2_2") (pintype "passive"))
      (node (ref "R158") (pin "2") (pinfunction "2_2") (pintype "passive"))
      (node (ref "R160") (pin "2") (pinfunction "2_2") (pintype "passive"))
      (node (ref "R162") (pin "2") (pinfunction "2_2") (pintype "passive"))
      (node (ref "U11") (pin "10") (pinfunction "CLKDIV_2_10") (pintype "input"))
      (node (ref "U11") (pin "22") (pinfunction "IOVDD_2_22") (pintype "power_in"))
      (node (ref "U11") (pin "23") (pinfunction "IOVDD_23") (pintype "power_in"))
      (node (ref "U11") (pin "31") (pinfunction "FORMAT1_31") (pintype "input"))
      (node (ref "U11") (pin "35") (pinfunction "~{PWDN8}_35") (pintype "input"))
      (node (ref "U11") (pin "36") (pinfunction "~{PWDN7}_36") (pintype "input"))
      (node (ref "U11") (pin "37") (pinfunction "~{PWDN6}_37") (pintype "input"))
      (node (ref "U11") (pin "38") (pinfunction "~{PWDN5}_38") (pintype "input"))
      (node (ref "U11") (pin "39") (pinfunction "~{PWDN4}_39") (pintype "input"))
      (node (ref "U11") (pin "40") (pinfunction "~{PWDN3}_40") (pintype "input"))
      (node (ref "U11") (pin "41") (pinfunction "~{PWDN2}_41") (pintype "input"))
      (node (ref "U11") (pin "42") (pinfunction "~{PWDN1}_42") (pintype "input"))
      (node (ref "U6") (pin "10") (pinfunction "CLKDIV_2_10") (pintype "input"))
      (node (ref "U6") (pin "22") (pinfunction "IOVDD_2_22") (pintype "power_in"))
      (node (ref "U6") (pin "23") (pinfunction "IOVDD_23") (pintype "power_in"))
      (node (ref "U6") (pin "31") (pinfunction "FORMAT1_31") (pintype "input"))
      (node (ref "U6") (pin "35") (pinfunction "~{PWDN8}_35") (pintype "input"))
      (node (ref "U6") (pin "36") (pinfunction "~{PWDN7}_36") (pintype "input"))
      (node (ref "U6") (pin "37") (pinfunction "~{PWDN6}_37") (pintype "input"))
      (node (ref "U6") (pin "38") (pinfunction "~{PWDN5}_38") (pintype "input"))
      (node (ref "U6") (pin "39") (pinfunction "~{PWDN4}_39") (pintype "input"))
      (node (ref "U6") (pin "40") (pinfunction "~{PWDN3}_40") (pintype "input"))
      (node (ref "U6") (pin "41") (pinfunction "~{PWDN2}_41") (pintype "input"))
      (node (ref "U6") (pin "42") (pinfunction "~{PWDN1}_42") (pintype "input"))
      (node (ref "U9") (pin "10") (pinfunction "CLKDIV_2_10") (pintype "input"))
      (node (ref "U9") (pin "22") (pinfunction "IOVDD_2_22") (pintype "power_in"))
      (node (ref "U9") (pin "23") (pinfunction "IOVDD_23") (pintype "power_in"))
      (node (ref "U9") (pin "31") (pinfunction "FORMAT1_31") (pintype "input"))
      (node (ref "U9") (pin "35") (pinfunction "~{PWDN8}_35") (pintype "input"))
      (node (ref "U9") (pin "36") (pinfunction "~{PWDN7}_36") (pintype "input"))
      (node (ref "U9") (pin "37") (pinfunction "~{PWDN6}_37") (pintype "input"))
      (node (ref "U9") (pin "38") (pinfunction "~{PWDN5}_38") (pintype "input"))
      (node (ref "U9") (pin "39") (pinfunction "~{PWDN4}_39") (pintype "input"))
      (node (ref "U9") (pin "40") (pinfunction "~{PWDN3}_40") (pintype "input"))
      (node (ref "U9") (pin "41") (pinfunction "~{PWDN2}_41") (pintype "input"))
      (node (ref "U9") (pin "42") (pinfunction "~{PWDN1}_42") (pintype "input"))
    )
    (net (code "3") (name "+5V") (class "Default")
      (node (ref "C105") (pin "1") (pinfunction "1_1") (pintype "passive"))
      (node (ref "C114") (pin "1") (pinfunction "1_1") (pintype "passive"))
      (node (ref "C117") (pin "1") (pinfunction "1_1") (pintype "passive"))
      (node (ref "C119") (pin "1") (pinfunction "1_1") (pintype "passive"))
      (node (ref "C39") (pin "1") (pinfunction "1_1") (pintype "passive"))
      (node (ref "C80") (pin "1") (pinfunction "1_1") (pintype "passive"))
      (node (ref "IC43") (pin "VOUT") (pinfunction "VOUT_VOUT") (pintype "bidirectional"))
      (node (ref "JP4") (pin "39") (pinfunction "39_39") (pintype "passive"))
      (node (ref "JP4") (pin "40") (pinfunction "40_40") (pintype "passive"))
      (node (ref "R147") (pin "1") (pinfunction "1_1") (pintype "passive"))
      (node (ref "R149") (pin "1") (pinfunction "1_1") (pintype "passive"))
      (node (ref "R151") (pin "1") (pinfunction "1_1") (pintype "passive"))
      (node (ref "R153") (pin "1") (pinfunction "1_1") (pintype "passive"))
      (node (ref "R155") (pin "1") (pinfunction "1_1") (pintype "passive"))
      (node (ref "R157") (pin "1") (pinfunction "1_1") (pintype "passive"))
      (node (ref "R159") (pin "1") (pinfunction "1_1") (pintype "passive"))
      (node (ref "R161") (pin "1") (pinfunction "1_1") (pintype "passive"))
      (node (ref "U1") (pin "7") (pinfunction "V+_7") (pintype "power_in"))
      (node (ref "U11") (pin "44") (pinfunction "AVDD_3_44") (pintype "power_in"))
      (node (ref "U11") (pin "5") (pinfunction "AVDD_2_5") (pintype "power_in"))
      (node (ref "U11") (pin "53") (pinfunction "AVDD_4_53") (pintype "power_in"))
      (node (ref "U11") (pin "60") (pinfunction "AVDD_60") (pintype "power_in"))
      (node (ref "U12") (pin "2") (pinfunction "VIN_2") (pintype "input"))
      (node (ref "U13") (pin "2") (pinfunction "VIN_2") (pintype "input"))
      (node (ref "U14") (pin "3") (pinfunction "VS+_3") (pintype "power_in"))
      (node (ref "U15") (pin "3") (pinfunction "VS+_3") (pintype "power_in"))
      (node (ref "U16") (pin "3") (pinfunction "VS+_3") (pintype "power_in"))
      (node (ref "U17") (pin "3") (pinfunction "VS+_3") (pintype "power_in"))
      (node (ref "U18") (pin "3") (pinfunction "VS+_3") (pintype "power_in"))
      (node (ref "U19") (pin "3") (pinfunction "VS+_3") (pintype "power_in"))
      (node (ref "U2") (pin "7") (pinfunction "V+_7") (pintype "power_in"))
      (node (ref "U20") (pin "3") (pinfunction "VS+_3") (pintype "power_in"))
      (node (ref "U21") (pin "3") (pinfunction "VS+_3") (pintype "power_in"))
      (node (ref "U22") (pin "3") (pinfunction "VS+_3") (pintype "power_in"))
      (node (ref "U23") (pin "3") (pinfunction "VS+_3") (pintype "power_in"))
      (node (ref "U24") (pin "3") (pinfunction "VS+_3") (pintype "power_in"))
      (node (ref "U25") (pin "3") (pinfunction "VS+_3") (pintype "power_in"))
      (node (ref "U26") (pin "3") (pinfunction "VS+_3") (pintype "power_in"))
      (node (ref "U27") (pin "3") (pinfunction "VS+_3") (pintype "power_in"))
      (node (ref "U28") (pin "3") (pinfunction "VS+_3") (pintype "power_in"))
      (node (ref "U29") (pin "3") (pinfunction "VS+_3") (pintype "power_in"))
      (node (ref "U3") (pin "2") (pinfunction "VIN_2") (pintype "input"))
      (node (ref "U30") (pin "3") (pinfunction "VS+_3") (pintype "power_in"))
      (node (ref "U31") (pin "3") (pinfunction "VS+_3") (pintype "power_in"))
      (node (ref "U32") (pin "3") (pinfunction "VS+_3") (pintype "power_in"))
      (node (ref "U33") (pin "3") (pinfunction "VS+_3") (pintype "power_in"))
      (node (ref "U4") (pin "7") (pinfunction "V+_7") (pintype "power_in"))
      (node (ref "U5") (pin "7") (pinfunction "V+_7") (pintype "power_in"))
      (node (ref "U6") (pin "44") (pinfunction "AVDD_3_44") (pintype "power_in"))
      (node (ref "U6") (pin "5") (pinfunction "AVDD_2_5") (pintype "power_in"))
      (node (ref "U6") (pin "53") (pinfunction "AVDD_4_53") (pintype "power_in"))
      (node (ref "U6") (pin "60") (pinfunction "AVDD_60") (pintype "power_in"))
      (node (ref "U7") (pin "7") (pinfunction "V+_7") (pintype "power_in"))
      (node (ref "U8") (pin "7") (pinfunction "V+_7") (pintype "power_in"))
      (node (ref "U9") (pin "44") (pinfunction "AVDD_3_44") (pintype "power_in"))
      (node (ref "U9") (pin "5") (pinfunction "AVDD_2_5") (pintype "power_in"))
      (node (ref "U9") (pin "53") (pinfunction "AVDD_4_53") (pintype "power_in"))
      (node (ref "U9") (pin "60") (pinfunction "AVDD_60") (pintype "power_in"))
    )
    (net (code "4") (name "+12V") (class "Default")
      (node (ref "J6") (pin "1") (pinfunction "1_1") (pintype "bidirectional"))
      (node (ref "JP4") (pin "35") (pinfunction "35_35") (pintype "passive"))
      (node (ref "JP4") (pin "36") (pinfunction "36_36") (pintype "passive"))
      (node (ref "U$4") (pin "5") (pinfunction "VOUT_5") (pintype "bidirectional"))
    )
    (net (code "5") (name "+24V") (class "Default")
      (node (ref "IC27") (pin "3") (pinfunction "VIN_3") (pintype "bidirectional"))
      (node (ref "IC28") (pin "2") (pinfunction "VIN_2") (pintype "bidirectional"))
      (node (ref "IC29") (pin "3") (pinfunction "VIN_3") (pintype "bidirectional"))
      (node (ref "IC30") (pin "VIN") (pinfunction "VIN_VIN") (pintype "bidirectional"))
      (node (ref "IC43") (pin "VIN") (pinfunction "VIN_VIN") (pintype "bidirectional"))
      (node (ref "J5") (pin "1") (pinfunction "1_1") (pintype "passive"))
      (node (ref "U$4") (pin "3") (pinfunction "VIN_3") (pintype "bidirectional"))
    )
    (net (code "6") (name "3.3V_RPI") (class "Default")
      (node (ref "IC1") (pin "VIN") (pinfunction "VIN_VIN") (pintype "bidirectional"))
      (node (ref "JP1") (pin "1") (pinfunction "1_1") (pintype "passive"))
      (node (ref "R163") (pin "1") (pinfunction "1_1") (pintype "passive"))
    )
    (net (code "7") (name "5V_2.5A") (class "Default")
      (node (ref "IC30") (pin "VOUT") (pinfunction "VOUT_VOUT") (pintype "bidirectional"))
      (node (ref "J2") (pin "1") (pinfunction "1_1") (pintype "bidirectional"))
    )
    (net (code "8") (name "5V_3.2A") (class "Default")
      (node (ref "IC27") (pin "6") (pinfunction "VOUT_6") (pintype "bidirectional"))
      (node (ref "J1") (pin "1") (pinfunction "1_1") (pintype "bidirectional"))
    )
    (net (code "9") (name "5V_RPI") (class "Default")
      (node (ref "JP1") (pin "4") (pinfunction "4_4") (pintype "passive"))
      (node (ref "JP5") (pin "3") (pinfunction "3_3") (pintype "passive"))
    )
    (net (code "10") (name "AINN1_1") (class "Default")
      (node (ref "C2") (pin "2") (pinfunction "2_2") (pintype "passive"))
      (node (ref "R2") (pin "1") (pinfunction "1_1") (pintype "passive"))
      (node (ref "R3") (pin "1") (pinfunction "1_1") (pintype "passive"))
      (node (ref "U11") (pin "4") (pinfunction "AINN1_4") (pintype "input"))
    )
    (net (code "11") (name "AINN1_2") (class "Default")
      (node (ref "C6") (pin "2") (pinfunction "2_2") (pintype "passive"))
      (node (ref "R8") (pin "1") (pinfunction "1_1") (pintype "passive"))
      (node (ref "R9") (pin "1") (pinfunction "1_1") (pintype "passive"))
      (node (ref "U11") (pin "2") (pinfunction "AINN2_2") (pintype "input"))
    )
    (net (code "12") (name "AINN1_3") (class "Default")
      (node (ref "C10") (pin "2") (pinfunction "2_2") (pintype "passive"))
      (node (ref "R14") (pin "1") (pinfunction "1_1") (pintype "passive"))
      (node (ref "R15") (pin "1") (pinfunction "1_1") (pintype "passive"))
      (node (ref "U11") (pin "64") (pinfunction "AINN3_64") (pintype "input"))
    )
    (net (code "13") (name "AINN1_4") (class "Default")
      (node (ref "C14") (pin "2") (pinfunction "2_2") (pintype "passive"))
      (node (ref "R20") (pin "1") (pinfunction "1_1") (pintype "passive"))
      (node (ref "R21") (pin "1") (pinfunction "1_1") (pintype "passive"))
      (node (ref "U11") (pin "62") (pinfunction "AINN4_62") (pintype "input"))
    )
    (net (code "14") (name "AINN1_5") (class "Default")
      (node (ref "C18") (pin "2") (pinfunction "2_2") (pintype "passive"))
      (node (ref "R26") (pin "1") (pinfunction "1_1") (pintype "passive"))
      (node (ref "R27") (pin "1") (pinfunction "1_1") (pintype "passive"))
      (node (ref "U11") (pin "52") (pinfunction "AINN5_52") (pintype "input"))
    )
    (net (code "15") (name "AINN1_6") (class "Default")
      (node (ref "C22") (pin "2") (pinfunction "2_2") (pintype "passive"))
      (node (ref "R32") (pin "1") (pinfunction "1_1") (pintype "passive"))
      (node (ref "R33") (pin "1") (pinfunction "1_1") (pintype "passive"))
      (node (ref "U11") (pin "50") (pinfunction "AINN6_50") (pintype "input"))
    )
    (net (code "16") (name "AINN1_7") (class "Default")
      (node (ref "C26") (pin "2") (pinfunction "2_2") (pintype "passive"))
      (node (ref "R38") (pin "1") (pinfunction "1_1") (pintype "passive"))
      (node (ref "R39") (pin "1") (pinfunction "1_1") (pintype "passive"))
      (node (ref "U11") (pin "48") (pinfunction "AINN7_48") (pintype "input"))
    )
    (net (code "17") (name "AINN1_8") (class "Default")
      (node (ref "C30") (pin "2") (pinfunction "2_2") (pintype "passive"))
      (node (ref "R44") (pin "1") (pinfunction "1_1") (pintype "passive"))
      (node (ref "R45") (pin "1") (pinfunction "1_1") (pintype "passive"))
      (node (ref "U11") (pin "46") (pinfunction "AINN8_46") (pintype "input"))
    )
    (net (code "18") (name "AINN2_1") (class "Default")
      (node (ref "C43") (pin "2") (pinfunction "2_2") (pintype "passive"))
      (node (ref "R56") (pin "1") (pinfunction "1_1") (pintype "passive"))
      (node (ref "R57") (pin "1") (pinfunction "1_1") (pintype "passive"))
      (node (ref "U6") (pin "4") (pinfunction "AINN1_4") (pintype "input"))
    )
    (net (code "19") (name "AINN2_2") (class "Default")
      (node (ref "C47") (pin "2") (pinfunction "2_2") (pintype "passive"))
      (node (ref "R62") (pin "1") (pinfunction "1_1") (pintype "passive"))
      (node (ref "R63") (pin "1") (pinfunction "1_1") (pintype "passive"))
      (node (ref "U6") (pin "2") (pinfunction "AINN2_2") (pintype "input"))
    )
    (net (code "20") (name "AINN2_3") (class "Default")
      (node (ref "C51") (pin "2") (pinfunction "2_2") (pintype "passive"))
      (node (ref "R68") (pin "1") (pinfunction "1_1") (pintype "passive"))
      (node (ref "R69") (pin "1") (pinfunction "1_1") (pintype "passive"))
      (node (ref "U6") (pin "64") (pinfunction "AINN3_64") (pintype "input"))
    )
    (net (code "21") (name "AINN2_4") (class "Default")
      (node (ref "C55") (pin "2") (pinfunction "2_2") (pintype "passive"))
      (node (ref "R74") (pin "1") (pinfunction "1_1") (pintype "passive"))
      (node (ref "R75") (pin "1") (pinfunction "1_1") (pintype "passive"))
      (node (ref "U6") (pin "62") (pinfunction "AINN4_62") (pintype "input"))
    )
    (net (code "22") (name "AINN2_5") (class "Default")
      (node (ref "C59") (pin "2") (pinfunction "2_2") (pintype "passive"))
      (node (ref "R80") (pin "1") (pinfunction "1_1") (pintype "passive"))
      (node (ref "R81") (pin "1") (pinfunction "1_1") (pintype "passive"))
      (node (ref "U6") (pin "52") (pinfunction "AINN5_52") (pintype "input"))
    )
    (net (code "23") (name "AINN2_6") (class "Default")
      (node (ref "C63") (pin "2") (pinfunction "2_2") (pintype "passive"))
      (node (ref "R86") (pin "1") (pinfunction "1_1") (pintype "passive"))
      (node (ref "R87") (pin "1") (pinfunction "1_1") (pintype "passive"))
      (node (ref "U6") (pin "50") (pinfunction "AINN6_50") (pintype "input"))
    )
    (net (code "24") (name "AINN2_7") (class "Default")
      (node (ref "C67") (pin "2") (pinfunction "2_2") (pintype "passive"))
      (node (ref "R92") (pin "1") (pinfunction "1_1") (pintype "passive"))
      (node (ref "R93") (pin "1") (pinfunction "1_1") (pintype "passive"))
      (node (ref "U6") (pin "48") (pinfunction "AINN7_48") (pintype "input"))
    )
    (net (code "25") (name "AINN2_8") (class "Default")
      (node (ref "C71") (pin "2") (pinfunction "2_2") (pintype "passive"))
      (node (ref "R98") (pin "1") (pinfunction "1_1") (pintype "passive"))
      (node (ref "R99") (pin "1") (pinfunction "1_1") (pintype "passive"))
      (node (ref "U6") (pin "46") (pinfunction "AINN8_46") (pintype "input"))
    )
    (net (code "26") (name "AINN3_1") (class "Default")
      (node (ref "C84") (pin "2") (pinfunction "2_2") (pintype "passive"))
      (node (ref "R110") (pin "1") (pinfunction "1_1") (pintype "passive"))
      (node (ref "R111") (pin "1") (pinfunction "1_1") (pintype "passive"))
      (node (ref "U9") (pin "4") (pinfunction "AINN1_4") (pintype "input"))
    )
    (net (code "27") (name "AINN3_2") (class "Default")
      (node (ref "C88") (pin "2") (pinfunction "2_2") (pintype "passive"))
      (node (ref "R116") (pin "1") (pinfunction "1_1") (pintype "passive"))
      (node (ref "R117") (pin "1") (pinfunction "1_1") (pintype "passive"))
      (node (ref "U9") (pin "2") (pinfunction "AINN2_2") (pintype "input"))
    )
    (net (code "28") (name "AINN3_3") (class "Default")
      (node (ref "C92") (pin "2") (pinfunction "2_2") (pintype "passive"))
      (node (ref "R122") (pin "1") (pinfunction "1_1") (pintype "passive"))
      (node (ref "R123") (pin "1") (pinfunction "1_1") (pintype "passive"))
      (node (ref "U9") (pin "64") (pinfunction "AINN3_64") (pintype "input"))
    )
    (net (code "29") (name "AINN3_4") (class "Default")
      (node (ref "C96") (pin "2") (pinfunction "2_2") (pintype "passive"))
      (node (ref "R128") (pin "1") (pinfunction "1_1") (pintype "passive"))
      (node (ref "R129") (pin "1") (pinfunction "1_1") (pintype "passive"))
      (node (ref "U9") (pin "62") (pinfunction "AINN4_62") (pintype "input"))
    )
    (net (code "30") (name "AINN3_5") (class "Default")
      (node (ref "U9") (pin "52") (pinfunction "AINN5_52") (pintype "input"))
    )
    (net (code "31") (name "AINN3_6") (class "Default")
      (node (ref "U9") (pin "50") (pinfunction "AINN6_50") (pintype "input"))
    )
    (net (code "32") (name "AINN3_7") (class "Default")
      (node (ref "U9") (pin "48") (pinfunction "AINN7_48") (pintype "input"))
    )
    (net (code "33") (name "AINN3_8") (class "Default")
      (node (ref "U9") (pin "46") (pinfunction "AINN8_46") (pintype "input"))
    )
    (net (code "34") (name "AINP1_1") (class "Default")
      (node (ref "C2") (pin "1") (pinfunction "1_1") (pintype "passive"))
      (node (ref "R5") (pin "1") (pinfunction "1_1") (pintype "passive"))
      (node (ref "R6") (pin "1") (pinfunction "1_1") (pintype "passive"))
      (node (ref "U11") (pin "3") (pinfunction "AINP1_3") (pintype "input"))
    )
    (net (code "35") (name "AINP1_2") (class "Default")
      (node (ref "C6") (pin "1") (pinfunction "1_1") (pintype "passive"))
      (node (ref "R11") (pin "1") (pinfunction "1_1") (pintype "passive"))
      (node (ref "R12") (pin "1") (pinfunction "1_1") (pintype "passive"))
      (node (ref "U11") (pin "1") (pinfunction "AINP2_1") (pintype "input"))
    )
    (net (code "36") (name "AINP1_3") (class "Default")
      (node (ref "C10") (pin "1") (pinfunction "1_1") (pintype "passive"))
      (node (ref "R17") (pin "1") (pinfunction "1_1") (pintype "passive"))
      (node (ref "R18") (pin "1") (pinfunction "1_1") (pintype "passive"))
      (node (ref "U11") (pin "63") (pinfunction "AINP3_63") (pintype "input"))
    )
    (net (code "37") (name "AINP1_4") (class "Default")
      (node (ref "C14") (pin "1") (pinfunction "1_1") (pintype "passive"))
      (node (ref "R23") (pin "1") (pinfunction "1_1") (pintype "passive"))
      (node (ref "R24") (pin "1") (pinfunction "1_1") (pintype "passive"))
      (node (ref "U11") (pin "61") (pinfunction "AINP4_61") (pintype "input"))
    )
    (net (code "38") (name "AINP1_5") (class "Default")
      (node (ref "C18") (pin "1") (pinfunction "1_1") (pintype "passive"))
      (node (ref "R29") (pin "1") (pinfunction "1_1") (pintype "passive"))
      (node (ref "R30") (pin "1") (pinfunction "1_1") (pintype "passive"))
      (node (ref "U11") (pin "51") (pinfunction "AINP5_51") (pintype "input"))
    )
    (net (code "39") (name "AINP1_6") (class "Default")
      (node (ref "C22") (pin "1") (pinfunction "1_1") (pintype "passive"))
      (node (ref "R35") (pin "1") (pinfunction "1_1") (pintype "passive"))
      (node (ref "R36") (pin "1") (pinfunction "1_1") (pintype "passive"))
      (node (ref "U11") (pin "49") (pinfunction "AINP6_49") (pintype "input"))
    )
    (net (code "40") (name "AINP1_7") (class "Default")
      (node (ref "C26") (pin "1") (pinfunction "1_1") (pintype "passive"))
      (node (ref "R41") (pin "1") (pinfunction "1_1") (pintype "passive"))
      (node (ref "R42") (pin "1") (pinfunction "1_1") (pintype "passive"))
      (node (ref "U11") (pin "47") (pinfunction "AINP7_47") (pintype "input"))
    )
    (net (code "41") (name "AINP1_8") (class "Default")
      (node (ref "C30") (pin "1") (pinfunction "1_1") (pintype "passive"))
      (node (ref "R47") (pin "1") (pinfunction "1_1") (pintype "passive"))
      (node (ref "R48") (pin "1") (pinfunction "1_1") (pintype "passive"))
      (node (ref "U11") (pin "45") (pinfunction "AINP8_45") (pintype "input"))
    )
    (net (code "42") (name "AINP2_1") (class "Default")
      (node (ref "C43") (pin "1") (pinfunction "1_1") (pintype "passive"))
      (node (ref "R59") (pin "1") (pinfunction "1_1") (pintype "passive"))
      (node (ref "R60") (pin "1") (pinfunction "1_1") (pintype "passive"))
      (node (ref "U6") (pin "3") (pinfunction "AINP1_3") (pintype "input"))
    )
    (net (code "43") (name "AINP2_2") (class "Default")
      (node (ref "C47") (pin "1") (pinfunction "1_1") (pintype "passive"))
      (node (ref "R65") (pin "1") (pinfunction "1_1") (pintype "passive"))
      (node (ref "R66") (pin "1") (pinfunction "1_1") (pintype "passive"))
      (node (ref "U6") (pin "1") (pinfunction "AINP2_1") (pintype "input"))
    )
    (net (code "44") (name "AINP2_3") (class "Default")
      (node (ref "C51") (pin "1") (pinfunction "1_1") (pintype "passive"))
      (node (ref "R71") (pin "1") (pinfunction "1_1") (pintype "passive"))
      (node (ref "R72") (pin "1") (pinfunction "1_1") (pintype "passive"))
      (node (ref "U6") (pin "63") (pinfunction "AINP3_63") (pintype "input"))
    )
    (net (code "45") (name "AINP2_4") (class "Default")
      (node (ref "C55") (pin "1") (pinfunction "1_1") (pintype "passive"))
      (node (ref "R77") (pin "1") (pinfunction "1_1") (pintype "passive"))
      (node (ref "R78") (pin "1") (pinfunction "1_1") (pintype "passive"))
      (node (ref "U6") (pin "61") (pinfunction "AINP4_61") (pintype "input"))
    )
    (net (code "46") (name "AINP2_5") (class "Default")
      (node (ref "C59") (pin "1") (pinfunction "1_1") (pintype "passive"))
      (node (ref "R83") (pin "1") (pinfunction "1_1") (pintype "passive"))
      (node (ref "R84") (pin "1") (pinfunction "1_1") (pintype "passive"))
      (node (ref "U6") (pin "51") (pinfunction "AINP5_51") (pintype "input"))
    )
    (net (code "47") (name "AINP2_6") (class "Default")
      (node (ref "C63") (pin "1") (pinfunction "1_1") (pintype "passive"))
      (node (ref "R89") (pin "1") (pinfunction "1_1") (pintype "passive"))
      (node (ref "R90") (pin "1") (pinfunction "1_1") (pintype "passive"))
      (node (ref "U6") (pin "49") (pinfunction "AINP6_49") (pintype "input"))
    )
    (net (code "48") (name "AINP2_7") (class "Default")
      (node (ref "C67") (pin "1") (pinfunction "1_1") (pintype "passive"))
      (node (ref "R95") (pin "1") (pinfunction "1_1") (pintype "passive"))
      (node (ref "R96") (pin "1") (pinfunction "1_1") (pintype "passive"))
      (node (ref "U6") (pin "47") (pinfunction "AINP7_47") (pintype "input"))
    )
    (net (code "49") (name "AINP2_8") (class "Default")
      (node (ref "C71") (pin "1") (pinfunction "1_1") (pintype "passive"))
      (node (ref "R101") (pin "1") (pinfunction "1_1") (pintype "passive"))
      (node (ref "R102") (pin "1") (pinfunction "1_1") (pintype "passive"))
      (node (ref "U6") (pin "45") (pinfunction "AINP8_45") (pintype "input"))
    )
    (net (code "50") (name "AINP3_1") (class "Default")
      (node (ref "C84") (pin "1") (pinfunction "1_1") (pintype "passive"))
      (node (ref "R113") (pin "1") (pinfunction "1_1") (pintype "passive"))
      (node (ref "R114") (pin "1") (pinfunction "1_1") (pintype "passive"))
      (node (ref "U9") (pin "3") (pinfunction "AINP1_3") (pintype "input"))
    )
    (net (code "51") (name "AINP3_2") (class "Default")
      (node (ref "C88") (pin "1") (pinfunction "1_1") (pintype "passive"))
      (node (ref "R119") (pin "1") (pinfunction "1_1") (pintype "passive"))
      (node (ref "R120") (pin "1") (pinfunction "1_1") (pintype "passive"))
      (node (ref "U9") (pin "1") (pinfunction "AINP2_1") (pintype "input"))
    )
    (net (code "52") (name "AINP3_3") (class "Default")
      (node (ref "C92") (pin "1") (pinfunction "1_1") (pintype "passive"))
      (node (ref "R125") (pin "1") (pinfunction "1_1") (pintype "passive"))
      (node (ref "R126") (pin "1") (pinfunction "1_1") (pintype "passive"))
      (node (ref "U9") (pin "63") (pinfunction "AINP3_63") (pintype "input"))
    )
    (net (code "53") (name "AINP3_4") (class "Default")
      (node (ref "C96") (pin "1") (pinfunction "1_1") (pintype "passive"))
      (node (ref "R131") (pin "1") (pinfunction "1_1") (pintype "passive"))
      (node (ref "R132") (pin "1") (pinfunction "1_1") (pintype "passive"))
      (node (ref "U9") (pin "61") (pinfunction "AINP4_61") (pintype "input"))
    )
    (net (code "54") (name "AINP3_5") (class "Default")
      (node (ref "U9") (pin "51") (pinfunction "AINP5_51") (pintype "input"))
    )
    (net (code "55") (name "AINP3_6") (class "Default")
      (node (ref "U9") (pin "49") (pinfunction "AINP6_49") (pintype "input"))
    )
    (net (code "56") (name "AINP3_7") (class "Default")
      (node (ref "U9") (pin "47") (pinfunction "AINP7_47") (pintype "input"))
    )
    (net (code "57") (name "AINP3_8") (class "Default")
      (node (ref "U9") (pin "45") (pinfunction "AINP8_45") (pintype "input"))
    )
    (net (code "58") (name "CLK1") (class "Default")
      (node (ref "JP3") (pin "3") (pinfunction "3_3") (pintype "passive"))
      (node (ref "U11") (pin "27") (pinfunction "CLKDIV_27") (pintype "input"))
    )
    (net (code "59") (name "CLK2") (class "Default")
      (node (ref "JP3") (pin "24") (pinfunction "24_24") (pintype "passive"))
      (node (ref "U6") (pin "27") (pinfunction "CLKDIV_27") (pintype "input"))
    )
    (net (code "60") (name "CLK3") (class "Default")
      (node (ref "JP2") (pin "9") (pinfunction "9_9") (pintype "passive"))
      (node (ref "U9") (pin "27") (pinfunction "CLKDIV_27") (pintype "input"))
    )
    (net (code "61") (name "DOBLE1") (class "Default")
      (node (ref "IC31") (pin "3") (pinfunction "IN+_3") (pintype "bidirectional"))
      (node (ref "J4") (pin "1") (pinfunction "1_1") (pintype "passive"))
      (node (ref "R143") (pin "1") (pinfunction "1_1") (pintype "passive"))
    )
    (net (code "62") (name "DOBLE2") (class "Default")
      (node (ref "IC32") (pin "3") (pinfunction "IN+_3") (pintype "bidirectional"))
      (node (ref "J4") (pin "2") (pinfunction "2_2") (pintype "passive"))
      (node (ref "R144") (pin "1") (pinfunction "1_1") (pintype "passive"))
    )
    (net (code "63") (name "DOBLE3") (class "Default")
      (node (ref "IC33") (pin "3") (pinfunction "IN+_3") (pintype "bidirectional"))
      (node (ref "J4") (pin "3") (pinfunction "3_3") (pintype "passive"))
      (node (ref "R145") (pin "1") (pinfunction "1_1") (pintype "passive"))
    )
    (net (code "64") (name "DOBLE4") (class "Default")
      (node (ref "IC34") (pin "3") (pinfunction "IN+_3") (pintype "bidirectional"))
      (node (ref "J4") (pin "4") (pinfunction "4_4") (pintype "passive"))
      (node (ref "R146") (pin "1") (pinfunction "1_1") (pintype "passive"))
    )
    (net (code "65") (name "DOUT1_1") (class "Default")
      (node (ref "JP3") (pin "4") (pinfunction "4_4") (pintype "passive"))
      (node (ref "U11") (pin "20") (pinfunction "DOUT1_20") (pintype "output"))
    )
    (net (code "66") (name "DOUT1_2") (class "Default")
      (node (ref "JP3") (pin "5") (pinfunction "5_5") (pintype "passive"))
      (node (ref "U11") (pin "19") (pinfunction "DOUT2_19") (pintype "output"))
    )
    (net (code "67") (name "DOUT1_3") (class "Default")
      (node (ref "JP3") (pin "6") (pinfunction "6_6") (pintype "passive"))
      (node (ref "U11") (pin "18") (pinfunction "DOUT3_18") (pintype "output"))
    )
    (net (code "68") (name "DOUT1_4") (class "Default")
      (node (ref "JP3") (pin "7") (pinfunction "7_7") (pintype "passive"))
      (node (ref "U11") (pin "17") (pinfunction "DOUT4_17") (pintype "output"))
    )
    (net (code "69") (name "DOUT1_5") (class "Default")
      (node (ref "JP3") (pin "8") (pinfunction "8_8") (pintype "passive"))
      (node (ref "U11") (pin "16") (pinfunction "DOUT5_16") (pintype "output"))
    )
    (net (code "70") (name "DOUT1_6") (class "Default")
      (node (ref "JP3") (pin "9") (pinfunction "9_9") (pintype "passive"))
      (node (ref "U11") (pin "15") (pinfunction "DOUT6_15") (pintype "output"))
    )
    (net (code "71") (name "DOUT1_7") (class "Default")
      (node (ref "JP3") (pin "10") (pinfunction "10_10") (pintype "passive"))
      (node (ref "U11") (pin "14") (pinfunction "DOUT7_14") (pintype "output"))
    )
    (net (code "72") (name "DOUT1_8") (class "Default")
      (node (ref "JP3") (pin "13") (pinfunction "13_13") (pintype "passive"))
      (node (ref "U11") (pin "13") (pinfunction "DOUT8_13") (pintype "output"))
    )
    (net (code "73") (name "DOUT2_1") (class "Default")
      (node (ref "JP3") (pin "23") (pinfunction "23_23") (pintype "passive"))
      (node (ref "U6") (pin "20") (pinfunction "DOUT1_20") (pintype "output"))
    )
    (net (code "74") (name "DOUT2_2") (class "Default")
      (node (ref "JP3") (pin "22") (pinfunction "22_22") (pintype "passive"))
      (node (ref "U6") (pin "19") (pinfunction "DOUT2_19") (pintype "output"))
    )
    (net (code "75") (name "DOUT2_3") (class "Default")
      (node (ref "JP3") (pin "21") (pinfunction "21_21") (pintype "passive"))
      (node (ref "U6") (pin "18") (pinfunction "DOUT3_18") (pintype "output"))
    )
    (net (code "76") (name "DOUT2_4") (class "Default")
      (node (ref "JP3") (pin "20") (pinfunction "20_20") (pintype "passive"))
      (node (ref "U6") (pin "17") (pinfunction "DOUT4_17") (pintype "output"))
    )
    (net (code "77") (name "DOUT2_5") (class "Default")
      (node (ref "JP3") (pin "19") (pinfunction "19_19") (pintype "passive"))
      (node (ref "U6") (pin "16") (pinfunction "DOUT5_16") (pintype "output"))
    )
    (net (code "78") (name "DOUT2_6") (class "Default")
      (node (ref "JP3") (pin "18") (pinfunction "18_18") (pintype "passive"))
      (node (ref "U6") (pin "15") (pinfunction "DOUT6_15") (pintype "output"))
    )
    (net (code "79") (name "DOUT2_7") (class "Default")
      (node (ref "JP3") (pin "17") (pinfunction "17_17") (pintype "passive"))
      (node (ref "U6") (pin "14") (pinfunction "DOUT7_14") (pintype "output"))
    )
    (net (code "80") (name "DOUT2_8") (class "Default")
      (node (ref "JP3") (pin "16") (pinfunction "16_16") (pintype "passive"))
      (node (ref "U6") (pin "13") (pinfunction "DOUT8_13") (pintype "output"))
    )
    (net (code "81") (name "DOUT3_1") (class "Default")
      (node (ref "JP2") (pin "13") (pinfunction "13_13") (pintype "passive"))
      (node (ref "U9") (pin "20") (pinfunction "DOUT1_20") (pintype "output"))
    )
    (net (code "82") (name "DOUT3_2") (class "Default")
      (node (ref "JP2") (pin "16") (pinfunction "16_16") (pintype "passive"))
      (node (ref "U9") (pin "19") (pinfunction "DOUT2_19") (pintype "output"))
    )
    (net (code "83") (name "DOUT3_3") (class "Default")
      (node (ref "JP2") (pin "15") (pinfunction "15_15") (pintype "passive"))
      (node (ref "U9") (pin "18") (pinfunction "DOUT3_18") (pintype "output"))
    )
    (net (code "84") (name "DOUT3_4") (class "Default")
      (node (ref "JP2") (pin "18") (pinfunction "18_18") (pintype "passive"))
      (node (ref "U9") (pin "17") (pinfunction "DOUT4_17") (pintype "output"))
    )
    (net (code "85") (name "DOUT3_5") (class "Default")
      (node (ref "U9") (pin "16") (pinfunction "DOUT5_16") (pintype "output"))
    )
    (net (code "86") (name "DOUT3_6") (class "Default")
      (node (ref "U9") (pin "15") (pinfunction "DOUT6_15") (pintype "output"))
    )
    (net (code "87") (name "DOUT3_7") (class "Default")
      (node (ref "U9") (pin "14") (pinfunction "DOUT7_14") (pintype "output"))
    )
    (net (code "88") (name "DOUT3_8") (class "Default")
      (node (ref "U9") (pin "13") (pinfunction "DOUT8_13") (pintype "output"))
    )
    (net (code "89") (name "DRDY1") (class "Default")
      (node (ref "JP3") (pin "1") (pinfunction "1_1") (pintype "passive"))
      (node (ref "U11") (pin "29") (pinfunction "~{DRDY/FSYNC}_29") (pintype "bidirectional"))
    )
    (net (code "90") (name "DRDY2") (class "Default")
      (node (ref "JP3") (pin "26") (pinfunction "26_26") (pintype "passive"))
      (node (ref "U6") (pin "29") (pinfunction "~{DRDY/FSYNC}_29") (pintype "bidirectional"))
    )
    (net (code "91") (name "DRDY3") (class "Default")
      (node (ref "JP2") (pin "14") (pinfunction "14_14") (pintype "passive"))
      (node (ref "U9") (pin "29") (pinfunction "~{DRDY/FSYNC}_29") (pintype "bidirectional"))
    )
    (net (code "92") (name "GND") (class "Default")
      (node (ref "C100") (pin "2") (pinfunction "2_2") (pintype "passive"))
      (node (ref "C102") (pin "2") (pinfunction "2_2") (pintype "passive"))
      (node (ref "C103") (pin "2") (pinfunction "2_2") (pintype "passive"))
      (node (ref "C104") (pin "2") (pinfunction "2_2") (pintype "passive"))
      (node (ref "C105") (pin "2") (pinfunction "2_2") (pintype "passive"))
      (node (ref "C106") (pin "2") (pinfunction "2_2") (pintype "passive"))
      (node (ref "C107") (pin "2") (pinfunction "2_2") (pintype "passive"))
      (node (ref "C11") (pin "2") (pinfunction "2_2") (pintype "passive"))
      (node (ref "C114") (pin "2") (pinfunction "2_2") (pintype "passive"))
      (node (ref "C115") (pin "2") (pinfunction "2_2") (pintype "passive"))
      (node (ref "C116") (pin "2") (pinfunction "2_2") (pintype "passive"))
      (node (ref "C117") (pin "2") (pinfunction "2_2") (pintype "passive"))
      (node (ref "C118") (pin "2") (pinfunction "2_2") (pintype "passive"))
      (node (ref "C119") (pin "2") (pinfunction "2_2") (pintype "passive"))
      (node (ref "C15") (pin "2") (pinfunction "2_2") (pintype "passive"))
      (node (ref "C19") (pin "2") (pinfunction "2_2") (pintype "passive"))
      (node (ref "C23") (pin "2") (pinfunction "2_2") (pintype "passive"))
      (node (ref "C27") (pin "2") (pinfunction "2_2") (pintype "passive"))
      (node (ref "C3") (pin "2") (pinfunction "2_2") (pintype "passive"))
      (node (ref "C31") (pin "2") (pinfunction "2_2") (pintype "passive"))
      (node (ref "C33") (pin "2") (pinfunction "2_2") (pintype "passive"))
      (node (ref "C34") (pin "2") (pinfunction "2_2") (pintype "passive"))
      (node (ref "C36") (pin "2") (pinfunction "2_2") (pintype "passive"))
      (node (ref "C37") (pin "2") (pinfunction "2_2") (pintype "passive"))
      (node (ref "C38") (pin "2") (pinfunction "2_2") (pintype "passive"))
      (node (ref "C39") (pin "2") (pinfunction "2_2") (pintype "passive"))
      (node (ref "C40") (pin "2") (pinfunction "2_2") (pintype "passive"))
      (node (ref "C41") (pin "2") (pinfunction "2_2") (pintype "passive"))
      (node (ref "C44") (pin "2") (pinfunction "2_2") (pintype "passive"))
      (node (ref "C48") (pin "2") (pinfunction "2_2") (pintype "passive"))
      (node (ref "C52") (pin "2") (pinfunction "2_2") (pintype "passive"))
      (node (ref "C56") (pin "2") (pinfunction "2_2") (pintype "passive"))
      (node (ref "C60") (pin "2") (pinfunction "2_2") (pintype "passive"))
      (node (ref "C64") (pin "2") (pinfunction "2_2") (pintype "passive"))
      (node (ref "C68") (pin "2") (pinfunction "2_2") (pintype "passive"))
      (node (ref "C7") (pin "2") (pinfunction "2_2") (pintype "passive"))
      (node (ref "C72") (pin "2") (pinfunction "2_2") (pintype "passive"))
      (node (ref "C74") (pin "2") (pinfunction "2_2") (pintype "passive"))
      (node (ref "C75") (pin "2") (pinfunction "2_2") (pintype "passive"))
      (node (ref "C77") (pin "2") (pinfunction "2_2") (pintype "passive"))
      (node (ref "C78") (pin "2") (pinfunction "2_2") (pintype "passive"))
      (node (ref "C79") (pin "2") (pinfunction "2_2") (pintype "passive"))
      (node (ref "C80") (pin "2") (pinfunction "2_2") (pintype "passive"))
      (node (ref "C81") (pin "2") (pinfunction "2_2") (pintype "passive"))
      (node (ref "C82") (pin "2") (pinfunction "2_2") (pintype "passive"))
      (node (ref "C85") (pin "2") (pinfunction "2_2") (pintype "passive"))
      (node (ref "C89") (pin "2") (pinfunction "2_2") (pintype "passive"))
      (node (ref "C93") (pin "2") (pinfunction "2_2") (pintype "passive"))
      (node (ref "C97") (pin "2") (pinfunction "2_2") (pintype "passive"))
      (node (ref "C99") (pin "2") (pinfunction "2_2") (pintype "passive"))
      (node (ref "IC1") (pin "GND") (pinfunction "GND_GND") (pintype "bidirectional"))
      (node (ref "IC27") (pin "4") (pinfunction "GND_4") (pintype "bidirectional"))
      (node (ref "IC27") (pin "5") (pinfunction "GND_5") (pintype "bidirectional"))
      (node (ref "IC28") (pin "3") (pinfunction "GND_3") (pintype "bidirectional"))
      (node (ref "IC29") (pin "4") (pinfunction "GND_4") (pintype "bidirectional"))
      (node (ref "IC30") (pin "GND@3") (pinfunction "GND_GND@3") (pintype "bidirectional"))
      (node (ref "IC30") (pin "GND@4") (pinfunction "GND_GND@4") (pintype "bidirectional"))
      (node (ref "IC31") (pin "2") (pinfunction "GND_2") (pintype "bidirectional"))
      (node (ref "IC32") (pin "2") (pinfunction "GND_2") (pintype "bidirectional"))
      (node (ref "IC33") (pin "2") (pinfunction "GND_2") (pintype "bidirectional"))
      (node (ref "IC34") (pin "2") (pinfunction "GND_2") (pintype "bidirectional"))
      (node (ref "IC35") (pin "3") (pinfunction "EMITTER_3") (pintype "bidirectional"))
      (node (ref "IC36") (pin "3") (pinfunction "EMITTER_3") (pintype "bidirectional"))
      (node (ref "IC37") (pin "3") (pinfunction "EMITTER_3") (pintype "bidirectional"))
      (node (ref "IC38") (pin "3") (pinfunction "EMITTER_3") (pintype "bidirectional"))
      (node (ref "IC39") (pin "3") (pinfunction "EMITTER_3") (pintype "bidirectional"))
      (node (ref "IC40") (pin "3") (pinfunction "EMITTER_3") (pintype "bidirectional"))
      (node (ref "IC41") (pin "3") (pinfunction "EMITTER_3") (pintype "bidirectional"))
      (node (ref "IC42") (pin "3") (pinfunction "EMITTER_3") (pintype "bidirectional"))
      (node (ref "IC43") (pin "GND@3") (pinfunction "GND_GND@3") (pintype "bidirectional"))
      (node (ref "IC43") (pin "GND@4") (pinfunction "GND_GND@4") (pintype "bidirectional"))
      (node (ref "J1") (pin "2") (pinfunction "2_2") (pintype "bidirectional"))
      (node (ref "J2") (pin "2") (pinfunction "2_2") (pintype "bidirectional"))
      (node (ref "J5") (pin "2") (pinfunction "2_2") (pintype "passive"))
      (node (ref "J6") (pin "2") (pinfunction "2_2") (pintype "bidirectional"))
      (node (ref "JP1") (pin "14") (pinfunction "14_14") (pintype "passive"))
      (node (ref "JP1") (pin "20") (pinfunction "20_20") (pintype "passive"))
      (node (ref "JP1") (pin "25") (pinfunction "25_25") (pintype "passive"))
      (node (ref "JP1") (pin "30") (pinfunction "30_30") (pintype "passive"))
      (node (ref "JP1") (pin "34") (pinfunction "34_34") (pintype "passive"))
      (node (ref "JP1") (pin "39") (pinfunction "39_39") (pintype "passive"))
      (node (ref "JP1") (pin "6") (pinfunction "6_6") (pintype "passive"))
      (node (ref "JP1") (pin "9") (pinfunction "9_9") (pintype "passive"))
      (node (ref "JP2") (pin "12") (pinfunction "12_12") (pintype "passive"))
      (node (ref "JP2") (pin "30") (pinfunction "30_30") (pintype "passive"))
      (node (ref "JP3") (pin "12") (pinfunction "12_12") (pintype "passive"))
      (node (ref "JP3") (pin "30") (pinfunction "30_30") (pintype "passive"))
      (node (ref "JP4") (pin "33") (pinfunction "33_33") (pintype "passive"))
      (node (ref "JP4") (pin "34") (pinfunction "34_34") (pintype "passive"))
      (node (ref "JP4") (pin "37") (pinfunction "37_37") (pintype "passive"))
      (node (ref "JP4") (pin "38") (pinfunction "38_38") (pintype "passive"))
      (node (ref "JP5") (pin "2") (pinfunction "2_2") (pintype "passive"))
      (node (ref "JP6") (pin "10") (pinfunction "10_10") (pintype "passive"))
      (node (ref "JP6") (pin "2") (pinfunction "2_2") (pintype "passive"))
      (node (ref "JP6") (pin "4") (pinfunction "4_4") (pintype "passive"))
      (node (ref "JP6") (pin "6") (pinfunction "6_6") (pintype "passive"))
      (node (ref "JP6") (pin "8") (pinfunction "8_8") (pintype "passive"))
      (node (ref "R107") (pin "1") (pinfunction "1_1") (pintype "passive"))
      (node (ref "R112") (pin "2") (pinfunction "2_2") (pintype "passive"))
      (node (ref "R118") (pin "2") (pinfunction "2_2") (pintype "passive"))
      (node (ref "R124") (pin "2") (pinfunction "2_2") (pintype "passive"))
      (node (ref "R130") (pin "2") (pinfunction "2_2") (pintype "passive"))
      (node (ref "R143") (pin "2") (pinfunction "2_2") (pintype "passive"))
      (node (ref "R144") (pin "2") (pinfunction "2_2") (pintype "passive"))
      (node (ref "R145") (pin "2") (pinfunction "2_2") (pintype "passive"))
      (node (ref "R146") (pin "2") (pinfunction "2_2") (pintype "passive"))
      (node (ref "R164") (pin "1") (pinfunction "1_1") (pintype "passive"))
      (node (ref "R165") (pin "1") (pinfunction "1_1") (pintype "passive"))
      (node (ref "R53") (pin "1") (pinfunction "1_1") (pintype "passive"))
      (node (ref "U$4") (pin "4") (pinfunction "GND_4") (pintype "bidirectional"))
      (node (ref "U1") (pin "4") (pinfunction "V-_4") (pintype "power_in"))
      (node (ref "U11") (pin "12") (pinfunction "DIN_12") (pintype "input"))
      (node (ref "U11") (pin "21") (pinfunction "DGND_3_21") (pintype "power_in"))
      (node (ref "U11") (pin "24") (pinfunction "DGND_4_24") (pintype "power_in"))
      (node (ref "U11") (pin "25") (pinfunction "DGND_25") (pintype "power_in"))
      (node (ref "U11") (pin "30") (pinfunction "FORMAT2_30") (pintype "input"))
      (node (ref "U11") (pin "32") (pinfunction "FORMAT0_32") (pintype "input"))
      (node (ref "U11") (pin "33") (pinfunction "MODE1_33") (pintype "input"))
      (node (ref "U11") (pin "34") (pinfunction "MODE0_34") (pintype "input"))
      (node (ref "U11") (pin "43") (pinfunction "AGND_3_43") (pintype "power_in"))
      (node (ref "U11") (pin "54") (pinfunction "AGND_4_54") (pintype "power_in"))
      (node (ref "U11") (pin "57") (pinfunction "VREFN_57") (pintype "input"))
      (node (ref "U11") (pin "58") (pinfunction "AGND_5_58") (pintype "power_in"))
      (node (ref "U11") (pin "59") (pinfunction "AGND_59") (pintype "power_in"))
      (node (ref "U11") (pin "6") (pinfunction "AGND_2_6") (pintype "power_in"))
      (node (ref "U11") (pin "65") (pinfunction "EPAD_65") (pintype "power_in"))
      (node (ref "U11") (pin "7") (pinfunction "DGND_2_7") (pintype "power_in"))
      (node (ref "U11") (pin "8") (pinfunction "TEST0_8") (pintype "input"))
      (node (ref "U11") (pin "9") (pinfunction "TEST1_9") (pintype "input"))
      (node (ref "U12") (pin "4") (pinfunction "GND_4") (pintype "passive"))
      (node (ref "U13") (pin "4") (pinfunction "GND_4") (pintype "passive"))
      (node (ref "U14") (pin "6") (pinfunction "VS-_6") (pintype "power_in"))
      (node (ref "U15") (pin "6") (pinfunction "VS-_6") (pintype "power_in"))
      (node (ref "U16") (pin "6") (pinfunction "VS-_6") (pintype "power_in"))
      (node (ref "U17") (pin "6") (pinfunction "VS-_6") (pintype "power_in"))
      (node (ref "U18") (pin "6") (pinfunction "VS-_6") (pintype "power_in"))
      (node (ref "U19") (pin "6") (pinfunction "VS-_6") (pintype "power_in"))
      (node (ref "U2") (pin "4") (pinfunction "V-_4") (pintype "power_in"))
      (node (ref "U20") (pin "6") (pinfunction "VS-_6") (pintype "power_in"))
      (node (ref "U21") (pin "6") (pinfunction "VS-_6") (pintype "power_in"))
      (node (ref "U22") (pin "6") (pinfunction "VS-_6") (pintype "power_in"))
      (node (ref "U23") (pin "6") (pinfunction "VS-_6") (pintype "power_in"))
      (node (ref "U24") (pin "6") (pinfunction "VS-_6") (pintype "power_in"))
      (node (ref "U25") (pin "6") (pinfunction "VS-_6") (pintype "power_in"))
      (node (ref "U26") (pin "6") (pinfunction "VS-_6") (pintype "power_in"))
      (node (ref "U27") (pin "6") (pinfunction "VS-_6") (pintype "power_in"))
      (node (ref "U28") (pin "6") (pinfunction "VS-_6") (pintype "power_in"))
      (node (ref "U29") (pin "6") (pinfunction "VS-_6") (pintype "power_in"))
      (node (ref "U3") (pin "4") (pinfunction "GND_4") (pintype "passive"))
      (node (ref "U30") (pin "6") (pinfunction "VS-_6") (pintype "power_in"))
      (node (ref "U31") (pin "6") (pinfunction "VS-_6") (pintype "power_in"))
      (node (ref "U32") (pin "6") (pinfunction "VS-_6") (pintype "power_in"))
      (node (ref "U33") (pin "6") (pinfunction "VS-_6") (pintype "power_in"))
      (node (ref "U4") (pin "4") (pinfunction "V-_4") (pintype "power_in"))
      (node (ref "U5") (pin "4") (pinfunction "V-_4") (pintype "power_in"))
      (node (ref "U6") (pin "12") (pinfunction "DIN_12") (pintype "input"))
      (node (ref "U6") (pin "21") (pinfunction "DGND_3_21") (pintype "power_in"))
      (node (ref "U6") (pin "24") (pinfunction "DGND_4_24") (pintype "power_in"))
      (node (ref "U6") (pin "25") (pinfunction "DGND_25") (pintype "power_in"))
      (node (ref "U6") (pin "30") (pinfunction "FORMAT2_30") (pintype "input"))
      (node (ref "U6") (pin "32") (pinfunction "FORMAT0_32") (pintype "input"))
      (node (ref "U6") (pin "33") (pinfunction "MODE1_33") (pintype "input"))
      (node (ref "U6") (pin "34") (pinfunction "MODE0_34") (pintype "input"))
      (node (ref "U6") (pin "43") (pinfunction "AGND_3_43") (pintype "power_in"))
      (node (ref "U6") (pin "54") (pinfunction "AGND_4_54") (pintype "power_in"))
      (node (ref "U6") (pin "57") (pinfunction "VREFN_57") (pintype "input"))
      (node (ref "U6") (pin "58") (pinfunction "AGND_5_58") (pintype "power_in"))
      (node (ref "U6") (pin "59") (pinfunction "AGND_59") (pintype "power_in"))
      (node (ref "U6") (pin "6") (pinfunction "AGND_2_6") (pintype "power_in"))
      (node (ref "U6") (pin "65") (pinfunction "EPAD_65") (pintype "power_in"))
      (node (ref "U6") (pin "7") (pinfunction "DGND_2_7") (pintype "power_in"))
      (node (ref "U6") (pin "8") (pinfunction "TEST0_8") (pintype "input"))
      (node (ref "U6") (pin "9") (pinfunction "TEST1_9") (pintype "input"))
      (node (ref "U7") (pin "4") (pinfunction "V-_4") (pintype "power_in"))
      (node (ref "U8") (pin "4") (pinfunction "V-_4") (pintype "power_in"))
      (node (ref "U9") (pin "12") (pinfunction "DIN_12") (pintype "input"))
      (node (ref "U9") (pin "21") (pinfunction "DGND_3_21") (pintype "power_in"))
      (node (ref "U9") (pin "24") (pinfunction "DGND_4_24") (pintype "power_in"))
      (node (ref "U9") (pin "25") (pinfunction "DGND_25") (pintype "power_in"))
      (node (ref "U9") (pin "30") (pinfunction "FORMAT2_30") (pintype "input"))
      (node (ref "U9") (pin "32") (pinfunction "FORMAT0_32") (pintype "input"))
      (node (ref "U9") (pin "33") (pinfunction "MODE1_33") (pintype "input"))
      (node (ref "U9") (pin "34") (pinfunction "MODE0_34") (pintype "input"))
      (node (ref "U9") (pin "43") (pinfunction "AGND_3_43") (pintype "power_in"))
      (node (ref "U9") (pin "54") (pinfunction "AGND_4_54") (pintype "power_in"))
      (node (ref "U9") (pin "57") (pinfunction "VREFN_57") (pintype "input"))
      (node (ref "U9") (pin "58") (pinfunction "AGND_5_58") (pintype "power_in"))
      (node (ref "U9") (pin "59") (pinfunction "AGND_59") (pintype "power_in"))
      (node (ref "U9") (pin "6") (pinfunction "AGND_2_6") (pintype "power_in"))
      (node (ref "U9") (pin "65") (pinfunction "EPAD_65") (pintype "power_in"))
      (node (ref "U9") (pin "7") (pinfunction "DGND_2_7") (pintype "power_in"))
      (node (ref "U9") (pin "8") (pinfunction "TEST0_8") (pintype "input"))
      (node (ref "U9") (pin "9") (pinfunction "TEST1_9") (pintype "input"))
    )
    (net (code "93") (name "GPIO0_24") (class "Default")
      (node (ref "JP3") (pin "27") (pinfunction "27_27") (pintype "passive"))
    )
    (net (code "94") (name "GPIO0_25") (class "Default")
      (node (ref "JP3") (pin "28") (pinfunction "28_28") (pintype "passive"))
    )
    (net (code "95") (name "GPIO0_26") (class "Default")
      (node (ref "JP3") (pin "31") (pinfunction "31_31") (pintype "passive"))
    )
    (net (code "96") (name "GPIO0_27") (class "Default")
      (node (ref "JP3") (pin "32") (pinfunction "32_32") (pintype "passive"))
    )
    (net (code "97") (name "GPIO0_28") (class "Default")
      (node (ref "JP3") (pin "33") (pinfunction "33_33") (pintype "passive"))
    )
    (net (code "98") (name "GPIO0_29") (class "Default")
      (node (ref "JP3") (pin "34") (pinfunction "34_34") (pintype "passive"))
    )
    (net (code "99") (name "GPIO0_30") (class "Default")
      (node (ref "JP3") (pin "35") (pinfunction "35_35") (pintype "passive"))
    )
    (net (code "100") (name "GPIO0_31") (class "Default")
      (node (ref "JP3") (pin "36") (pinfunction "36_36") (pintype "passive"))
    )
    (net (code "101") (name "GPIO0_32") (class "Default")
      (node (ref "JP3") (pin "37") (pinfunction "37_37") (pintype "passive"))
    )
    (net (code "102") (name "GPIO0_33") (class "Default")
      (node (ref "JP3") (pin "38") (pinfunction "38_38") (pintype "passive"))
    )
    (net (code "103") (name "GPIO0_34") (class "Default")
      (node (ref "JP3") (pin "39") (pinfunction "39_39") (pintype "passive"))
    )
    (net (code "104") (name "GPIO0_35") (class "Default")
      (node (ref "JP3") (pin "40") (pinfunction "40_40") (pintype "passive"))
    )
    (net (code "105") (name "GPIO1_16") (class "Default")
      (node (ref "JP2") (pin "19") (pinfunction "19_19") (pintype "passive"))
    )
    (net (code "106") (name "GPIO1_17") (class "Default")
      (node (ref "JP2") (pin "20") (pinfunction "20_20") (pintype "passive"))
    )
    (net (code "107") (name "GPIO1_18") (class "Default")
      (node (ref "JP2") (pin "21") (pinfunction "21_21") (pintype "passive"))
    )
    (net (code "108") (name "GPIO1_19") (class "Default")
      (node (ref "JP2") (pin "22") (pinfunction "22_22") (pintype "passive"))
    )
    (net (code "109") (name "GPIO1_20") (class "Default")
      (node (ref "JP2") (pin "23") (pinfunction "23_23") (pintype "passive"))
    )
    (net (code "110") (name "GPIO1_21") (class "Default")
      (node (ref "JP2") (pin "24") (pinfunction "24_24") (pintype "passive"))
    )
    (net (code "111") (name "GPIO1_22") (class "Default")
      (node (ref "JP2") (pin "25") (pinfunction "25_25") (pintype "passive"))
    )
    (net (code "112") (name "GPIO1_23") (class "Default")
      (node (ref "JP2") (pin "26") (pinfunction "26_26") (pintype "passive"))
    )
    (net (code "113") (name "GPIO1_24") (class "Default")
      (node (ref "JP2") (pin "27") (pinfunction "27_27") (pintype "passive"))
    )
    (net (code "114") (name "GPIO1_25") (class "Default")
      (node (ref "JP2") (pin "28") (pinfunction "28_28") (pintype "passive"))
    )
    (net (code "115") (name "GPIO1_26") (class "Default")
      (node (ref "JP2") (pin "31") (pinfunction "31_31") (pintype "passive"))
    )
    (net (code "116") (name "GPIO1_27") (class "Default")
      (node (ref "JP2") (pin "32") (pinfunction "32_32") (pintype "passive"))
    )
    (net (code "117") (name "GPIO1_28") (class "Default")
      (node (ref "JP2") (pin "33") (pinfunction "33_33") (pintype "passive"))
    )
    (net (code "118") (name "GPIO1_30") (class "Default")
      (node (ref "JP2") (pin "35") (pinfunction "35_35") (pintype "passive"))
    )
    (net (code "119") (name "GPIO1_31") (class "Default")
      (node (ref "JP2") (pin "36") (pinfunction "36_36") (pintype "passive"))
    )
    (net (code "120") (name "GPIO1_32") (class "Default")
      (node (ref "JP2") (pin "37") (pinfunction "37_37") (pintype "passive"))
    )
    (net (code "121") (name "GPIO1_33") (class "Default")
      (node (ref "JP2") (pin "38") (pinfunction "38_38") (pintype "passive"))
    )
    (net (code "122") (name "GPIO1_34") (class "Default")
      (node (ref "JP2") (pin "39") (pinfunction "39_39") (pintype "passive"))
    )
    (net (code "123") (name "GPIO1_35") (class "Default")
      (node (ref "JP2") (pin "40") (pinfunction "40_40") (pintype "passive"))
    )
    (net (code "124") (name "GPIO4") (class "Default")
      (node (ref "JP1") (pin "7") (pinfunction "7_7") (pintype "passive"))
      (node (ref "R139") (pin "1") (pinfunction "1_1") (pintype "passive"))
    )
    (net (code "125") (name "GPIO9") (class "Default")
      (node (ref "JP1") (pin "21") (pinfunction "21_21") (pintype "passive"))
    )
    (net (code "126") (name "GPIO10") (class "Default")
      (node (ref "JP1") (pin "19") (pinfunction "19_19") (pintype "passive"))
    )
    (net (code "127") (name "GPIO17") (class "Default")
      (node (ref "JP1") (pin "11") (pinfunction "11_11") (pintype "passive"))
      (node (ref "R140") (pin "1") (pinfunction "1_1") (pintype "passive"))
    )
    (net (code "128") (name "GPIO22") (class "Default")
      (node (ref "JP1") (pin "15") (pinfunction "15_15") (pintype "passive"))
      (node (ref "R142") (pin "1") (pinfunction "1_1") (pintype "passive"))
    )
    (net (code "129") (name "GPIO27") (class "Default")
      (node (ref "JP1") (pin "13") (pinfunction "13_13") (pintype "passive"))
      (node (ref "R141") (pin "1") (pinfunction "1_1") (pintype "passive"))
    )
    (net (code "130") (name "INPUT1+") (class "Default")
      (node (ref "JP4") (pin "1") (pinfunction "1_1") (pintype "passive"))
      (node (ref "R1") (pin "2") (pinfunction "2_2") (pintype "passive"))
    )
    (net (code "131") (name "INPUT1-") (class "Default")
      (node (ref "JP4") (pin "2") (pinfunction "2_2") (pintype "passive"))
      (node (ref "R4") (pin "2") (pinfunction "2_2") (pintype "passive"))
    )
    (net (code "132") (name "INPUT2+") (class "Default")
      (node (ref "JP4") (pin "3") (pinfunction "3_3") (pintype "passive"))
      (node (ref "R7") (pin "2") (pinfunction "2_2") (pintype "passive"))
    )
    (net (code "133") (name "INPUT2-") (class "Default")
      (node (ref "JP4") (pin "4") (pinfunction "4_4") (pintype "passive"))
      (node (ref "R10") (pin "2") (pinfunction "2_2") (pintype "passive"))
    )
    (net (code "134") (name "INPUT3+") (class "Default")
      (node (ref "JP4") (pin "5") (pinfunction "5_5") (pintype "passive"))
      (node (ref "R13") (pin "2") (pinfunction "2_2") (pintype "passive"))
    )
    (net (code "135") (name "INPUT3-") (class "Default")
      (node (ref "JP4") (pin "6") (pinfunction "6_6") (pintype "passive"))
      (node (ref "R16") (pin "2") (pinfunction "2_2") (pintype "passive"))
    )
    (net (code "136") (name "INPUT4+") (class "Default")
      (node (ref "JP4") (pin "7") (pinfunction "7_7") (pintype "passive"))
      (node (ref "R19") (pin "2") (pinfunction "2_2") (pintype "passive"))
    )
    (net (code "137") (name "INPUT4-") (class "Default")
      (node (ref "JP4") (pin "8") (pinfunction "8_8") (pintype "passive"))
      (node (ref "R22") (pin "2") (pinfunction "2_2") (pintype "passive"))
    )
    (net (code "138") (name "INPUT5+") (class "Default")
      (node (ref "JP4") (pin "9") (pinfunction "9_9") (pintype "passive"))
      (node (ref "R25") (pin "2") (pinfunction "2_2") (pintype "passive"))
    )
    (net (code "139") (name "INPUT5-") (class "Default")
      (node (ref "JP4") (pin "10") (pinfunction "10_10") (pintype "passive"))
      (node (ref "R28") (pin "2") (pinfunction "2_2") (pintype "passive"))
    )
    (net (code "140") (name "INPUT6+") (class "Default")
      (node (ref "JP4") (pin "11") (pinfunction "11_11") (pintype "passive"))
      (node (ref "R31") (pin "2") (pinfunction "2_2") (pintype "passive"))
    )
    (net (code "141") (name "INPUT6-") (class "Default")
      (node (ref "JP4") (pin "12") (pinfunction "12_12") (pintype "passive"))
      (node (ref "R34") (pin "2") (pinfunction "2_2") (pintype "passive"))
    )
    (net (code "142") (name "INPUT7+") (class "Default")
      (node (ref "JP4") (pin "13") (pinfunction "13_13") (pintype "passive"))
      (node (ref "R37") (pin "2") (pinfunction "2_2") (pintype "passive"))
    )
    (net (code "143") (name "INPUT7-") (class "Default")
      (node (ref "JP4") (pin "14") (pinfunction "14_14") (pintype "passive"))
      (node (ref "R40") (pin "2") (pinfunction "2_2") (pintype "passive"))
    )
    (net (code "144") (name "INPUT8+") (class "Default")
      (node (ref "JP4") (pin "15") (pinfunction "15_15") (pintype "passive"))
      (node (ref "R43") (pin "2") (pinfunction "2_2") (pintype "passive"))
    )
    (net (code "145") (name "INPUT8-") (class "Default")
      (node (ref "JP4") (pin "16") (pinfunction "16_16") (pintype "passive"))
      (node (ref "R46") (pin "2") (pinfunction "2_2") (pintype "passive"))
    )
    (net (code "146") (name "INPUT9+") (class "Default")
      (node (ref "JP4") (pin "31") (pinfunction "31_31") (pintype "passive"))
      (node (ref "R55") (pin "2") (pinfunction "2_2") (pintype "passive"))
    )
    (net (code "147") (name "INPUT9-") (class "Default")
      (node (ref "JP4") (pin "32") (pinfunction "32_32") (pintype "passive"))
      (node (ref "R58") (pin "2") (pinfunction "2_2") (pintype "passive"))
    )
    (net (code "148") (name "INPUT10+") (class "Default")
      (node (ref "JP4") (pin "29") (pinfunction "29_29") (pintype "passive"))
      (node (ref "R61") (pin "2") (pinfunction "2_2") (pintype "passive"))
    )
    (net (code "149") (name "INPUT10-") (class "Default")
      (node (ref "JP4") (pin "30") (pinfunction "30_30") (pintype "passive"))
      (node (ref "R64") (pin "2") (pinfunction "2_2") (pintype "passive"))
    )
    (net (code "150") (name "INPUT11+") (class "Default")
      (node (ref "JP4") (pin "27") (pinfunction "27_27") (pintype "passive"))
      (node (ref "R67") (pin "2") (pinfunction "2_2") (pintype "passive"))
    )
    (net (code "151") (name "INPUT11-") (class "Default")
      (node (ref "JP4") (pin "28") (pinfunction "28_28") (pintype "passive"))
      (node (ref "R70") (pin "2") (pinfunction "2_2") (pintype "passive"))
    )
    (net (code "152") (name "INPUT12+") (class "Default")
      (node (ref "JP4") (pin "25") (pinfunction "25_25") (pintype "passive"))
      (node (ref "R73") (pin "2") (pinfunction "2_2") (pintype "passive"))
    )
    (net (code "153") (name "INPUT12-") (class "Default")
      (node (ref "JP4") (pin "26") (pinfunction "26_26") (pintype "passive"))
      (node (ref "R76") (pin "2") (pinfunction "2_2") (pintype "passive"))
    )
    (net (code "154") (name "INPUT13+") (class "Default")
      (node (ref "JP4") (pin "23") (pinfunction "23_23") (pintype "passive"))
      (node (ref "R79") (pin "2") (pinfunction "2_2") (pintype "passive"))
    )
    (net (code "155") (name "INPUT13-") (class "Default")
      (node (ref "JP4") (pin "24") (pinfunction "24_24") (pintype "passive"))
      (node (ref "R82") (pin "2") (pinfunction "2_2") (pintype "passive"))
    )
    (net (code "156") (name "INPUT14+") (class "Default")
      (node (ref "JP4") (pin "21") (pinfunction "21_21") (pintype "passive"))
      (node (ref "R85") (pin "2") (pinfunction "2_2") (pintype "passive"))
    )
    (net (code "157") (name "INPUT14-") (class "Default")
      (node (ref "JP4") (pin "22") (pinfunction "22_22") (pintype "passive"))
      (node (ref "R88") (pin "2") (pinfunction "2_2") (pintype "passive"))
    )
    (net (code "158") (name "INPUT15+") (class "Default")
      (node (ref "JP4") (pin "19") (pinfunction "19_19") (pintype "passive"))
      (node (ref "R91") (pin "2") (pinfunction "2_2") (pintype "passive"))
    )
    (net (code "159") (name "INPUT15-") (class "Default")
      (node (ref "JP4") (pin "20") (pinfunction "20_20") (pintype "passive"))
      (node (ref "R94") (pin "2") (pinfunction "2_2") (pintype "passive"))
    )
    (net (code "160") (name "INPUT16+") (class "Default")
      (node (ref "JP4") (pin "17") (pinfunction "17_17") (pintype "passive"))
      (node (ref "R97") (pin "2") (pinfunction "2_2") (pintype "passive"))
    )
    (net (code "161") (name "INPUT16-") (class "Default")
      (node (ref "JP4") (pin "18") (pinfunction "18_18") (pintype "passive"))
      (node (ref "R100") (pin "2") (pinfunction "2_2") (pintype "passive"))
    )
    (net (code "162") (name "INPUT17+") (class "Default")
      (node (ref "IC31") (pin "1") (pinfunction "OUT_1") (pintype "bidirectional"))
      (node (ref "R109") (pin "2") (pinfunction "2_2") (pintype "passive"))
      (node (ref "R49") (pin "2") (pinfunction "2_2") (pintype "passive"))
    )
    (net (code "163") (name "INPUT18+") (class "Default")
      (node (ref "IC32") (pin "1") (pinfunction "OUT_1") (pintype "bidirectional"))
      (node (ref "R103") (pin "2") (pinfunction "2_2") (pintype "passive"))
      (node (ref "R115") (pin "2") (pinfunction "2_2") (pintype "passive"))
    )
    (net (code "164") (name "INPUT19+") (class "Default")
      (node (ref "IC33") (pin "1") (pinfunction "OUT_1") (pintype "bidirectional"))
      (node (ref "R121") (pin "2") (pinfunction "2_2") (pintype "passive"))
      (node (ref "R133") (pin "2") (pinfunction "2_2") (pintype "passive"))
    )
    (net (code "165") (name "INPUT20+") (class "Default")
      (node (ref "IC34") (pin "1") (pinfunction "OUT_1") (pintype "bidirectional"))
      (node (ref "R127") (pin "2") (pinfunction "2_2") (pintype "passive"))
      (node (ref "R137") (pin "2") (pinfunction "2_2") (pintype "passive"))
    )
    (net (code "166") (name "LAZO1") (class "Default")
      (node (ref "IC35") (pin "4") (pinfunction "COLLECTOR_4") (pintype "bidirectional"))
      (node (ref "JP2") (pin "2") (pinfunction "2_2") (pintype "passive"))
      (node (ref "R148") (pin "1") (pinfunction "1_1") (pintype "passive"))
    )
    (net (code "167") (name "LAZO2") (class "Default")
      (node (ref "IC36") (pin "4") (pinfunction "COLLECTOR_4") (pintype "bidirectional"))
      (node (ref "JP2") (pin "1") (pinfunction "1_1") (pintype "passive"))
      (node (ref "R150") (pin "1") (pinfunction "1_1") (pintype "passive"))
    )
    (net (code "168") (name "LAZO3") (class "Default")
      (node (ref "IC37") (pin "4") (pinfunction "COLLECTOR_4") (pintype "bidirectional"))
      (node (ref "JP2") (pin "4") (pinfunction "4_4") (pintype "passive"))
      (node (ref "R152") (pin "1") (pinfunction "1_1") (pintype "passive"))
    )
    (net (code "169") (name "LAZO4") (class "Default")
      (node (ref "IC38") (pin "4") (pinfunction "COLLECTOR_4") (pintype "bidirectional"))
      (node (ref "JP2") (pin "3") (pinfunction "3_3") (pintype "passive"))
      (node (ref "R154") (pin "1") (pinfunction "1_1") (pintype "passive"))
    )
    (net (code "170") (name "LAZO5") (class "Default")
      (node (ref "IC39") (pin "4") (pinfunction "COLLECTOR_4") (pintype "bidirectional"))
      (node (ref "JP2") (pin "6") (pinfunction "6_6") (pintype "passive"))
      (node (ref "R156") (pin "1") (pinfunction "1_1") (pintype "passive"))
    )
    (net (code "171") (name "LAZO6") (class "Default")
      (node (ref "IC40") (pin "4") (pinfunction "COLLECTOR_4") (pintype "bidirectional"))
      (node (ref "JP2") (pin "5") (pinfunction "5_5") (pintype "passive"))
      (node (ref "R158") (pin "1") (pinfunction "1_1") (pintype "passive"))
    )
    (net (code "172") (name "LAZO7") (class "Default")
      (node (ref "IC41") (pin "4") (pinfunction "COLLECTOR_4") (pintype "bidirectional"))
      (node (ref "JP2") (pin "8") (pinfunction "8_8") (pintype "passive"))
      (node (ref "R160") (pin "1") (pinfunction "1_1") (pintype "passive"))
    )
    (net (code "173") (name "LAZO8") (class "Default")
      (node (ref "IC42") (pin "4") (pinfunction "COLLECTOR_4") (pintype "bidirectional"))
      (node (ref "JP2") (pin "7") (pinfunction "7_7") (pintype "passive"))
      (node (ref "R162") (pin "1") (pinfunction "1_1") (pintype "passive"))
    )
    (net (code "174") (name "LAZO_8") (class "Default")
      (node (ref "JP2") (pin "34") (pinfunction "34_34") (pintype "passive"))
    )
    (net (code "175") (name "LOOP1") (class "Default")
      (node (ref "IC35") (pin "2") (pinfunction "CATHODE_2") (pintype "bidirectional"))
      (node (ref "J3") (pin "1") (pinfunction "1_1") (pintype "bidirectional"))
    )
    (net (code "176") (name "LOOP2") (class "Default")
      (node (ref "IC36") (pin "2") (pinfunction "CATHODE_2") (pintype "bidirectional"))
      (node (ref "J3") (pin "2") (pinfunction "2_2") (pintype "bidirectional"))
    )
    (net (code "177") (name "LOOP3") (class "Default")
      (node (ref "IC37") (pin "2") (pinfunction "CATHODE_2") (pintype "bidirectional"))
      (node (ref "J3") (pin "3") (pinfunction "3_3") (pintype "bidirectional"))
    )
    (net (code "178") (name "LOOP4") (class "Default")
      (node (ref "IC38") (pin "2") (pinfunction "CATHODE_2") (pintype "bidirectional"))
      (node (ref "J3") (pin "4") (pinfunction "4_4") (pintype "bidirectional"))
    )
    (net (code "179") (name "LOOP5") (class "Default")
      (node (ref "IC39") (pin "2") (pinfunction "CATHODE_2") (pintype "bidirectional"))
      (node (ref "J3") (pin "5") (pinfunction "5_5") (pintype "bidirectional"))
    )
    (net (code "180") (name "LOOP6") (class "Default")
      (node (ref "IC40") (pin "2") (pinfunction "CATHODE_2") (pintype "bidirectional"))
      (node (ref "J3") (pin "6") (pinfunction "6_6") (pintype "bidirectional"))
    )
    (net (code "181") (name "LOOP7") (class "Default")
      (node (ref "IC41") (pin "2") (pinfunction "CATHODE_2") (pintype "bidirectional"))
      (node (ref "J3") (pin "7") (pinfunction "7_7") (pintype "bidirectional"))
    )
    (net (code "182") (name "LOOP8") (class "Default")
      (node (ref "IC42") (pin "2") (pinfunction "CATHODE_2") (pintype "bidirectional"))
      (node (ref "J3") (pin "8") (pinfunction "8_8") (pintype "bidirectional"))
    )
    (net (code "183") (name "Net-(IC31-IN-)") (class "Default")
      (node (ref "IC31") (pin "4") (pinfunction "IN-_4") (pintype "bidirectional"))
      (node (ref "R49") (pin "1") (pinfunction "1_1") (pintype "passive"))
      (node (ref "R53") (pin "2") (pinfunction "2_2") (pintype "passive"))
    )
    (net (code "184") (name "Net-(IC32-IN-)") (class "Default")
      (node (ref "IC32") (pin "4") (pinfunction "IN-_4") (pintype "bidirectional"))
      (node (ref "R103") (pin "1") (pinfunction "1_1") (pintype "passive"))
      (node (ref "R107") (pin "2") (pinfunction "2_2") (pintype "passive"))
    )
    (net (code "185") (name "Net-(IC33-IN-)") (class "Default")
      (node (ref "IC33") (pin "4") (pinfunction "IN-_4") (pintype "bidirectional"))
      (node (ref "R133") (pin "1") (pinfunction "1_1") (pintype "passive"))
      (node (ref "R165") (pin "2") (pinfunction "2_2") (pintype "passive"))
    )
    (net (code "186") (name "Net-(IC34-IN-)") (class "Default")
      (node (ref "IC34") (pin "4") (pinfunction "IN-_4") (pintype "bidirectional"))
      (node (ref "R137") (pin "1") (pinfunction "1_1") (pintype "passive"))
      (node (ref "R164") (pin "2") (pinfunction "2_2") (pintype "passive"))
    )
    (net (code "187") (name "Net-(IC35-ANODE)") (class "Default")
      (node (ref "IC35") (pin "1") (pinfunction "ANODE_1") (pintype "bidirectional"))
      (node (ref "R147") (pin "2") (pinfunction "2_2") (pintype "passive"))
    )
    (net (code "188") (name "Net-(IC36-ANODE)") (class "Default")
      (node (ref "IC36") (pin "1") (pinfunction "ANODE_1") (pintype "bidirectional"))
      (node (ref "R149") (pin "2") (pinfunction "2_2") (pintype "passive"))
    )
    (net (code "189") (name "Net-(IC37-ANODE)") (class "Default")
      (node (ref "IC37") (pin "1") (pinfunction "ANODE_1") (pintype "bidirectional"))
      (node (ref "R151") (pin "2") (pinfunction "2_2") (pintype "passive"))
    )
    (net (code "190") (name "Net-(IC38-ANODE)") (class "Default")
      (node (ref "IC38") (pin "1") (pinfunction "ANODE_1") (pintype "bidirectional"))
      (node (ref "R153") (pin "2") (pinfunction "2_2") (pintype "passive"))
    )
    (net (code "191") (name "Net-(IC39-ANODE)") (class "Default")
      (node (ref "IC39") (pin "1") (pinfunction "ANODE_1") (pintype "bidirectional"))
      (node (ref "R155") (pin "2") (pinfunction "2_2") (pintype "passive"))
    )
    (net (code "192") (name "Net-(IC40-ANODE)") (class "Default")
      (node (ref "IC40") (pin "1") (pinfunction "ANODE_1") (pintype "bidirectional"))
      (node (ref "R157") (pin "2") (pinfunction "2_2") (pintype "passive"))
    )
    (net (code "193") (name "Net-(IC41-ANODE)") (class "Default")
      (node (ref "IC41") (pin "1") (pinfunction "ANODE_1") (pintype "bidirectional"))
      (node (ref "R159") (pin "2") (pinfunction "2_2") (pintype "passive"))
    )
    (net (code "194") (name "Net-(IC42-ANODE)") (class "Default")
      (node (ref "IC42") (pin "1") (pinfunction "ANODE_1") (pintype "bidirectional"))
      (node (ref "R161") (pin "2") (pinfunction "2_2") (pintype "passive"))
    )
    (net (code "195") (name "Net-(JP6-Pad1)") (class "Default")
      (node (ref "JP6") (pin "1") (pinfunction "1_1") (pintype "passive"))
      (node (ref "R139") (pin "2") (pinfunction "2_2") (pintype "passive"))
    )
    (net (code "196") (name "Net-(JP6-Pad3)") (class "Default")
      (node (ref "JP6") (pin "3") (pinfunction "3_3") (pintype "passive"))
      (node (ref "R140") (pin "2") (pinfunction "2_2") (pintype "passive"))
    )
    (net (code "197") (name "Net-(JP6-Pad5)") (class "Default")
      (node (ref "JP6") (pin "5") (pinfunction "5_5") (pintype "passive"))
      (node (ref "R141") (pin "2") (pinfunction "2_2") (pintype "passive"))
    )
    (net (code "198") (name "Net-(JP6-Pad7)") (class "Default")
      (node (ref "JP6") (pin "7") (pinfunction "7_7") (pintype "passive"))
      (node (ref "R142") (pin "2") (pinfunction "2_2") (pintype "passive"))
    )
    (net (code "199") (name "Net-(JP6-Pad9)") (class "Default")
      (node (ref "JP6") (pin "9") (pinfunction "9_9") (pintype "passive"))
      (node (ref "R163") (pin "2") (pinfunction "2_2") (pintype "passive"))
    )
    (net (code "200") (name "Net-(U1-IN+)") (class "Default")
      (node (ref "C34") (pin "1") (pinfunction "1_1") (pintype "passive"))
      (node (ref "R50") (pin "2") (pinfunction "2_2") (pintype "passive"))
      (node (ref "U1") (pin "3") (pinfunction "IN+_3") (pintype "input"))
    )
    (net (code "201") (name "Net-(U1-IN-)") (class "Default")
      (node (ref "C35") (pin "1") (pinfunction "1_1") (pintype "passive"))
      (node (ref "R52") (pin "1") (pinfunction "1_1") (pintype "passive"))
      (node (ref "U1") (pin "2") (pinfunction "IN-_2") (pintype "input"))
    )
    (net (code "202") (name "Net-(U1-OUTPUT)") (class "Default")
      (node (ref "C35") (pin "2") (pinfunction "2_2") (pintype "passive"))
      (node (ref "R51") (pin "1") (pinfunction "1_1") (pintype "passive"))
      (node (ref "U1") (pin "6") (pinfunction "OUTPUT_6") (pintype "output"))
    )
    (net (code "203") (name "Net-(U2-IN-)") (class "Default")
      (node (ref "R54") (pin "1") (pinfunction "1_1") (pintype "passive"))
      (node (ref "U2") (pin "2") (pinfunction "IN-_2") (pintype "input"))
      (node (ref "U2") (pin "6") (pinfunction "OUTPUT_6") (pintype "output"))
    )
    (net (code "204") (name "Net-(U3-TRIM{slash}NR)") (class "Default")
      (node (ref "C115") (pin "1") (pinfunction "1_1") (pintype "passive"))
      (node (ref "U3") (pin "5") (pinfunction "TRIM/NR_5") (pintype "passive"))
    )
    (net (code "205") (name "Net-(U3-VOUT)") (class "Default")
      (node (ref "C33") (pin "1") (pinfunction "1_1") (pintype "passive"))
      (node (ref "R50") (pin "1") (pinfunction "1_1") (pintype "passive"))
      (node (ref "U3") (pin "6") (pinfunction "VOUT_6") (pintype "output"))
    )
    (net (code "206") (name "Net-(U4-IN+)") (class "Default")
      (node (ref "C75") (pin "1") (pinfunction "1_1") (pintype "passive"))
      (node (ref "R104") (pin "2") (pinfunction "2_2") (pintype "passive"))
      (node (ref "U4") (pin "3") (pinfunction "IN+_3") (pintype "input"))
    )
    (net (code "207") (name "Net-(U4-IN-)") (class "Default")
      (node (ref "C76") (pin "1") (pinfunction "1_1") (pintype "passive"))
      (node (ref "R106") (pin "1") (pinfunction "1_1") (pintype "passive"))
      (node (ref "U4") (pin "2") (pinfunction "IN-_2") (pintype "input"))
    )
    (net (code "208") (name "Net-(U4-OUTPUT)") (class "Default")
      (node (ref "C76") (pin "2") (pinfunction "2_2") (pintype "passive"))
      (node (ref "R105") (pin "1") (pinfunction "1_1") (pintype "passive"))
      (node (ref "U4") (pin "6") (pinfunction "OUTPUT_6") (pintype "output"))
    )
    (net (code "209") (name "Net-(U5-IN-)") (class "Default")
      (node (ref "R108") (pin "1") (pinfunction "1_1") (pintype "passive"))
      (node (ref "U5") (pin "2") (pinfunction "IN-_2") (pintype "input"))
      (node (ref "U5") (pin "6") (pinfunction "OUTPUT_6") (pintype "output"))
    )
    (net (code "210") (name "Net-(U7-IN+)") (class "Default")
      (node (ref "C100") (pin "1") (pinfunction "1_1") (pintype "passive"))
      (node (ref "R134") (pin "2") (pinfunction "2_2") (pintype "passive"))
      (node (ref "U7") (pin "3") (pinfunction "IN+_3") (pintype "input"))
    )
    (net (code "211") (name "Net-(U7-IN-)") (class "Default")
      (node (ref "C101") (pin "1") (pinfunction "1_1") (pintype "passive"))
      (node (ref "R136") (pin "1") (pinfunction "1_1") (pintype "passive"))
      (node (ref "U7") (pin "2") (pinfunction "IN-_2") (pintype "input"))
    )
    (net (code "212") (name "Net-(U7-OUTPUT)") (class "Default")
      (node (ref "C101") (pin "2") (pinfunction "2_2") (pintype "passive"))
      (node (ref "R135") (pin "1") (pinfunction "1_1") (pintype "passive"))
      (node (ref "U7") (pin "6") (pinfunction "OUTPUT_6") (pintype "output"))
    )
    (net (code "213") (name "Net-(U8-IN-)") (class "Default")
      (node (ref "R138") (pin "1") (pinfunction "1_1") (pintype "passive"))
      (node (ref "U8") (pin "2") (pinfunction "IN-_2") (pintype "input"))
      (node (ref "U8") (pin "6") (pinfunction "OUTPUT_6") (pintype "output"))
    )
    (net (code "214") (name "Net-(U12-TRIM{slash}NR)") (class "Default")
      (node (ref "C116") (pin "1") (pinfunction "1_1") (pintype "passive"))
      (node (ref "U12") (pin "5") (pinfunction "TRIM/NR_5") (pintype "passive"))
    )
    (net (code "215") (name "Net-(U12-VOUT)") (class "Default")
      (node (ref "C99") (pin "1") (pinfunction "1_1") (pintype "passive"))
      (node (ref "R134") (pin "1") (pinfunction "1_1") (pintype "passive"))
      (node (ref "U12") (pin "6") (pinfunction "VOUT_6") (pintype "output"))
    )
    (net (code "216") (name "Net-(U13-TRIM{slash}NR)") (class "Default")
      (node (ref "C118") (pin "1") (pinfunction "1_1") (pintype "passive"))
      (node (ref "U13") (pin "5") (pinfunction "TRIM/NR_5") (pintype "passive"))
    )
    (net (code "217") (name "Net-(U13-VOUT)") (class "Default")
      (node (ref "C74") (pin "1") (pinfunction "1_1") (pintype "passive"))
      (node (ref "R104") (pin "1") (pinfunction "1_1") (pintype "passive"))
      (node (ref "U13") (pin "6") (pinfunction "VOUT_6") (pintype "output"))
    )
    (net (code "218") (name "Net-(U14-VIN+)") (class "Default")
      (node (ref "C1") (pin "1") (pinfunction "1_1") (pintype "passive"))
      (node (ref "R1") (pin "1") (pinfunction "1_1") (pintype "passive"))
      (node (ref "R2") (pin "2") (pinfunction "2_2") (pintype "passive"))
      (node (ref "U14") (pin "8") (pinfunction "VIN+_8") (pintype "input"))
    )
    (net (code "219") (name "Net-(U14-VIN-)") (class "Default")
      (node (ref "C4") (pin "1") (pinfunction "1_1") (pintype "passive"))
      (node (ref "R4") (pin "1") (pinfunction "1_1") (pintype "passive"))
      (node (ref "R5") (pin "2") (pinfunction "2_2") (pintype "passive"))
      (node (ref "U14") (pin "1") (pinfunction "VIN-_1") (pintype "input"))
    )
    (net (code "220") (name "Net-(U14-VOUT+)") (class "Default")
      (node (ref "C4") (pin "2") (pinfunction "2_2") (pintype "passive"))
      (node (ref "R6") (pin "2") (pinfunction "2_2") (pintype "passive"))
      (node (ref "U14") (pin "4") (pinfunction "VOUT+_4") (pintype "output"))
    )
    (net (code "221") (name "Net-(U14-VOUT-)") (class "Default")
      (node (ref "C1") (pin "2") (pinfunction "2_2") (pintype "passive"))
      (node (ref "R3") (pin "2") (pinfunction "2_2") (pintype "passive"))
      (node (ref "U14") (pin "5") (pinfunction "VOUT-_5") (pintype "output"))
    )
    (net (code "222") (name "Net-(U15-VIN+)") (class "Default")
      (node (ref "C5") (pin "1") (pinfunction "1_1") (pintype "passive"))
      (node (ref "R7") (pin "1") (pinfunction "1_1") (pintype "passive"))
      (node (ref "R8") (pin "2") (pinfunction "2_2") (pintype "passive"))
      (node (ref "U15") (pin "8") (pinfunction "VIN+_8") (pintype "input"))
    )
    (net (code "223") (name "Net-(U15-VIN-)") (class "Default")
      (node (ref "C8") (pin "1") (pinfunction "1_1") (pintype "passive"))
      (node (ref "R10") (pin "1") (pinfunction "1_1") (pintype "passive"))
      (node (ref "R11") (pin "2") (pinfunction "2_2") (pintype "passive"))
      (node (ref "U15") (pin "1") (pinfunction "VIN-_1") (pintype "input"))
    )
    (net (code "224") (name "Net-(U15-VOUT+)") (class "Default")
      (node (ref "C8") (pin "2") (pinfunction "2_2") (pintype "passive"))
      (node (ref "R12") (pin "2") (pinfunction "2_2") (pintype "passive"))
      (node (ref "U15") (pin "4") (pinfunction "VOUT+_4") (pintype "output"))
    )
    (net (code "225") (name "Net-(U15-VOUT-)") (class "Default")
      (node (ref "C5") (pin "2") (pinfunction "2_2") (pintype "passive"))
      (node (ref "R9") (pin "2") (pinfunction "2_2") (pintype "passive"))
      (node (ref "U15") (pin "5") (pinfunction "VOUT-_5") (pintype "output"))
    )
    (net (code "226") (name "Net-(U16-VIN+)") (class "Default")
      (node (ref "C9") (pin "1") (pinfunction "1_1") (pintype "passive"))
      (node (ref "R13") (pin "1") (pinfunction "1_1") (pintype "passive"))
      (node (ref "R14") (pin "2") (pinfunction "2_2") (pintype "passive"))
      (node (ref "U16") (pin "8") (pinfunction "VIN+_8") (pintype "input"))
    )
    (net (code "227") (name "Net-(U16-VIN-)") (class "Default")
      (node (ref "C12") (pin "1") (pinfunction "1_1") (pintype "passive"))
      (node (ref "R16") (pin "1") (pinfunction "1_1") (pintype "passive"))
      (node (ref "R17") (pin "2") (pinfunction "2_2") (pintype "passive"))
      (node (ref "U16") (pin "1") (pinfunction "VIN-_1") (pintype "input"))
    )
    (net (code "228") (name "Net-(U16-VOUT+)") (class "Default")
      (node (ref "C12") (pin "2") (pinfunction "2_2") (pintype "passive"))
      (node (ref "R18") (pin "2") (pinfunction "2_2") (pintype "passive"))
      (node (ref "U16") (pin "4") (pinfunction "VOUT+_4") (pintype "output"))
    )
    (net (code "229") (name "Net-(U16-VOUT-)") (class "Default")
      (node (ref "C9") (pin "2") (pinfunction "2_2") (pintype "passive"))
      (node (ref "R15") (pin "2") (pinfunction "2_2") (pintype "passive"))
      (node (ref "U16") (pin "5") (pinfunction "VOUT-_5") (pintype "output"))
    )
    (net (code "230") (name "Net-(U17-VIN+)") (class "Default")
      (node (ref "C13") (pin "1") (pinfunction "1_1") (pintype "passive"))
      (node (ref "R19") (pin "1") (pinfunction "1_1") (pintype "passive"))
      (node (ref "R20") (pin "2") (pinfunction "2_2") (pintype "passive"))
      (node (ref "U17") (pin "8") (pinfunction "VIN+_8") (pintype "input"))
    )
    (net (code "231") (name "Net-(U17-VIN-)") (class "Default")
      (node (ref "C16") (pin "1") (pinfunction "1_1") (pintype "passive"))
      (node (ref "R22") (pin "1") (pinfunction "1_1") (pintype "passive"))
      (node (ref "R23") (pin "2") (pinfunction "2_2") (pintype "passive"))
      (node (ref "U17") (pin "1") (pinfunction "VIN-_1") (pintype "input"))
    )
    (net (code "232") (name "Net-(U17-VOUT+)") (class "Default")
      (node (ref "C16") (pin "2") (pinfunction "2_2") (pintype "passive"))
      (node (ref "R24") (pin "2") (pinfunction "2_2") (pintype "passive"))
      (node (ref "U17") (pin "4") (pinfunction "VOUT+_4") (pintype "output"))
    )
    (net (code "233") (name "Net-(U17-VOUT-)") (class "Default")
      (node (ref "C13") (pin "2") (pinfunction "2_2") (pintype "passive"))
      (node (ref "R21") (pin "2") (pinfunction "2_2") (pintype "passive"))
      (node (ref "U17") (pin "5") (pinfunction "VOUT-_5") (pintype "output"))
    )
    (net (code "234") (name "Net-(U18-VIN+)") (class "Default")
      (node (ref "C17") (pin "1") (pinfunction "1_1") (pintype "passive"))
      (node (ref "R25") (pin "1") (pinfunction "1_1") (pintype "passive"))
      (node (ref "R26") (pin "2") (pinfunction "2_2") (pintype "passive"))
      (node (ref "U18") (pin "8") (pinfunction "VIN+_8") (pintype "input"))
    )
    (net (code "235") (name "Net-(U18-VIN-)") (class "Default")
      (node (ref "C20") (pin "1") (pinfunction "1_1") (pintype "passive"))
      (node (ref "R28") (pin "1") (pinfunction "1_1") (pintype "passive"))
      (node (ref "R29") (pin "2") (pinfunction "2_2") (pintype "passive"))
      (node (ref "U18") (pin "1") (pinfunction "VIN-_1") (pintype "input"))
    )
    (net (code "236") (name "Net-(U18-VOUT+)") (class "Default")
      (node (ref "C20") (pin "2") (pinfunction "2_2") (pintype "passive"))
      (node (ref "R30") (pin "2") (pinfunction "2_2") (pintype "passive"))
      (node (ref "U18") (pin "4") (pinfunction "VOUT+_4") (pintype "output"))
    )
    (net (code "237") (name "Net-(U18-VOUT-)") (class "Default")
      (node (ref "C17") (pin "2") (pinfunction "2_2") (pintype "passive"))
      (node (ref "R27") (pin "2") (pinfunction "2_2") (pintype "passive"))
      (node (ref "U18") (pin "5") (pinfunction "VOUT-_5") (pintype "output"))
    )
    (net (code "238") (name "Net-(U19-VIN+)") (class "Default")
      (node (ref "C21") (pin "1") (pinfunction "1_1") (pintype "passive"))
      (node (ref "R31") (pin "1") (pinfunction "1_1") (pintype "passive"))
      (node (ref "R32") (pin "2") (pinfunction "2_2") (pintype "passive"))
      (node (ref "U19") (pin "8") (pinfunction "VIN+_8") (pintype "input"))
    )
    (net (code "239") (name "Net-(U19-VIN-)") (class "Default")
      (node (ref "C24") (pin "1") (pinfunction "1_1") (pintype "passive"))
      (node (ref "R34") (pin "1") (pinfunction "1_1") (pintype "passive"))
      (node (ref "R35") (pin "2") (pinfunction "2_2") (pintype "passive"))
      (node (ref "U19") (pin "1") (pinfunction "VIN-_1") (pintype "input"))
    )
    (net (code "240") (name "Net-(U19-VOUT+)") (class "Default")
      (node (ref "C24") (pin "2") (pinfunction "2_2") (pintype "passive"))
      (node (ref "R36") (pin "2") (pinfunction "2_2") (pintype "passive"))
      (node (ref "U19") (pin "4") (pinfunction "VOUT+_4") (pintype "output"))
    )
    (net (code "241") (name "Net-(U19-VOUT-)") (class "Default")
      (node (ref "C21") (pin "2") (pinfunction "2_2") (pintype "passive"))
      (node (ref "R33") (pin "2") (pinfunction "2_2") (pintype "passive"))
      (node (ref "U19") (pin "5") (pinfunction "VOUT-_5") (pintype "output"))
    )
    (net (code "242") (name "Net-(U20-VIN+)") (class "Default")
      (node (ref "C25") (pin "1") (pinfunction "1_1") (pintype "passive"))
      (node (ref "R37") (pin "1") (pinfunction "1_1") (pintype "passive"))
      (node (ref "R38") (pin "2") (pinfunction "2_2") (pintype "passive"))
      (node (ref "U20") (pin "8") (pinfunction "VIN+_8") (pintype "input"))
    )
    (net (code "243") (name "Net-(U20-VIN-)") (class "Default")
      (node (ref "C28") (pin "1") (pinfunction "1_1") (pintype "passive"))
      (node (ref "R40") (pin "1") (pinfunction "1_1") (pintype "passive"))
      (node (ref "R41") (pin "2") (pinfunction "2_2") (pintype "passive"))
      (node (ref "U20") (pin "1") (pinfunction "VIN-_1") (pintype "input"))
    )
    (net (code "244") (name "Net-(U20-VOUT+)") (class "Default")
      (node (ref "C28") (pin "2") (pinfunction "2_2") (pintype "passive"))
      (node (ref "R42") (pin "2") (pinfunction "2_2") (pintype "passive"))
      (node (ref "U20") (pin "4") (pinfunction "VOUT+_4") (pintype "output"))
    )
    (net (code "245") (name "Net-(U20-VOUT-)") (class "Default")
      (node (ref "C25") (pin "2") (pinfunction "2_2") (pintype "passive"))
      (node (ref "R39") (pin "2") (pinfunction "2_2") (pintype "passive"))
      (node (ref "U20") (pin "5") (pinfunction "VOUT-_5") (pintype "output"))
    )
    (net (code "246") (name "Net-(U21-VIN+)") (class "Default")
      (node (ref "C29") (pin "1") (pinfunction "1_1") (pintype "passive"))
      (node (ref "R43") (pin "1") (pinfunction "1_1") (pintype "passive"))
      (node (ref "R44") (pin "2") (pinfunction "2_2") (pintype "passive"))
      (node (ref "U21") (pin "8") (pinfunction "VIN+_8") (pintype "input"))
    )
    (net (code "247") (name "Net-(U21-VIN-)") (class "Default")
      (node (ref "C32") (pin "1") (pinfunction "1_1") (pintype "passive"))
      (node (ref "R46") (pin "1") (pinfunction "1_1") (pintype "passive"))
      (node (ref "R47") (pin "2") (pinfunction "2_2") (pintype "passive"))
      (node (ref "U21") (pin "1") (pinfunction "VIN-_1") (pintype "input"))
    )
    (net (code "248") (name "Net-(U21-VOUT+)") (class "Default")
      (node (ref "C32") (pin "2") (pinfunction "2_2") (pintype "passive"))
      (node (ref "R48") (pin "2") (pinfunction "2_2") (pintype "passive"))
      (node (ref "U21") (pin "4") (pinfunction "VOUT+_4") (pintype "output"))
    )
    (net (code "249") (name "Net-(U21-VOUT-)") (class "Default")
      (node (ref "C29") (pin "2") (pinfunction "2_2") (pintype "passive"))
      (node (ref "R45") (pin "2") (pinfunction "2_2") (pintype "passive"))
      (node (ref "U21") (pin "5") (pinfunction "VOUT-_5") (pintype "output"))
    )
    (net (code "250") (name "Net-(U22-VIN+)") (class "Default")
      (node (ref "C42") (pin "1") (pinfunction "1_1") (pintype "passive"))
      (node (ref "R55") (pin "1") (pinfunction "1_1") (pintype "passive"))
      (node (ref "R56") (pin "2") (pinfunction "2_2") (pintype "passive"))
      (node (ref "U22") (pin "8") (pinfunction "VIN+_8") (pintype "input"))
    )
    (net (code "251") (name "Net-(U22-VIN-)") (class "Default")
      (node (ref "C45") (pin "1") (pinfunction "1_1") (pintype "passive"))
      (node (ref "R58") (pin "1") (pinfunction "1_1") (pintype "passive"))
      (node (ref "R59") (pin "2") (pinfunction "2_2") (pintype "passive"))
      (node (ref "U22") (pin "1") (pinfunction "VIN-_1") (pintype "input"))
    )
    (net (code "252") (name "Net-(U22-VOUT+)") (class "Default")
      (node (ref "C45") (pin "2") (pinfunction "2_2") (pintype "passive"))
      (node (ref "R60") (pin "2") (pinfunction "2_2") (pintype "passive"))
      (node (ref "U22") (pin "4") (pinfunction "VOUT+_4") (pintype "output"))
    )
    (net (code "253") (name "Net-(U22-VOUT-)") (class "Default")
      (node (ref "C42") (pin "2") (pinfunction "2_2") (pintype "passive"))
      (node (ref "R57") (pin "2") (pinfunction "2_2") (pintype "passive"))
      (node (ref "U22") (pin "5") (pinfunction "VOUT-_5") (pintype "output"))
    )
    (net (code "254") (name "Net-(U23-VIN+)") (class "Default")
      (node (ref "C46") (pin "1") (pinfunction "1_1") (pintype "passive"))
      (node (ref "R61") (pin "1") (pinfunction "1_1") (pintype "passive"))
      (node (ref "R62") (pin "2") (pinfunction "2_2") (pintype "passive"))
      (node (ref "U23") (pin "8") (pinfunction "VIN+_8") (pintype "input"))
    )
    (net (code "255") (name "Net-(U23-VIN-)") (class "Default")
      (node (ref "C49") (pin "1") (pinfunction "1_1") (pintype "passive"))
      (node (ref "R64") (pin "1") (pinfunction "1_1") (pintype "passive"))
      (node (ref "R65") (pin "2") (pinfunction "2_2") (pintype "passive"))
      (node (ref "U23") (pin "1") (pinfunction "VIN-_1") (pintype "input"))
    )
    (net (code "256") (name "Net-(U23-VOUT+)") (class "Default")
      (node (ref "C49") (pin "2") (pinfunction "2_2") (pintype "passive"))
      (node (ref "R66") (pin "2") (pinfunction "2_2") (pintype "passive"))
      (node (ref "U23") (pin "4") (pinfunction "VOUT+_4") (pintype "output"))
    )
    (net (code "257") (name "Net-(U23-VOUT-)") (class "Default")
      (node (ref "C46") (pin "2") (pinfunction "2_2") (pintype "passive"))
      (node (ref "R63") (pin "2") (pinfunction "2_2") (pintype "passive"))
      (node (ref "U23") (pin "5") (pinfunction "VOUT-_5") (pintype "output"))
    )
    (net (code "258") (name "Net-(U24-VIN+)") (class "Default")
      (node (ref "C50") (pin "1") (pinfunction "1_1") (pintype "passive"))
      (node (ref "R67") (pin "1") (pinfunction "1_1") (pintype "passive"))
      (node (ref "R68") (pin "2") (pinfunction "2_2") (pintype "passive"))
      (node (ref "U24") (pin "8") (pinfunction "VIN+_8") (pintype "input"))
    )
    (net (code "259") (name "Net-(U24-VIN-)") (class "Default")
      (node (ref "C53") (pin "1") (pinfunction "1_1") (pintype "passive"))
      (node (ref "R70") (pin "1") (pinfunction "1_1") (pintype "passive"))
      (node (ref "R71") (pin "2") (pinfunction "2_2") (pintype "passive"))
      (node (ref "U24") (pin "1") (pinfunction "VIN-_1") (pintype "input"))
    )
    (net (code "260") (name "Net-(U24-VOUT+)") (class "Default")
      (node (ref "C53") (pin "2") (pinfunction "2_2") (pintype "passive"))
      (node (ref "R72") (pin "2") (pinfunction "2_2") (pintype "passive"))
      (node (ref "U24") (pin "4") (pinfunction "VOUT+_4") (pintype "output"))
    )
    (net (code "261") (name "Net-(U24-VOUT-)") (class "Default")
      (node (ref "C50") (pin "2") (pinfunction "2_2") (pintype "passive"))
      (node (ref "R69") (pin "2") (pinfunction "2_2") (pintype "passive"))
      (node (ref "U24") (pin "5") (pinfunction "VOUT-_5") (pintype "output"))
    )
    (net (code "262") (name "Net-(U25-VIN+)") (class "Default")
      (node (ref "C54") (pin "1") (pinfunction "1_1") (pintype "passive"))
      (node (ref "R73") (pin "1") (pinfunction "1_1") (pintype "passive"))
      (node (ref "R74") (pin "2") (pinfunction "2_2") (pintype "passive"))
      (node (ref "U25") (pin "8") (pinfunction "VIN+_8") (pintype "input"))
    )
    (net (code "263") (name "Net-(U25-VIN-)") (class "Default")
      (node (ref "C57") (pin "1") (pinfunction "1_1") (pintype "passive"))
      (node (ref "R76") (pin "1") (pinfunction "1_1") (pintype "passive"))
      (node (ref "R77") (pin "2") (pinfunction "2_2") (pintype "passive"))
      (node (ref "U25") (pin "1") (pinfunction "VIN-_1") (pintype "input"))
    )
    (net (code "264") (name "Net-(U25-VOUT+)") (class "Default")
      (node (ref "C57") (pin "2") (pinfunction "2_2") (pintype "passive"))
      (node (ref "R78") (pin "2") (pinfunction "2_2") (pintype "passive"))
      (node (ref "U25") (pin "4") (pinfunction "VOUT+_4") (pintype "output"))
    )
    (net (code "265") (name "Net-(U25-VOUT-)") (class "Default")
      (node (ref "C54") (pin "2") (pinfunction "2_2") (pintype "passive"))
      (node (ref "R75") (pin "2") (pinfunction "2_2") (pintype "passive"))
      (node (ref "U25") (pin "5") (pinfunction "VOUT-_5") (pintype "output"))
    )
    (net (code "266") (name "Net-(U26-VIN+)") (class "Default")
      (node (ref "C58") (pin "1") (pinfunction "1_1") (pintype "passive"))
      (node (ref "R79") (pin "1") (pinfunction "1_1") (pintype "passive"))
      (node (ref "R80") (pin "2") (pinfunction "2_2") (pintype "passive"))
      (node (ref "U26") (pin "8") (pinfunction "VIN+_8") (pintype "input"))
    )
    (net (code "267") (name "Net-(U26-VIN-)") (class "Default")
      (node (ref "C61") (pin "1") (pinfunction "1_1") (pintype "passive"))
      (node (ref "R82") (pin "1") (pinfunction "1_1") (pintype "passive"))
      (node (ref "R83") (pin "2") (pinfunction "2_2") (pintype "passive"))
      (node (ref "U26") (pin "1") (pinfunction "VIN-_1") (pintype "input"))
    )
    (net (code "268") (name "Net-(U26-VOUT+)") (class "Default")
      (node (ref "C61") (pin "2") (pinfunction "2_2") (pintype "passive"))
      (node (ref "R84") (pin "2") (pinfunction "2_2") (pintype "passive"))
      (node (ref "U26") (pin "4") (pinfunction "VOUT+_4") (pintype "output"))
    )
    (net (code "269") (name "Net-(U26-VOUT-)") (class "Default")
      (node (ref "C58") (pin "2") (pinfunction "2_2") (pintype "passive"))
      (node (ref "R81") (pin "2") (pinfunction "2_2") (pintype "passive"))
      (node (ref "U26") (pin "5") (pinfunction "VOUT-_5") (pintype "output"))
    )
    (net (code "270") (name "Net-(U27-VIN+)") (class "Default")
      (node (ref "C62") (pin "1") (pinfunction "1_1") (pintype "passive"))
      (node (ref "R85") (pin "1") (pinfunction "1_1") (pintype "passive"))
      (node (ref "R86") (pin "2") (pinfunction "2_2") (pintype "passive"))
      (node (ref "U27") (pin "8") (pinfunction "VIN+_8") (pintype "input"))
    )
    (net (code "271") (name "Net-(U27-VIN-)") (class "Default")
      (node (ref "C65") (pin "1") (pinfunction "1_1") (pintype "passive"))
      (node (ref "R88") (pin "1") (pinfunction "1_1") (pintype "passive"))
      (node (ref "R89") (pin "2") (pinfunction "2_2") (pintype "passive"))
      (node (ref "U27") (pin "1") (pinfunction "VIN-_1") (pintype "input"))
    )
    (net (code "272") (name "Net-(U27-VOUT+)") (class "Default")
      (node (ref "C65") (pin "2") (pinfunction "2_2") (pintype "passive"))
      (node (ref "R90") (pin "2") (pinfunction "2_2") (pintype "passive"))
      (node (ref "U27") (pin "4") (pinfunction "VOUT+_4") (pintype "output"))
    )
    (net (code "273") (name "Net-(U27-VOUT-)") (class "Default")
      (node (ref "C62") (pin "2") (pinfunction "2_2") (pintype "passive"))
      (node (ref "R87") (pin "2") (pinfunction "2_2") (pintype "passive"))
      (node (ref "U27") (pin "5") (pinfunction "VOUT-_5") (pintype "output"))
    )
    (net (code "274") (name "Net-(U28-VIN+)") (class "Default")
      (node (ref "C66") (pin "1") (pinfunction "1_1") (pintype "passive"))
      (node (ref "R91") (pin "1") (pinfunction "1_1") (pintype "passive"))
      (node (ref "R92") (pin "2") (pinfunction "2_2") (pintype "passive"))
      (node (ref "U28") (pin "8") (pinfunction "VIN+_8") (pintype "input"))
    )
    (net (code "275") (name "Net-(U28-VIN-)") (class "Default")
      (node (ref "C69") (pin "1") (pinfunction "1_1") (pintype "passive"))
      (node (ref "R94") (pin "1") (pinfunction "1_1") (pintype "passive"))
      (node (ref "R95") (pin "2") (pinfunction "2_2") (pintype "passive"))
      (node (ref "U28") (pin "1") (pinfunction "VIN-_1") (pintype "input"))
    )
    (net (code "276") (name "Net-(U28-VOUT+)") (class "Default")
      (node (ref "C69") (pin "2") (pinfunction "2_2") (pintype "passive"))
      (node (ref "R96") (pin "2") (pinfunction "2_2") (pintype "passive"))
      (node (ref "U28") (pin "4") (pinfunction "VOUT+_4") (pintype "output"))
    )
    (net (code "277") (name "Net-(U28-VOUT-)") (class "Default")
      (node (ref "C66") (pin "2") (pinfunction "2_2") (pintype "passive"))
      (node (ref "R93") (pin "2") (pinfunction "2_2") (pintype "passive"))
      (node (ref "U28") (pin "5") (pinfunction "VOUT-_5") (pintype "output"))
    )
    (net (code "278") (name "Net-(U29-VIN+)") (class "Default")
      (node (ref "C70") (pin "1") (pinfunction "1_1") (pintype "passive"))
      (node (ref "R97") (pin "1") (pinfunction "1_1") (pintype "passive"))
      (node (ref "R98") (pin "2") (pinfunction "2_2") (pintype "passive"))
      (node (ref "U29") (pin "8") (pinfunction "VIN+_8") (pintype "input"))
    )
    (net (code "279") (name "Net-(U29-VIN-)") (class "Default")
      (node (ref "C73") (pin "1") (pinfunction "1_1") (pintype "passive"))
      (node (ref "R100") (pin "1") (pinfunction "1_1") (pintype "passive"))
      (node (ref "R101") (pin "2") (pinfunction "2_2") (pintype "passive"))
      (node (ref "U29") (pin "1") (pinfunction "VIN-_1") (pintype "input"))
    )
    (net (code "280") (name "Net-(U29-VOUT+)") (class "Default")
      (node (ref "C73") (pin "2") (pinfunction "2_2") (pintype "passive"))
      (node (ref "R102") (pin "2") (pinfunction "2_2") (pintype "passive"))
      (node (ref "U29") (pin "4") (pinfunction "VOUT+_4") (pintype "output"))
    )
    (net (code "281") (name "Net-(U29-VOUT-)") (class "Default")
      (node (ref "C70") (pin "2") (pinfunction "2_2") (pintype "passive"))
      (node (ref "R99") (pin "2") (pinfunction "2_2") (pintype "passive"))
      (node (ref "U29") (pin "5") (pinfunction "VOUT-_5") (pintype "output"))
    )
    (net (code "282") (name "Net-(U30-VIN+)") (class "Default")
      (node (ref "C83") (pin "1") (pinfunction "1_1") (pintype "passive"))
      (node (ref "R109") (pin "1") (pinfunction "1_1") (pintype "passive"))
      (node (ref "R110") (pin "2") (pinfunction "2_2") (pintype "passive"))
      (node (ref "U30") (pin "8") (pinfunction "VIN+_8") (pintype "input"))
    )
    (net (code "283") (name "Net-(U30-VIN-)") (class "Default")
      (node (ref "C86") (pin "1") (pinfunction "1_1") (pintype "passive"))
      (node (ref "R112") (pin "1") (pinfunction "1_1") (pintype "passive"))
      (node (ref "R113") (pin "2") (pinfunction "2_2") (pintype "passive"))
      (node (ref "U30") (pin "1") (pinfunction "VIN-_1") (pintype "input"))
    )
    (net (code "284") (name "Net-(U30-VOUT+)") (class "Default")
      (node (ref "C86") (pin "2") (pinfunction "2_2") (pintype "passive"))
      (node (ref "R114") (pin "2") (pinfunction "2_2") (pintype "passive"))
      (node (ref "U30") (pin "4") (pinfunction "VOUT+_4") (pintype "output"))
    )
    (net (code "285") (name "Net-(U30-VOUT-)") (class "Default")
      (node (ref "C83") (pin "2") (pinfunction "2_2") (pintype "passive"))
      (node (ref "R111") (pin "2") (pinfunction "2_2") (pintype "passive"))
      (node (ref "U30") (pin "5") (pinfunction "VOUT-_5") (pintype "output"))
    )
    (net (code "286") (name "Net-(U31-VIN+)") (class "Default")
      (node (ref "C87") (pin "1") (pinfunction "1_1") (pintype "passive"))
      (node (ref "R115") (pin "1") (pinfunction "1_1") (pintype "passive"))
      (node (ref "R116") (pin "2") (pinfunction "2_2") (pintype "passive"))
      (node (ref "U31") (pin "8") (pinfunction "VIN+_8") (pintype "input"))
    )
    (net (code "287") (name "Net-(U31-VIN-)") (class "Default")
      (node (ref "C90") (pin "1") (pinfunction "1_1") (pintype "passive"))
      (node (ref "R118") (pin "1") (pinfunction "1_1") (pintype "passive"))
      (node (ref "R119") (pin "2") (pinfunction "2_2") (pintype "passive"))
      (node (ref "U31") (pin "1") (pinfunction "VIN-_1") (pintype "input"))
    )
    (net (code "288") (name "Net-(U31-VOUT+)") (class "Default")
      (node (ref "C90") (pin "2") (pinfunction "2_2") (pintype "passive"))
      (node (ref "R120") (pin "2") (pinfunction "2_2") (pintype "passive"))
      (node (ref "U31") (pin "4") (pinfunction "VOUT+_4") (pintype "output"))
    )
    (net (code "289") (name "Net-(U31-VOUT-)") (class "Default")
      (node (ref "C87") (pin "2") (pinfunction "2_2") (pintype "passive"))
      (node (ref "R117") (pin "2") (pinfunction "2_2") (pintype "passive"))
      (node (ref "U31") (pin "5") (pinfunction "VOUT-_5") (pintype "output"))
    )
    (net (code "290") (name "Net-(U32-VIN+)") (class "Default")
      (node (ref "C91") (pin "1") (pinfunction "1_1") (pintype "passive"))
      (node (ref "R121") (pin "1") (pinfunction "1_1") (pintype "passive"))
      (node (ref "R122") (pin "2") (pinfunction "2_2") (pintype "passive"))
      (node (ref "U32") (pin "8") (pinfunction "VIN+_8") (pintype "input"))
    )
    (net (code "291") (name "Net-(U32-VIN-)") (class "Default")
      (node (ref "C94") (pin "1") (pinfunction "1_1") (pintype "passive"))
      (node (ref "R124") (pin "1") (pinfunction "1_1") (pintype "passive"))
      (node (ref "R125") (pin "2") (pinfunction "2_2") (pintype "passive"))
      (node (ref "U32") (pin "1") (pinfunction "VIN-_1") (pintype "input"))
    )
    (net (code "292") (name "Net-(U32-VOUT+)") (class "Default")
      (node (ref "C94") (pin "2") (pinfunction "2_2") (pintype "passive"))
      (node (ref "R126") (pin "2") (pinfunction "2_2") (pintype "passive"))
      (node (ref "U32") (pin "4") (pinfunction "VOUT+_4") (pintype "output"))
    )
    (net (code "293") (name "Net-(U32-VOUT-)") (class "Default")
      (node (ref "C91") (pin "2") (pinfunction "2_2") (pintype "passive"))
      (node (ref "R123") (pin "2") (pinfunction "2_2") (pintype "passive"))
      (node (ref "U32") (pin "5") (pinfunction "VOUT-_5") (pintype "output"))
    )
    (net (code "294") (name "Net-(U33-VIN+)") (class "Default")
      (node (ref "C95") (pin "1") (pinfunction "1_1") (pintype "passive"))
      (node (ref "R127") (pin "1") (pinfunction "1_1") (pintype "passive"))
      (node (ref "R128") (pin "2") (pinfunction "2_2") (pintype "passive"))
      (node (ref "U33") (pin "8") (pinfunction "VIN+_8") (pintype "input"))
    )
    (net (code "295") (name "Net-(U33-VIN-)") (class "Default")
      (node (ref "C98") (pin "1") (pinfunction "1_1") (pintype "passive"))
      (node (ref "R130") (pin "1") (pinfunction "1_1") (pintype "passive"))
      (node (ref "R131") (pin "2") (pinfunction "2_2") (pintype "passive"))
      (node (ref "U33") (pin "1") (pinfunction "VIN-_1") (pintype "input"))
    )
    (net (code "296") (name "Net-(U33-VOUT+)") (class "Default")
      (node (ref "C98") (pin "2") (pinfunction "2_2") (pintype "passive"))
      (node (ref "R132") (pin "2") (pinfunction "2_2") (pintype "passive"))
      (node (ref "U33") (pin "4") (pinfunction "VOUT+_4") (pintype "output"))
    )
    (net (code "297") (name "Net-(U33-VOUT-)") (class "Default")
      (node (ref "C95") (pin "2") (pinfunction "2_2") (pintype "passive"))
      (node (ref "R129") (pin "2") (pinfunction "2_2") (pintype "passive"))
      (node (ref "U33") (pin "5") (pinfunction "VOUT-_5") (pintype "output"))
    )
    (net (code "298") (name "RX") (class "Default")
      (node (ref "JP1") (pin "10") (pinfunction "10_10") (pintype "passive"))
    )
    (net (code "299") (name "SCL") (class "Default")
      (node (ref "IC1") (pin "SCL") (pinfunction "SCL_SCL") (pintype "bidirectional"))
      (node (ref "JP1") (pin "5") (pinfunction "5_5") (pintype "passive"))
    )
    (net (code "300") (name "SCLK1") (class "Default")
      (node (ref "JP3") (pin "2") (pinfunction "2_2") (pintype "passive"))
      (node (ref "U11") (pin "28") (pinfunction "SCLK_28") (pintype "bidirectional"))
    )
    (net (code "301") (name "SCLK2") (class "Default")
      (node (ref "JP3") (pin "25") (pinfunction "25_25") (pintype "passive"))
      (node (ref "U6") (pin "28") (pinfunction "SCLK_28") (pintype "bidirectional"))
    )
    (net (code "302") (name "SCLK3") (class "Default")
      (node (ref "JP2") (pin "10") (pinfunction "10_10") (pintype "passive"))
      (node (ref "U9") (pin "28") (pinfunction "SCLK_28") (pintype "bidirectional"))
    )
    (net (code "303") (name "SDA") (class "Default")
      (node (ref "IC1") (pin "SDA") (pinfunction "SDA_SDA") (pintype "bidirectional"))
      (node (ref "JP1") (pin "3") (pinfunction "3_3") (pintype "passive"))
    )
    (net (code "304") (name "SIGNAL") (class "Default")
      (node (ref "JP1") (pin "8") (pinfunction "8_8") (pintype "passive"))
      (node (ref "JP5") (pin "1") (pinfunction "1_1") (pintype "passive"))
    )
    (net (code "305") (name "SYNC1") (class "Default")
      (node (ref "JP3") (pin "14") (pinfunction "14_14") (pintype "passive"))
      (node (ref "U11") (pin "11") (pinfunction "~{SYNC}_11") (pintype "input"))
    )
    (net (code "306") (name "SYNC2") (class "Default")
      (node (ref "JP3") (pin "15") (pinfunction "15_15") (pintype "passive"))
      (node (ref "U6") (pin "11") (pinfunction "~{SYNC}_11") (pintype "input"))
    )
    (net (code "307") (name "SYNC3") (class "Default")
      (node (ref "JP2") (pin "17") (pinfunction "17_17") (pintype "passive"))
      (node (ref "U9") (pin "11") (pinfunction "~{SYNC}_11") (pintype "input"))
    )
    (net (code "308") (name "VCOM1") (class "Default")
      (node (ref "C11") (pin "1") (pinfunction "1_1") (pintype "passive"))
      (node (ref "C15") (pin "1") (pinfunction "1_1") (pintype "passive"))
      (node (ref "C19") (pin "1") (pinfunction "1_1") (pintype "passive"))
      (node (ref "C23") (pin "1") (pinfunction "1_1") (pintype "passive"))
      (node (ref "C27") (pin "1") (pinfunction "1_1") (pintype "passive"))
      (node (ref "C3") (pin "1") (pinfunction "1_1") (pintype "passive"))
      (node (ref "C31") (pin "1") (pinfunction "1_1") (pintype "passive"))
      (node (ref "C7") (pin "1") (pinfunction "1_1") (pintype "passive"))
      (node (ref "R54") (pin "2") (pinfunction "2_2") (pintype "passive"))
      (node (ref "U14") (pin "2") (pinfunction "VOCM_2") (pintype "passive"))
      (node (ref "U15") (pin "2") (pinfunction "VOCM_2") (pintype "passive"))
      (node (ref "U16") (pin "2") (pinfunction "VOCM_2") (pintype "passive"))
      (node (ref "U17") (pin "2") (pinfunction "VOCM_2") (pintype "passive"))
      (node (ref "U18") (pin "2") (pinfunction "VOCM_2") (pintype "passive"))
      (node (ref "U19") (pin "2") (pinfunction "VOCM_2") (pintype "passive"))
      (node (ref "U20") (pin "2") (pinfunction "VOCM_2") (pintype "passive"))
      (node (ref "U21") (pin "2") (pinfunction "VOCM_2") (pintype "passive"))
    )
    (net (code "309") (name "VCOM2") (class "Default")
      (node (ref "C44") (pin "1") (pinfunction "1_1") (pintype "passive"))
      (node (ref "C48") (pin "1") (pinfunction "1_1") (pintype "passive"))
      (node (ref "C52") (pin "1") (pinfunction "1_1") (pintype "passive"))
      (node (ref "C56") (pin "1") (pinfunction "1_1") (pintype "passive"))
      (node (ref "C60") (pin "1") (pinfunction "1_1") (pintype "passive"))
      (node (ref "C64") (pin "1") (pinfunction "1_1") (pintype "passive"))
      (node (ref "C68") (pin "1") (pinfunction "1_1") (pintype "passive"))
      (node (ref "C72") (pin "1") (pinfunction "1_1") (pintype "passive"))
      (node (ref "R108") (pin "2") (pinfunction "2_2") (pintype "passive"))
      (node (ref "U22") (pin "2") (pinfunction "VOCM_2") (pintype "passive"))
      (node (ref "U23") (pin "2") (pinfunction "VOCM_2") (pintype "passive"))
      (node (ref "U24") (pin "2") (pinfunction "VOCM_2") (pintype "passive"))
      (node (ref "U25") (pin "2") (pinfunction "VOCM_2") (pintype "passive"))
      (node (ref "U26") (pin "2") (pinfunction "VOCM_2") (pintype "passive"))
      (node (ref "U27") (pin "2") (pinfunction "VOCM_2") (pintype "passive"))
      (node (ref "U28") (pin "2") (pinfunction "VOCM_2") (pintype "passive"))
      (node (ref "U29") (pin "2") (pinfunction "VOCM_2") (pintype "passive"))
    )
    (net (code "310") (name "VCOM3") (class "Default")
      (node (ref "C85") (pin "1") (pinfunction "1_1") (pintype "passive"))
      (node (ref "C89") (pin "1") (pinfunction "1_1") (pintype "passive"))
      (node (ref "C93") (pin "1") (pinfunction "1_1") (pintype "passive"))
      (node (ref "C97") (pin "1") (pinfunction "1_1") (pintype "passive"))
      (node (ref "R138") (pin "2") (pinfunction "2_2") (pintype "passive"))
      (node (ref "U30") (pin "2") (pinfunction "VOCM_2") (pintype "passive"))
      (node (ref "U31") (pin "2") (pinfunction "VOCM_2") (pintype "passive"))
      (node (ref "U32") (pin "2") (pinfunction "VOCM_2") (pintype "passive"))
      (node (ref "U33") (pin "2") (pinfunction "VOCM_2") (pintype "passive"))
    )
    (net (code "311") (name "VCOMM1") (class "Default")
      (node (ref "C38") (pin "1") (pinfunction "1_1") (pintype "passive"))
      (node (ref "U11") (pin "55") (pinfunction "VCOM_55") (pintype "output"))
      (node (ref "U2") (pin "3") (pinfunction "IN+_3") (pintype "input"))
    )
    (net (code "312") (name "VCOMM2") (class "Default")
      (node (ref "C79") (pin "1") (pinfunction "1_1") (pintype "passive"))
      (node (ref "U5") (pin "3") (pinfunction "IN+_3") (pintype "input"))
      (node (ref "U6") (pin "55") (pinfunction "VCOM_55") (pintype "output"))
    )
    (net (code "313") (name "VCOMM3") (class "Default")
      (node (ref "C104") (pin "1") (pinfunction "1_1") (pintype "passive"))
      (node (ref "U8") (pin "3") (pinfunction "IN+_3") (pintype "input"))
      (node (ref "U9") (pin "55") (pinfunction "VCOM_55") (pintype "output"))
    )
    (net (code "314") (name "VREFP1") (class "Default")
      (node (ref "C36") (pin "1") (pinfunction "1_1") (pintype "passive"))
      (node (ref "C37") (pin "1") (pinfunction "1_1") (pintype "passive"))
      (node (ref "R51") (pin "2") (pinfunction "2_2") (pintype "passive"))
      (node (ref "R52") (pin "2") (pinfunction "2_2") (pintype "passive"))
      (node (ref "U11") (pin "56") (pinfunction "VREFP_56") (pintype "input"))
    )
    (net (code "315") (name "VREFP2") (class "Default")
      (node (ref "C77") (pin "1") (pinfunction "1_1") (pintype "passive"))
      (node (ref "C78") (pin "1") (pinfunction "1_1") (pintype "passive"))
      (node (ref "R105") (pin "2") (pinfunction "2_2") (pintype "passive"))
      (node (ref "R106") (pin "2") (pinfunction "2_2") (pintype "passive"))
      (node (ref "U6") (pin "56") (pinfunction "VREFP_56") (pintype "input"))
    )
    (net (code "316") (name "VREFP3") (class "Default")
      (node (ref "C102") (pin "1") (pinfunction "1_1") (pintype "passive"))
      (node (ref "C103") (pin "1") (pinfunction "1_1") (pintype "passive"))
      (node (ref "R135") (pin "2") (pinfunction "2_2") (pintype "passive"))
      (node (ref "R136") (pin "2") (pinfunction "2_2") (pintype "passive"))
      (node (ref "U9") (pin "56") (pinfunction "VREFP_56") (pintype "input"))
    )
    (net (code "317") (name "unconnected-(IC1-Pad32K)") (class "Default")
      (node (ref "IC1") (pin "32K") (pinfunction "32K_32K") (pintype "bidirectional"))
    )
    (net (code "318") (name "unconnected-(IC1-PadBAT)") (class "Default")
      (node (ref "IC1") (pin "BAT") (pinfunction "BAT_BAT") (pintype "bidirectional"))
    )
    (net (code "319") (name "unconnected-(IC1-PadSQW)") (class "Default")
      (node (ref "IC1") (pin "SQW") (pinfunction "SQW_SQW") (pintype "bidirectional"))
    )
    (net (code "320") (name "unconnected-(IC1-RST-PadRES)") (class "Default")
      (node (ref "IC1") (pin "RES") (pinfunction "RST_RES") (pintype "bidirectional"))
    )
    (net (code "321") (name "unconnected-(IC27-EN-Pad1)") (class "Default")
      (node (ref "IC27") (pin "1") (pinfunction "EN_1") (pintype "bidirectional"))
    )
    (net (code "322") (name "unconnected-(IC27-PG-Pad2)") (class "Default")
      (node (ref "IC27") (pin "2") (pinfunction "PG_2") (pintype "bidirectional"))
    )
    (net (code "323") (name "unconnected-(IC28-SHDN-Pad1)") (class "Default")
      (node (ref "IC28") (pin "1") (pinfunction "SHDN_1") (pintype "bidirectional"))
    )
    (net (code "324") (name "unconnected-(IC29-PG-Pad1)") (class "Default")
      (node (ref "IC29") (pin "1") (pinfunction "PG_1") (pintype "bidirectional"))
    )
    (net (code "325") (name "unconnected-(IC29-SHDN-Pad2)") (class "Default")
      (node (ref "IC29") (pin "2") (pinfunction "SHDN_2") (pintype "bidirectional"))
    )
    (net (code "326") (name "unconnected-(IC30-PadEN)") (class "Default")
      (node (ref "IC30") (pin "EN") (pinfunction "EN_EN") (pintype "bidirectional"))
    )
    (net (code "327") (name "unconnected-(IC43-PadEN)") (class "Default")
      (node (ref "IC43") (pin "EN") (pinfunction "EN_EN") (pintype "bidirectional"))
    )
    (net (code "328") (name "unconnected-(JP1-Pad2)") (class "Default")
      (node (ref "JP1") (pin "2") (pinfunction "2_2") (pintype "passive"))
    )
    (net (code "329") (name "unconnected-(JP1-Pad12)") (class "Default")
      (node (ref "JP1") (pin "12") (pinfunction "12_12") (pintype "passive"))
    )
    (net (code "330") (name "unconnected-(JP1-Pad16)") (class "Default")
      (node (ref "JP1") (pin "16") (pinfunction "16_16") (pintype "passive"))
    )
    (net (code "331") (name "unconnected-(JP1-Pad17)") (class "Default")
      (node (ref "JP1") (pin "17") (pinfunction "17_17") (pintype "passive"))
    )
    (net (code "332") (name "unconnected-(JP1-Pad18)") (class "Default")
      (node (ref "JP1") (pin "18") (pinfunction "18_18") (pintype "passive"))
    )
    (net (code "333") (name "unconnected-(JP1-Pad22)") (class "Default")
      (node (ref "JP1") (pin "22") (pinfunction "22_22") (pintype "passive"))
    )
    (net (code "334") (name "unconnected-(JP1-Pad23)") (class "Default")
      (node (ref "JP1") (pin "23") (pinfunction "23_23") (pintype "passive"))
    )
    (net (code "335") (name "unconnected-(JP1-Pad24)") (class "Default")
      (node (ref "JP1") (pin "24") (pinfunction "24_24") (pintype "passive"))
    )
    (net (code "336") (name "unconnected-(JP1-Pad26)") (class "Default")
      (node (ref "JP1") (pin "26") (pinfunction "26_26") (pintype "passive"))
    )
    (net (code "337") (name "unconnected-(JP1-Pad27)") (class "Default")
      (node (ref "JP1") (pin "27") (pinfunction "27_27") (pintype "passive"))
    )
    (net (code "338") (name "unconnected-(JP1-Pad28)") (class "Default")
      (node (ref "JP1") (pin "28") (pinfunction "28_28") (pintype "passive"))
    )
    (net (code "339") (name "unconnected-(JP1-Pad29)") (class "Default")
      (node (ref "JP1") (pin "29") (pinfunction "29_29") (pintype "passive"))
    )
    (net (code "340") (name "unconnected-(JP1-Pad31)") (class "Default")
      (node (ref "JP1") (pin "31") (pinfunction "31_31") (pintype "passive"))
    )
    (net (code "341") (name "unconnected-(JP1-Pad32)") (class "Default")
      (node (ref "JP1") (pin "32") (pinfunction "32_32") (pintype "passive"))
    )
    (net (code "342") (name "unconnected-(JP1-Pad33)") (class "Default")
      (node (ref "JP1") (pin "33") (pinfunction "33_33") (pintype "passive"))
    )
    (net (code "343") (name "unconnected-(JP1-Pad35)") (class "Default")
      (node (ref "JP1") (pin "35") (pinfunction "35_35") (pintype "passive"))
    )
    (net (code "344") (name "unconnected-(JP1-Pad36)") (class "Default")
      (node (ref "JP1") (pin "36") (pinfunction "36_36") (pintype "passive"))
    )
    (net (code "345") (name "unconnected-(JP1-Pad37)") (class "Default")
      (node (ref "JP1") (pin "37") (pinfunction "37_37") (pintype "passive"))
    )
    (net (code "346") (name "unconnected-(JP1-Pad38)") (class "Default")
      (node (ref "JP1") (pin "38") (pinfunction "38_38") (pintype "passive"))
    )
    (net (code "347") (name "unconnected-(JP1-Pad40)") (class "Default")
      (node (ref "JP1") (pin "40") (pinfunction "40_40") (pintype "passive"))
    )
    (net (code "348") (name "unconnected-(JP2-Pad11)") (class "Default")
      (node (ref "JP2") (pin "11") (pinfunction "11_11") (pintype "passive"))
    )
    (net (code "349") (name "unconnected-(JP2-Pad29)") (class "Default")
      (node (ref "JP2") (pin "29") (pinfunction "29_29") (pintype "passive"))
    )
    (net (code "350") (name "unconnected-(JP3-Pad11)") (class "Default")
      (node (ref "JP3") (pin "11") (pinfunction "11_11") (pintype "passive"))
    )
    (net (code "351") (name "unconnected-(JP3-Pad29)") (class "Default")
      (node (ref "JP3") (pin "29") (pinfunction "29_29") (pintype "passive"))
    )
    (net (code "352") (name "unconnected-(U$4-EN-Pad2)") (class "Default")
      (node (ref "U$4") (pin "2") (pinfunction "EN_2") (pintype "bidirectional"))
    )
    (net (code "353") (name "unconnected-(U$4-PE-Pad1)") (class "Default")
      (node (ref "U$4") (pin "1") (pinfunction "PE_1") (pintype "bidirectional"))
    )
    (net (code "354") (name "unconnected-(U1-NC-Pad8)") (class "Default")
      (node (ref "U1") (pin "8") (pinfunction "NC_8") (pintype "passive"))
    )
    (net (code "355") (name "unconnected-(U1-NC_2-Pad1)") (class "Default")
      (node (ref "U1") (pin "1") (pinfunction "NC_2_1") (pintype "passive"))
    )
    (net (code "356") (name "unconnected-(U1-NC_3-Pad5)") (class "Default")
      (node (ref "U1") (pin "5") (pinfunction "NC_3_5") (pintype "passive"))
    )
    (net (code "357") (name "unconnected-(U2-NC-Pad8)") (class "Default")
      (node (ref "U2") (pin "8") (pinfunction "NC_8") (pintype "passive"))
    )
    (net (code "358") (name "unconnected-(U2-NC_2-Pad1)") (class "Default")
      (node (ref "U2") (pin "1") (pinfunction "NC_2_1") (pintype "passive"))
    )
    (net (code "359") (name "unconnected-(U2-NC_3-Pad5)") (class "Default")
      (node (ref "U2") (pin "5") (pinfunction "NC_3_5") (pintype "passive"))
    )
    (net (code "360") (name "unconnected-(U3-DNC-Pad8)") (class "Default")
      (node (ref "U3") (pin "8") (pinfunction "DNC_8") (pintype "passive"))
    )
    (net (code "361") (name "unconnected-(U3-DNC_2-Pad1)") (class "Default")
      (node (ref "U3") (pin "1") (pinfunction "DNC_2_1") (pintype "passive"))
    )
    (net (code "362") (name "unconnected-(U3-NC-Pad7)") (class "Default")
      (node (ref "U3") (pin "7") (pinfunction "NC_7") (pintype "passive"))
    )
    (net (code "363") (name "unconnected-(U3-TEMP-Pad3)") (class "Default")
      (node (ref "U3") (pin "3") (pinfunction "TEMP_3") (pintype "passive"))
    )
    (net (code "364") (name "unconnected-(U4-NC-Pad8)") (class "Default")
      (node (ref "U4") (pin "8") (pinfunction "NC_8") (pintype "passive"))
    )
    (net (code "365") (name "unconnected-(U4-NC_2-Pad1)") (class "Default")
      (node (ref "U4") (pin "1") (pinfunction "NC_2_1") (pintype "passive"))
    )
    (net (code "366") (name "unconnected-(U4-NC_3-Pad5)") (class "Default")
      (node (ref "U4") (pin "5") (pinfunction "NC_3_5") (pintype "passive"))
    )
    (net (code "367") (name "unconnected-(U5-NC-Pad8)") (class "Default")
      (node (ref "U5") (pin "8") (pinfunction "NC_8") (pintype "passive"))
    )
    (net (code "368") (name "unconnected-(U5-NC_2-Pad1)") (class "Default")
      (node (ref "U5") (pin "1") (pinfunction "NC_2_1") (pintype "passive"))
    )
    (net (code "369") (name "unconnected-(U5-NC_3-Pad5)") (class "Default")
      (node (ref "U5") (pin "5") (pinfunction "NC_3_5") (pintype "passive"))
    )
    (net (code "370") (name "unconnected-(U7-NC-Pad8)") (class "Default")
      (node (ref "U7") (pin "8") (pinfunction "NC_8") (pintype "passive"))
    )
    (net (code "371") (name "unconnected-(U7-NC_2-Pad1)") (class "Default")
      (node (ref "U7") (pin "1") (pinfunction "NC_2_1") (pintype "passive"))
    )
    (net (code "372") (name "unconnected-(U7-NC_3-Pad5)") (class "Default")
      (node (ref "U7") (pin "5") (pinfunction "NC_3_5") (pintype "passive"))
    )
    (net (code "373") (name "unconnected-(U8-NC-Pad8)") (class "Default")
      (node (ref "U8") (pin "8") (pinfunction "NC_8") (pintype "passive"))
    )
    (net (code "374") (name "unconnected-(U8-NC_2-Pad1)") (class "Default")
      (node (ref "U8") (pin "1") (pinfunction "NC_2_1") (pintype "passive"))
    )
    (net (code "375") (name "unconnected-(U8-NC_3-Pad5)") (class "Default")
      (node (ref "U8") (pin "5") (pinfunction "NC_3_5") (pintype "passive"))
    )
    (net (code "376") (name "unconnected-(U12-DNC-Pad8)") (class "Default")
      (node (ref "U12") (pin "8") (pinfunction "DNC_8") (pintype "passive"))
    )
    (net (code "377") (name "unconnected-(U12-DNC_2-Pad1)") (class "Default")
      (node (ref "U12") (pin "1") (pinfunction "DNC_2_1") (pintype "passive"))
    )
    (net (code "378") (name "unconnected-(U12-NC-Pad7)") (class "Default")
      (node (ref "U12") (pin "7") (pinfunction "NC_7") (pintype "passive"))
    )
    (net (code "379") (name "unconnected-(U12-TEMP-Pad3)") (class "Default")
      (node (ref "U12") (pin "3") (pinfunction "TEMP_3") (pintype "passive"))
    )
    (net (code "380") (name "unconnected-(U13-DNC-Pad8)") (class "Default")
      (node (ref "U13") (pin "8") (pinfunction "DNC_8") (pintype "passive"))
    )
    (net (code "381") (name "unconnected-(U13-DNC_2-Pad1)") (class "Default")
      (node (ref "U13") (pin "1") (pinfunction "DNC_2_1") (pintype "passive"))
    )
    (net (code "382") (name "unconnected-(U13-NC-Pad7)") (class "Default")
      (node (ref "U13") (pin "7") (pinfunction "NC_7") (pintype "passive"))
    )
    (net (code "383") (name "unconnected-(U13-TEMP-Pad3)") (class "Default")
      (node (ref "U13") (pin "3") (pinfunction "TEMP_3") (pintype "passive"))
    )
    (net (code "384") (name "unconnected-(U14-~{PD}-Pad7)") (class "Default")
      (node (ref "U14") (pin "7") (pinfunction "~{PD}_7") (pintype "passive"))
    )
    (net (code "385") (name "unconnected-(U15-~{PD}-Pad7)") (class "Default")
      (node (ref "U15") (pin "7") (pinfunction "~{PD}_7") (pintype "passive"))
    )
    (net (code "386") (name "unconnected-(U16-~{PD}-Pad7)") (class "Default")
      (node (ref "U16") (pin "7") (pinfunction "~{PD}_7") (pintype "passive"))
    )
    (net (code "387") (name "unconnected-(U17-~{PD}-Pad7)") (class "Default")
      (node (ref "U17") (pin "7") (pinfunction "~{PD}_7") (pintype "passive"))
    )
    (net (code "388") (name "unconnected-(U18-~{PD}-Pad7)") (class "Default")
      (node (ref "U18") (pin "7") (pinfunction "~{PD}_7") (pintype "passive"))
    )
    (net (code "389") (name "unconnected-(U19-~{PD}-Pad7)") (class "Default")
      (node (ref "U19") (pin "7") (pinfunction "~{PD}_7") (pintype "passive"))
    )
    (net (code "390") (name "unconnected-(U20-~{PD}-Pad7)") (class "Default")
      (node (ref "U20") (pin "7") (pinfunction "~{PD}_7") (pintype "passive"))
    )
    (net (code "391") (name "unconnected-(U21-~{PD}-Pad7)") (class "Default")
      (node (ref "U21") (pin "7") (pinfunction "~{PD}_7") (pintype "passive"))
    )
    (net (code "392") (name "unconnected-(U22-~{PD}-Pad7)") (class "Default")
      (node (ref "U22") (pin "7") (pinfunction "~{PD}_7") (pintype "passive"))
    )
    (net (code "393") (name "unconnected-(U23-~{PD}-Pad7)") (class "Default")
      (node (ref "U23") (pin "7") (pinfunction "~{PD}_7") (pintype "passive"))
    )
    (net (code "394") (name "unconnected-(U24-~{PD}-Pad7)") (class "Default")
      (node (ref "U24") (pin "7") (pinfunction "~{PD}_7") (pintype "passive"))
    )
    (net (code "395") (name "unconnected-(U25-~{PD}-Pad7)") (class "Default")
      (node (ref "U25") (pin "7") (pinfunction "~{PD}_7") (pintype "passive"))
    )
    (net (code "396") (name "unconnected-(U26-~{PD}-Pad7)") (class "Default")
      (node (ref "U26") (pin "7") (pinfunction "~{PD}_7") (pintype "passive"))
    )
    (net (code "397") (name "unconnected-(U27-~{PD}-Pad7)") (class "Default")
      (node (ref "U27") (pin "7") (pinfunction "~{PD}_7") (pintype "passive"))
    )
    (net (code "398") (name "unconnected-(U28-~{PD}-Pad7)") (class "Default")
      (node (ref "U28") (pin "7") (pinfunction "~{PD}_7") (pintype "passive"))
    )
    (net (code "399") (name "unconnected-(U29-~{PD}-Pad7)") (class "Default")
      (node (ref "U29") (pin "7") (pinfunction "~{PD}_7") (pintype "passive"))
    )
    (net (code "400") (name "unconnected-(U30-~{PD}-Pad7)") (class "Default")
      (node (ref "U30") (pin "7") (pinfunction "~{PD}_7") (pintype "passive"))
    )
    (net (code "401") (name "unconnected-(U31-~{PD}-Pad7)") (class "Default")
      (node (ref "U31") (pin "7") (pinfunction "~{PD}_7") (pintype "passive"))
    )
    (net (code "402") (name "unconnected-(U32-~{PD}-Pad7)") (class "Default")
      (node (ref "U32") (pin "7") (pinfunction "~{PD}_7") (pintype "passive"))
    )
    (net (code "403") (name "unconnected-(U33-~{PD}-Pad7)") (class "Default")
      (node (ref "U33") (pin "7") (pinfunction "~{PD}_7") (pintype "passive"))
    )
  )
)
